# flycopter_v1.net
KiCad netlist of a schematic drawn in EAGLE
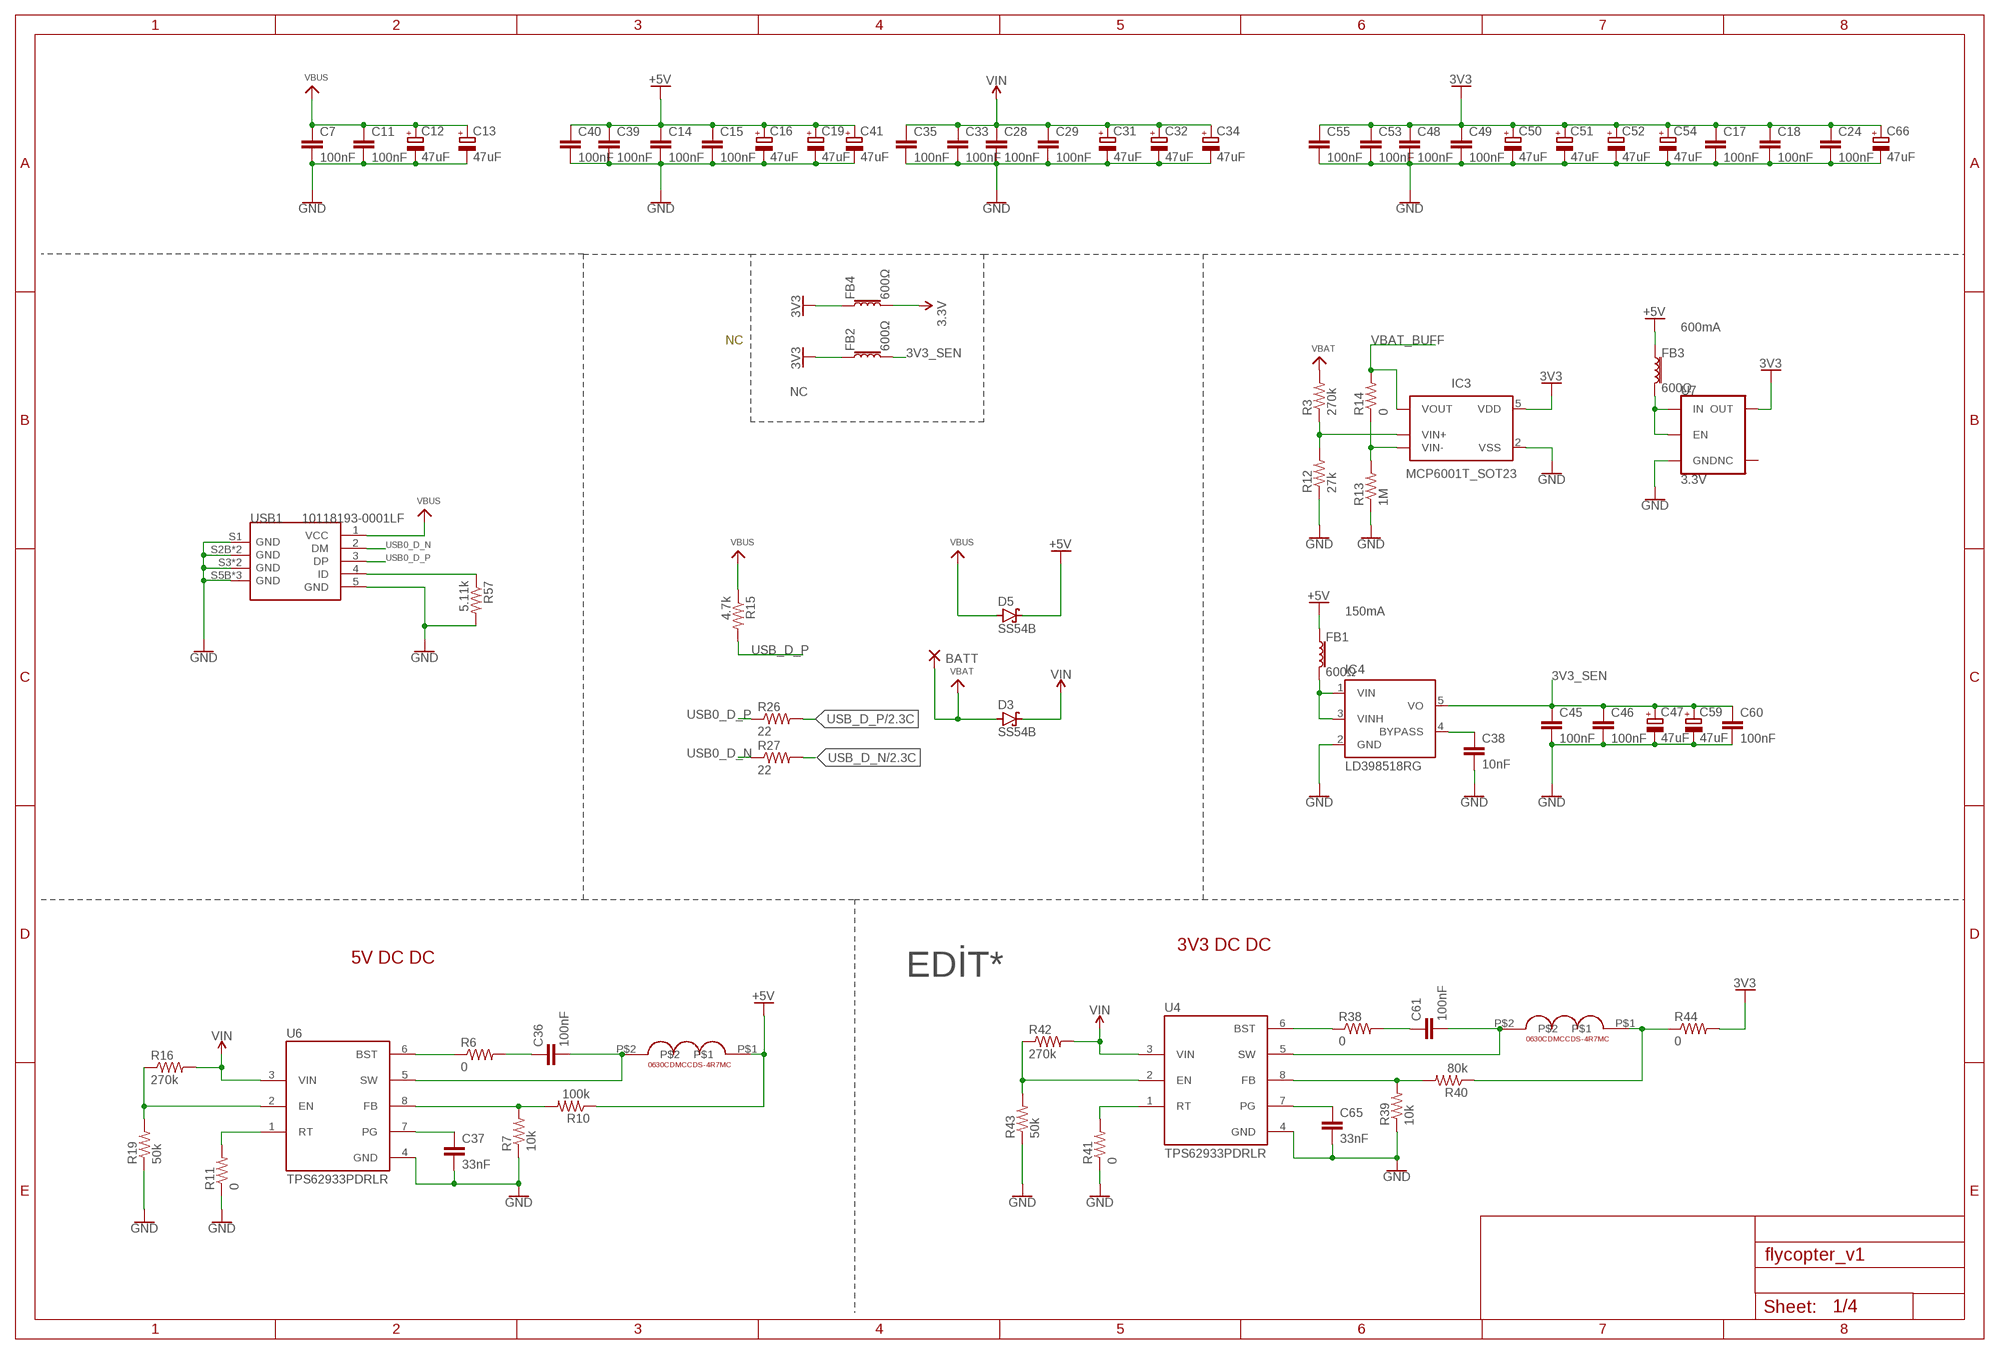
[diagram p0: schematic, sheet 1]
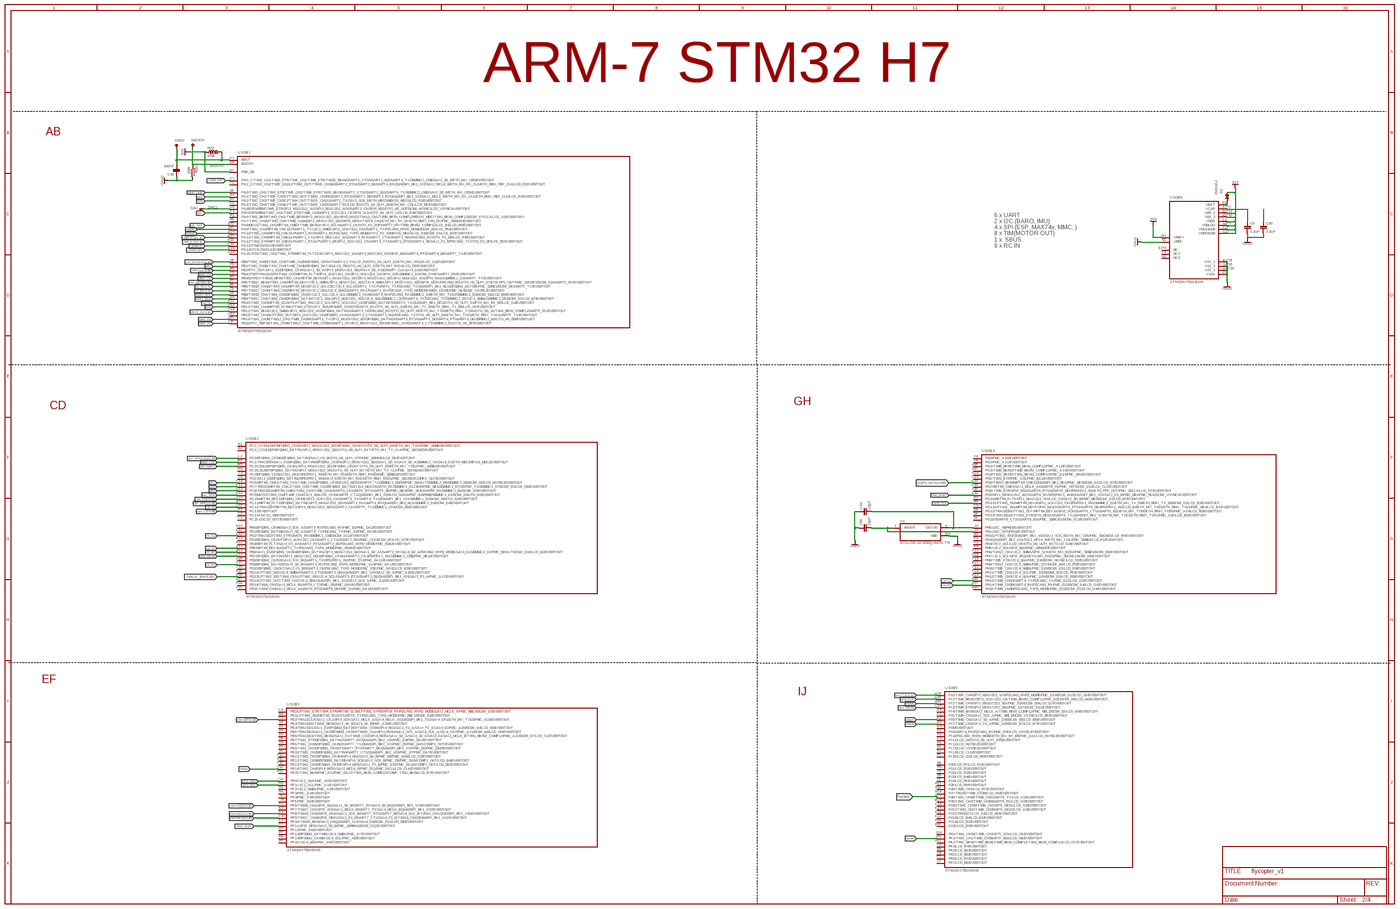
[diagram p1: schematic, sheet 2, overview]
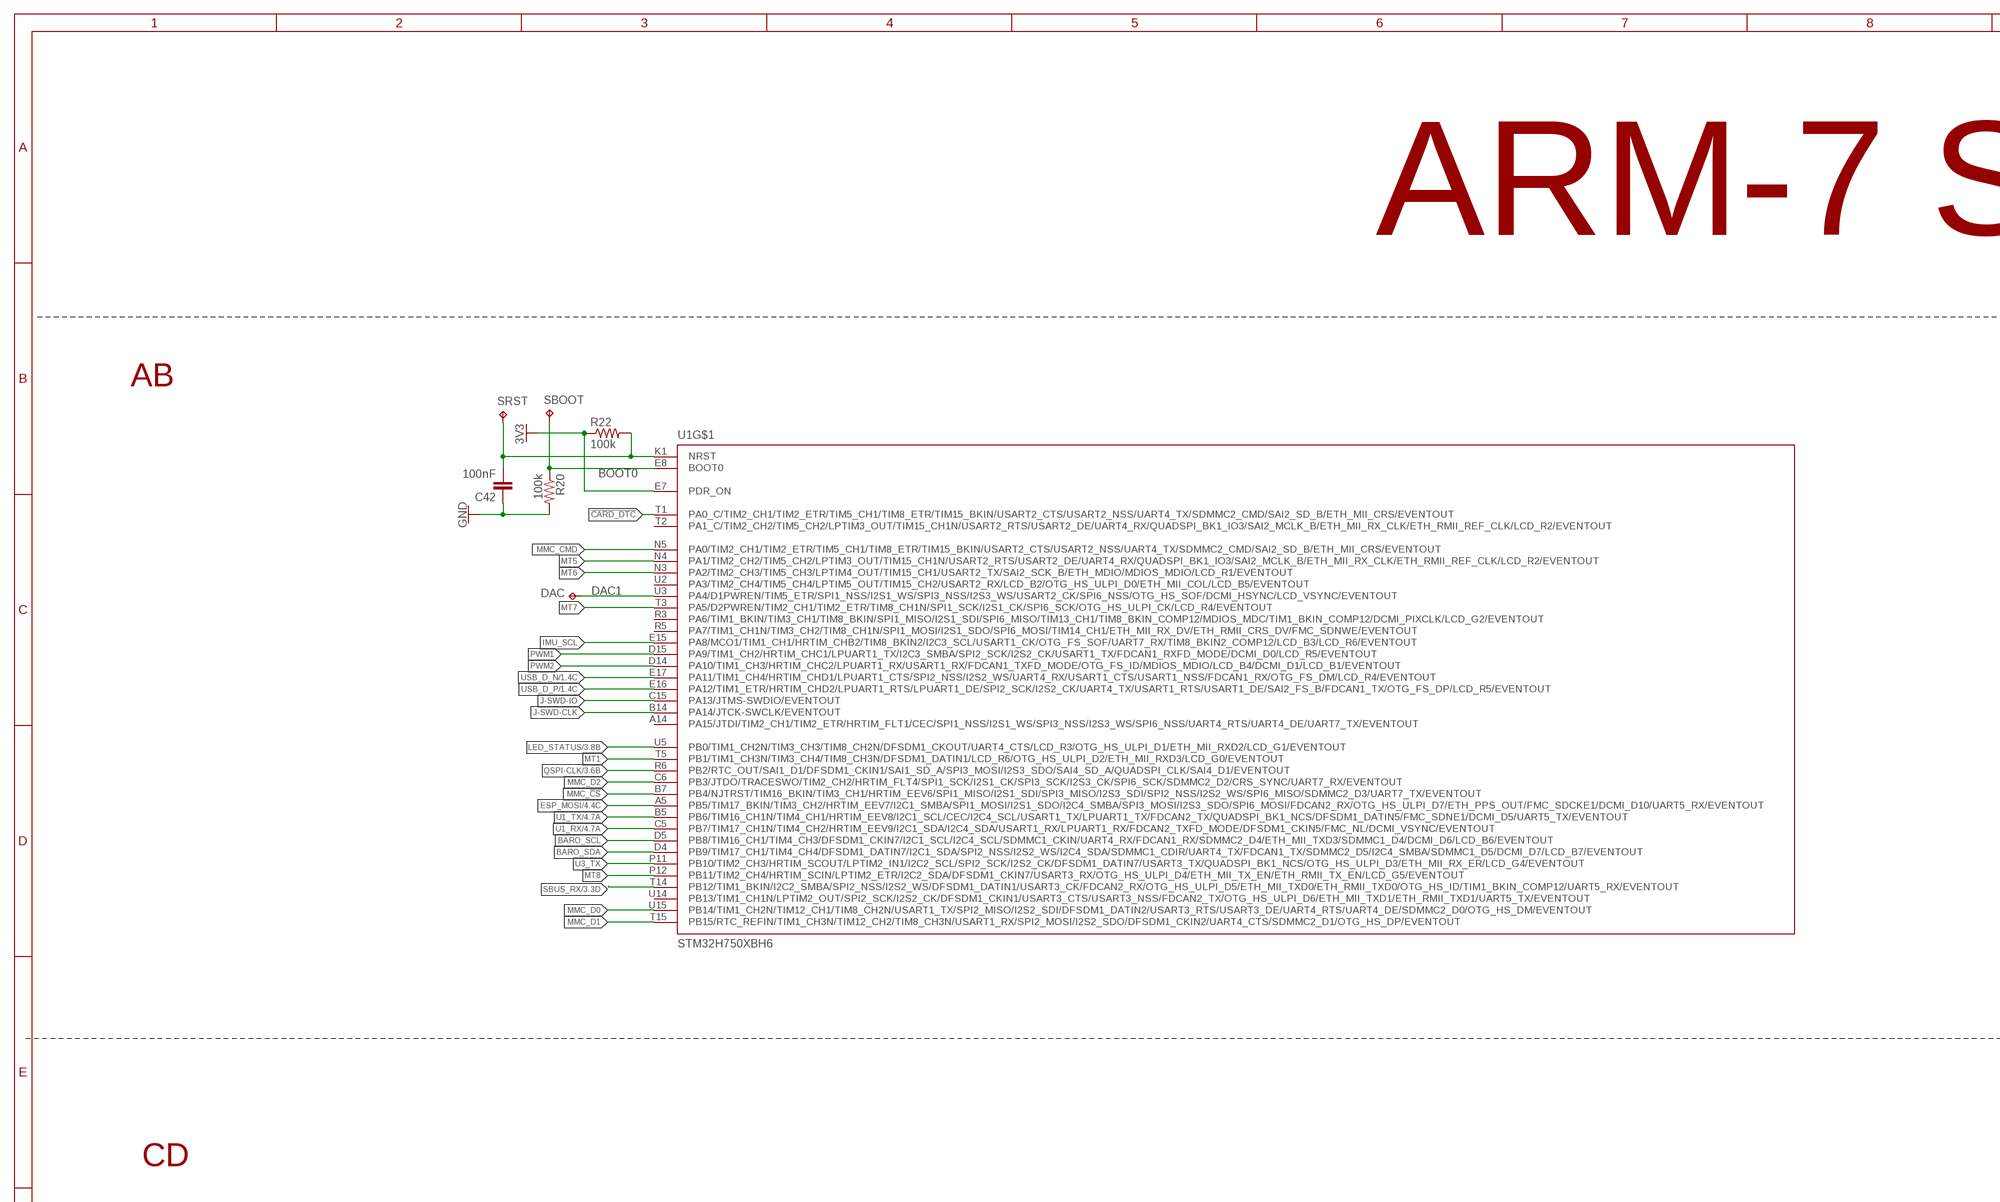
[diagram p2: schematic, sheet 2, part 1 of 4]
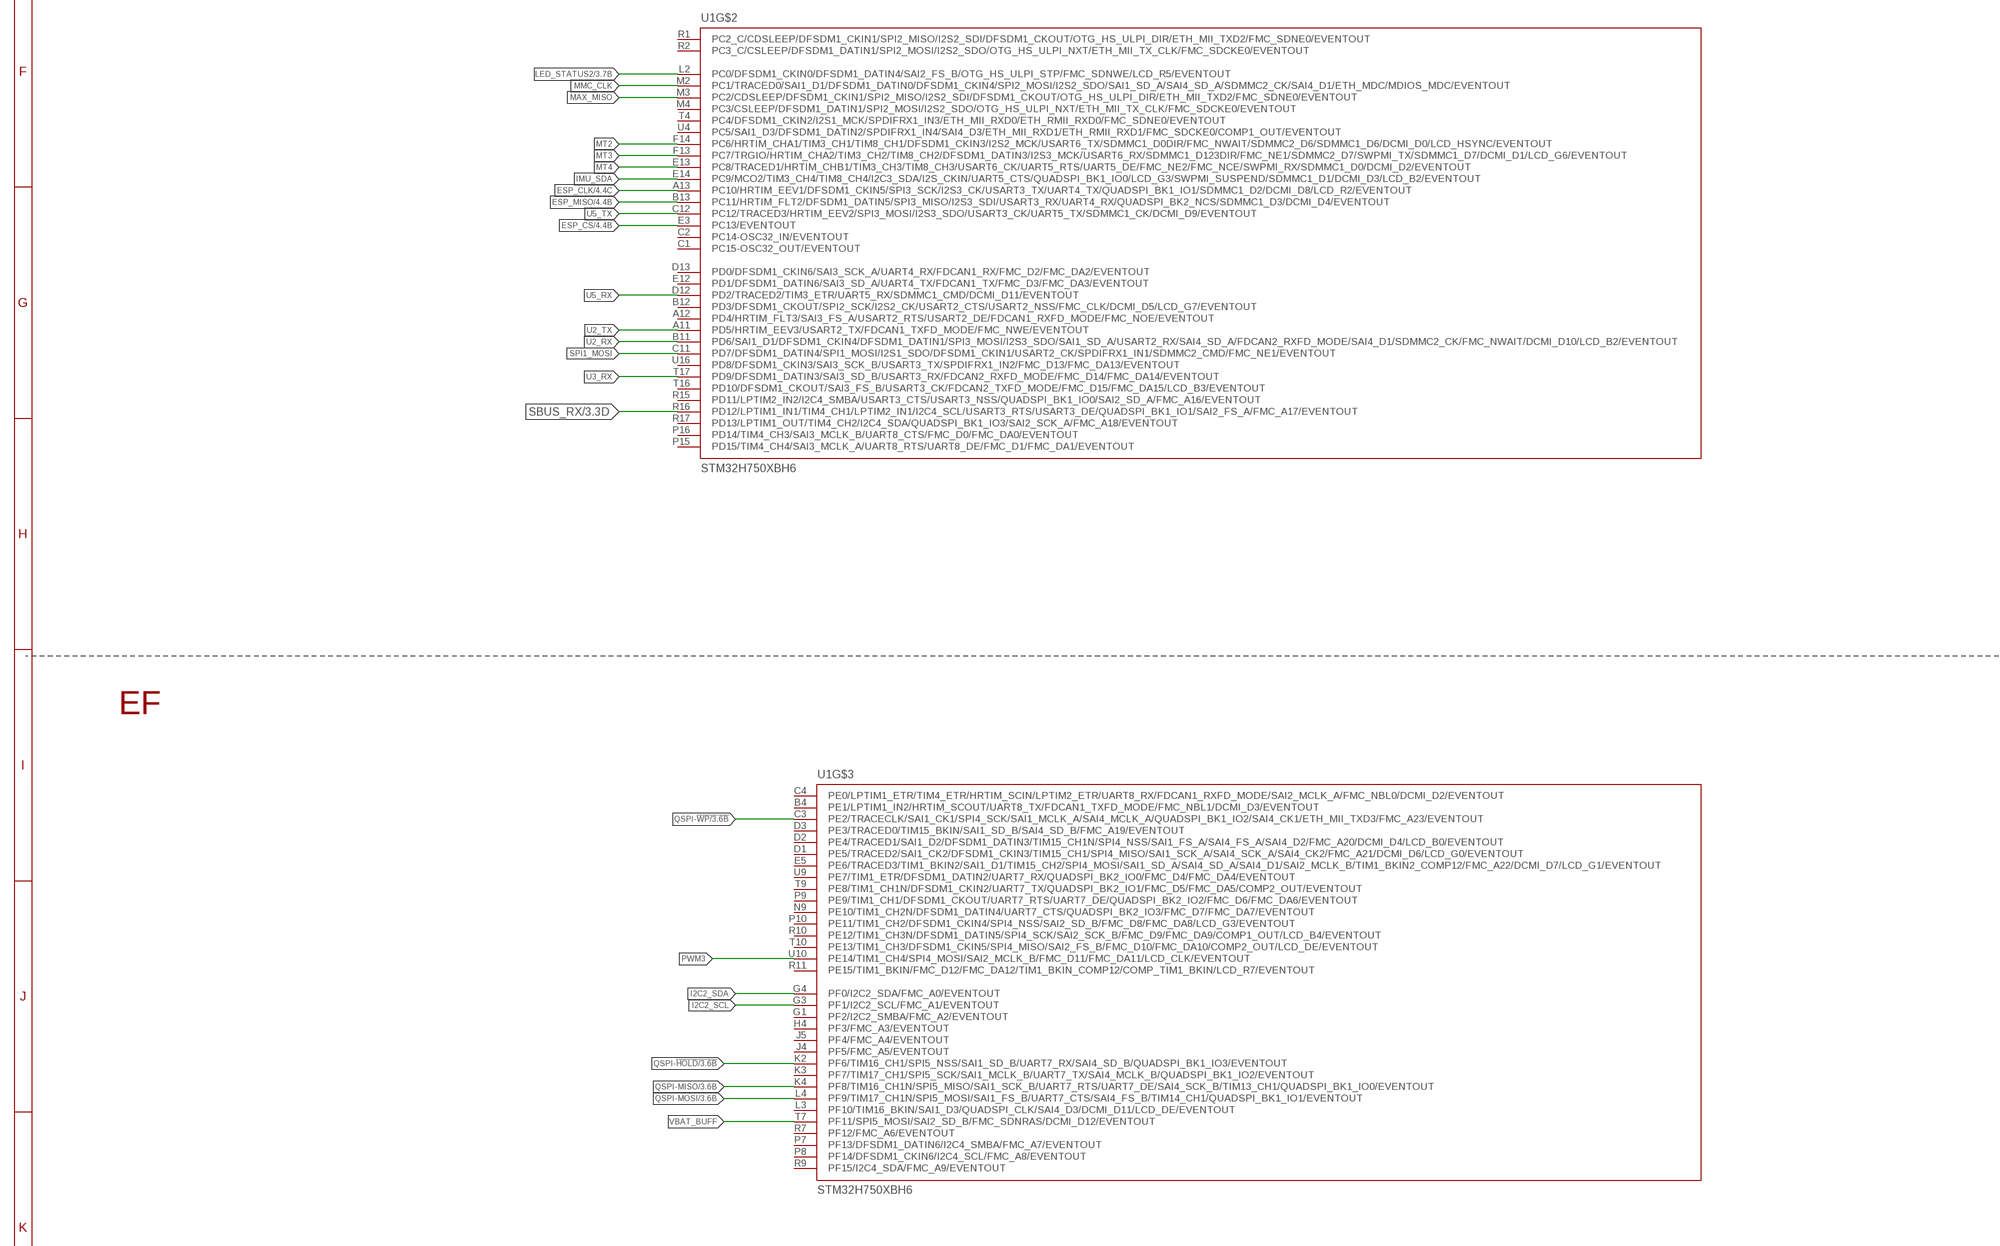
[diagram p3: schematic, sheet 2, part 2 of 4]
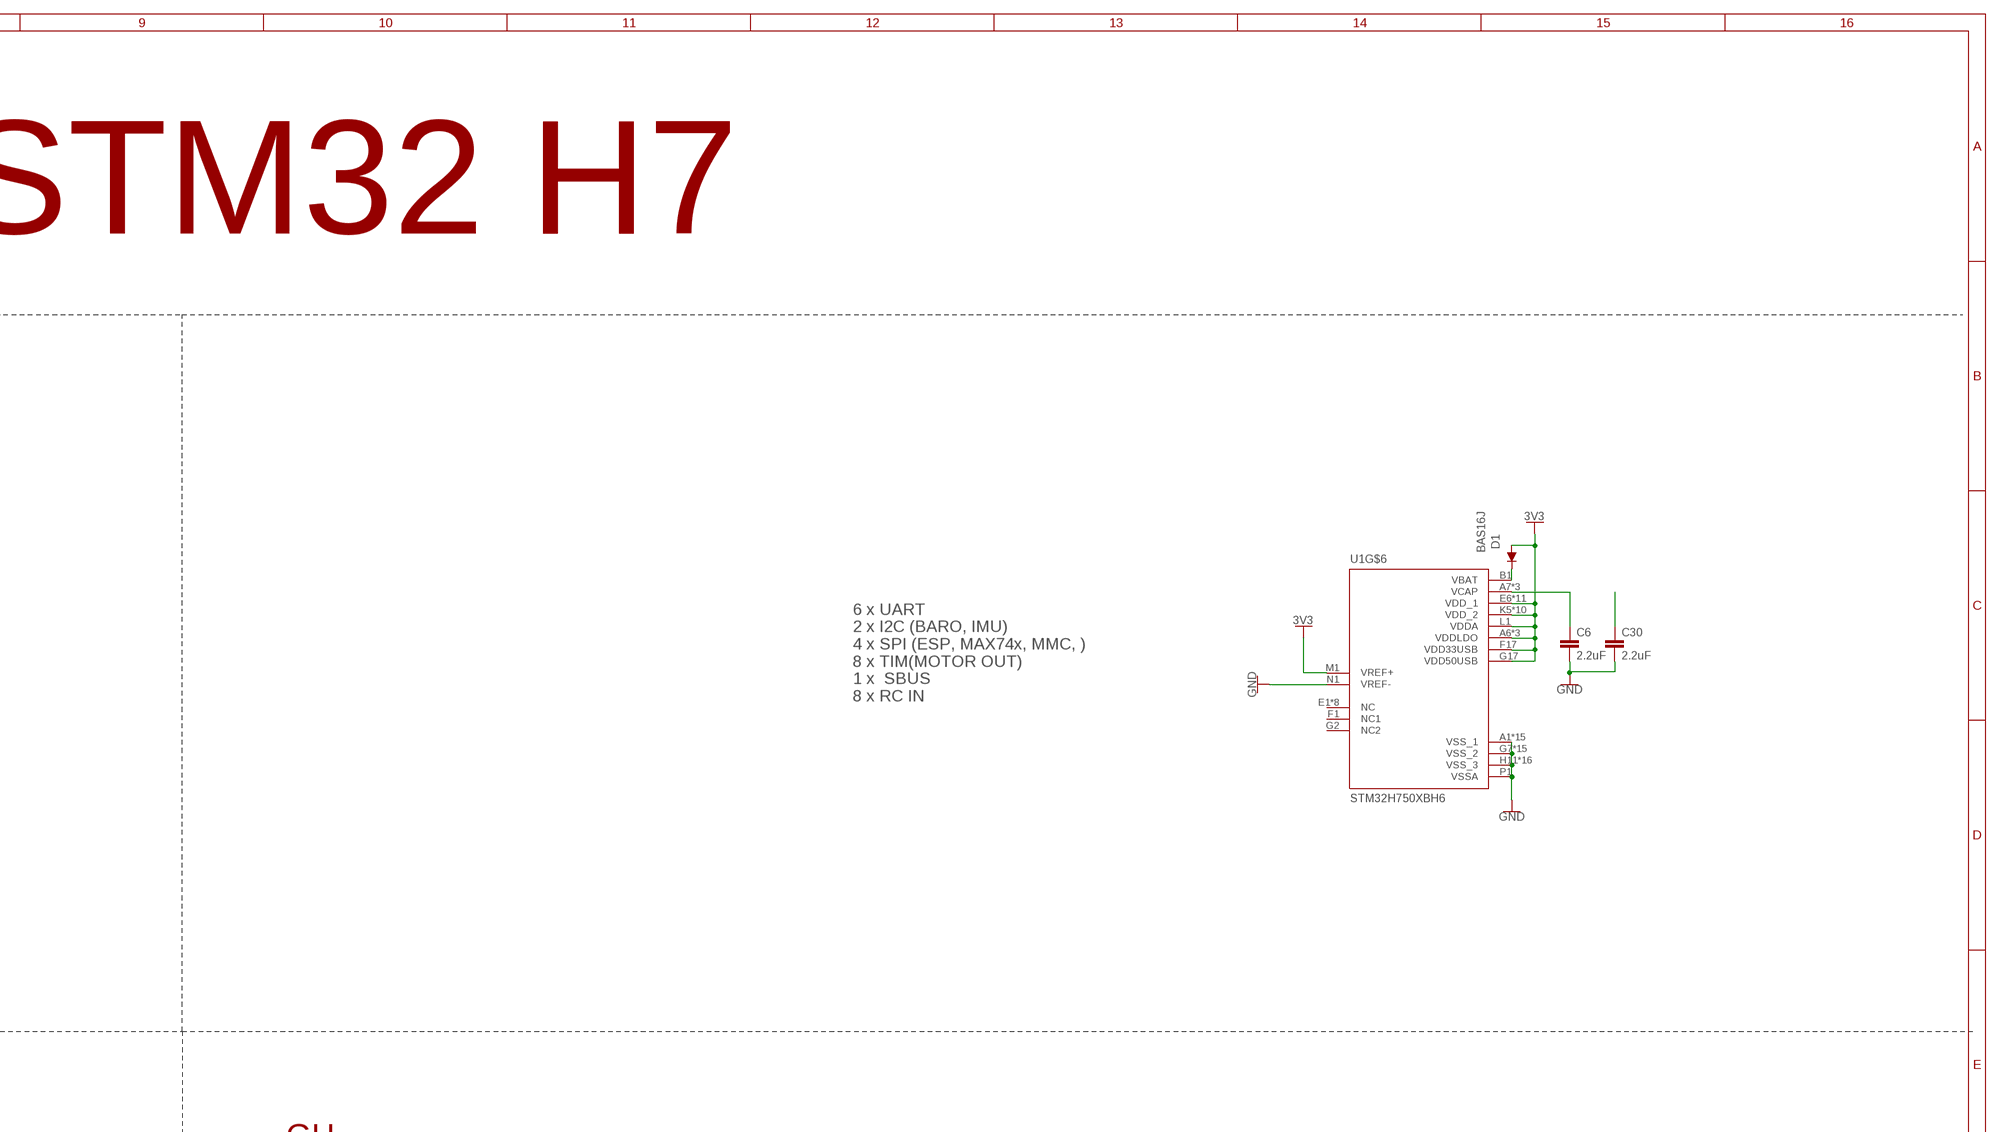
[diagram p4: schematic, sheet 2, part 3 of 4]
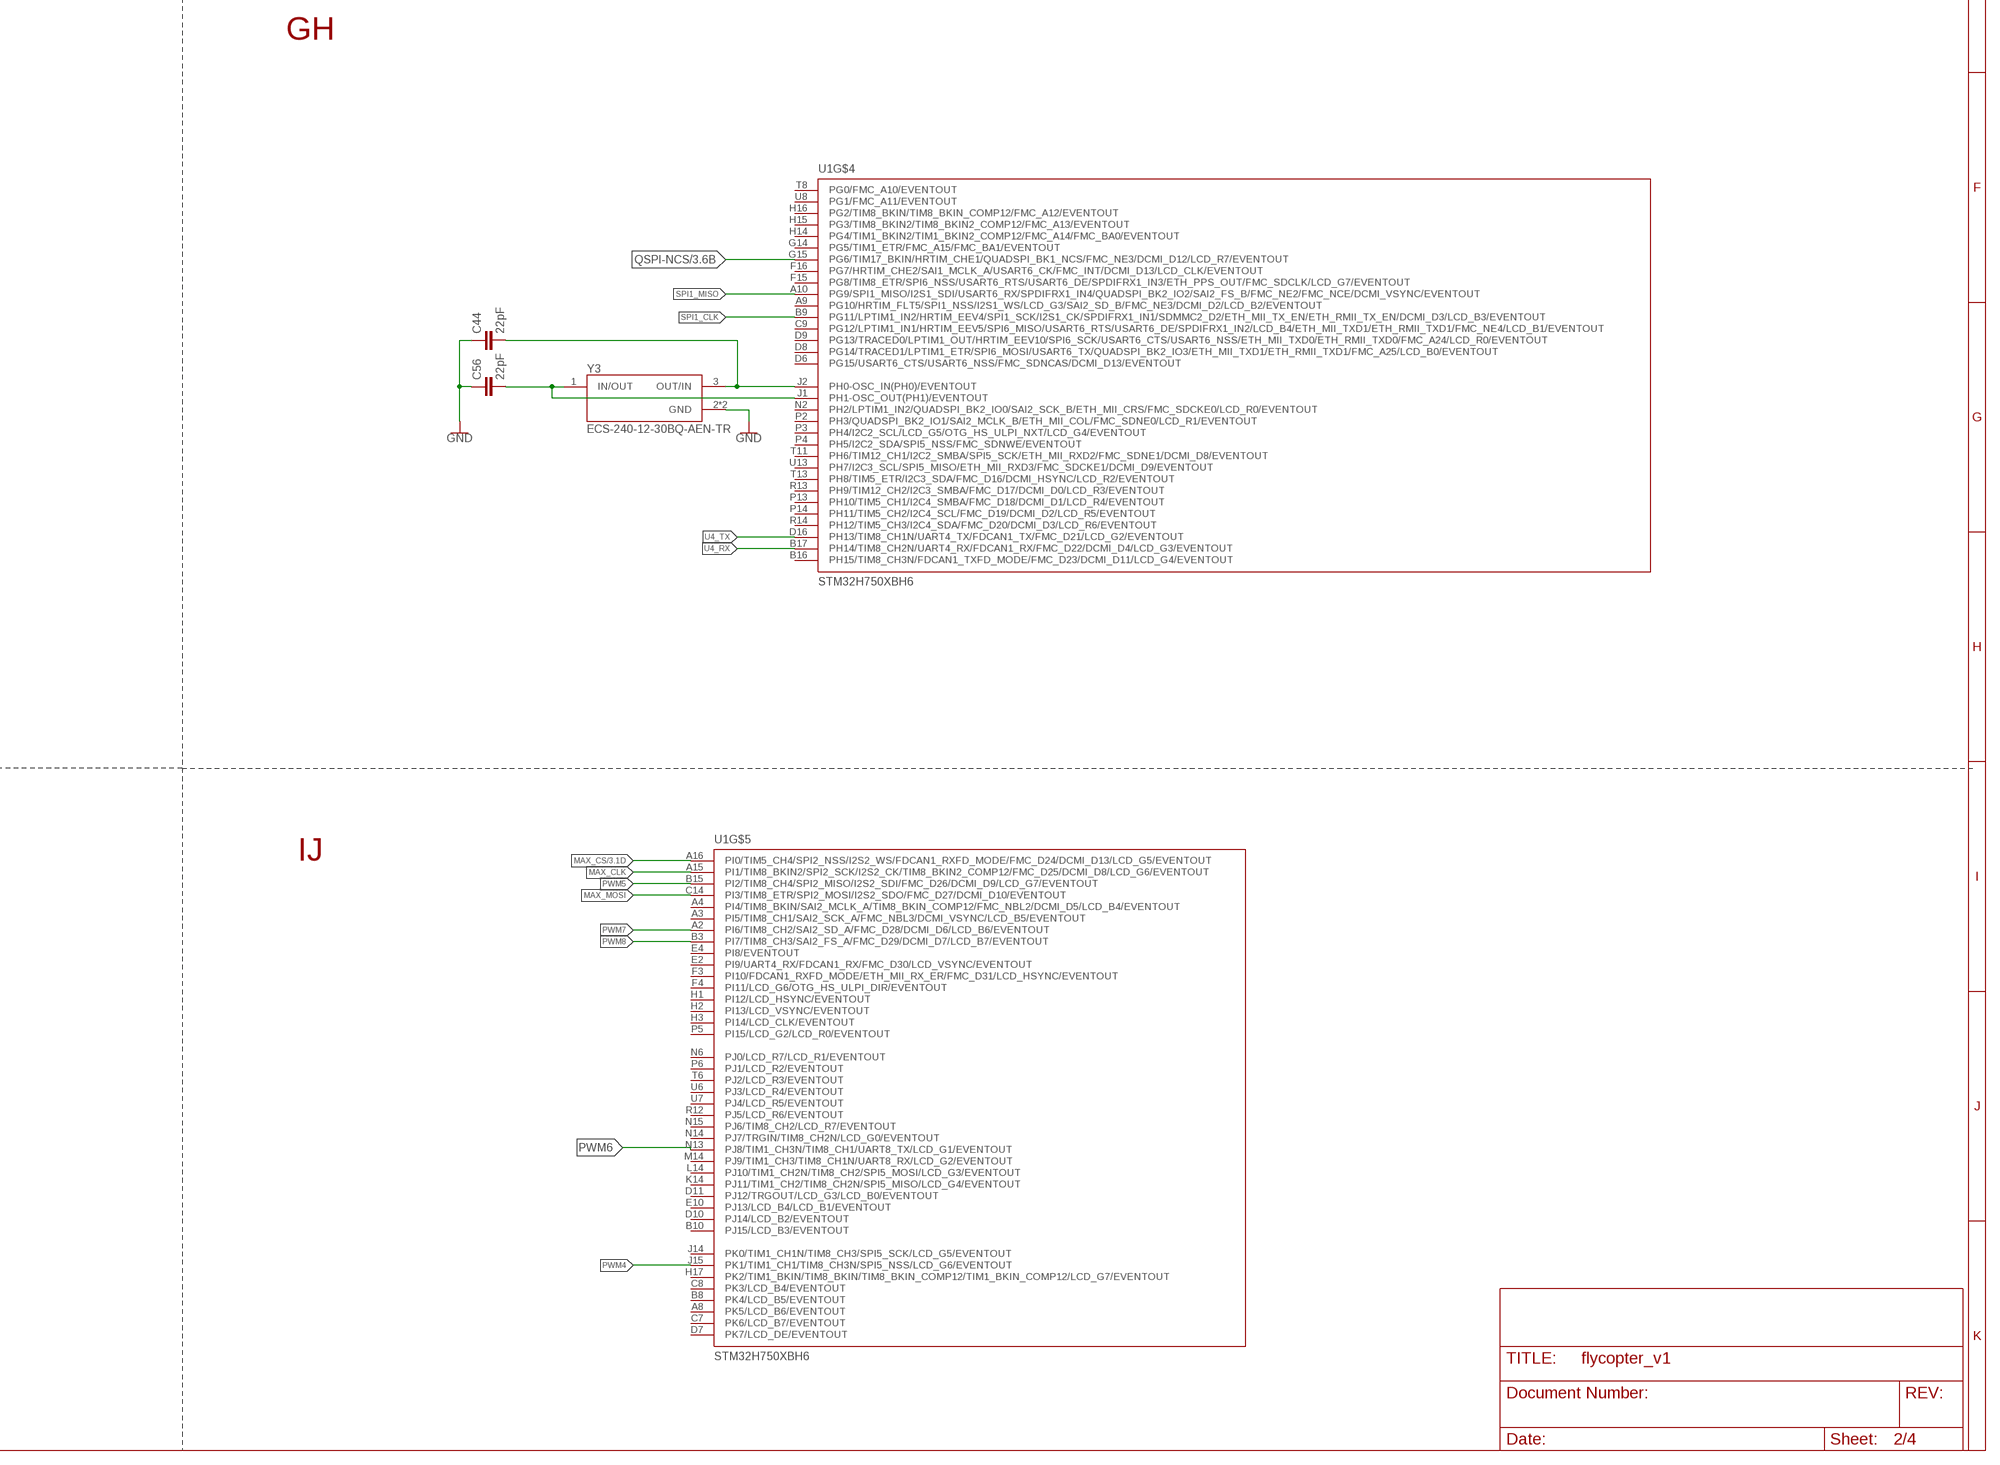
[diagram p5: schematic, sheet 2, part 4 of 4]
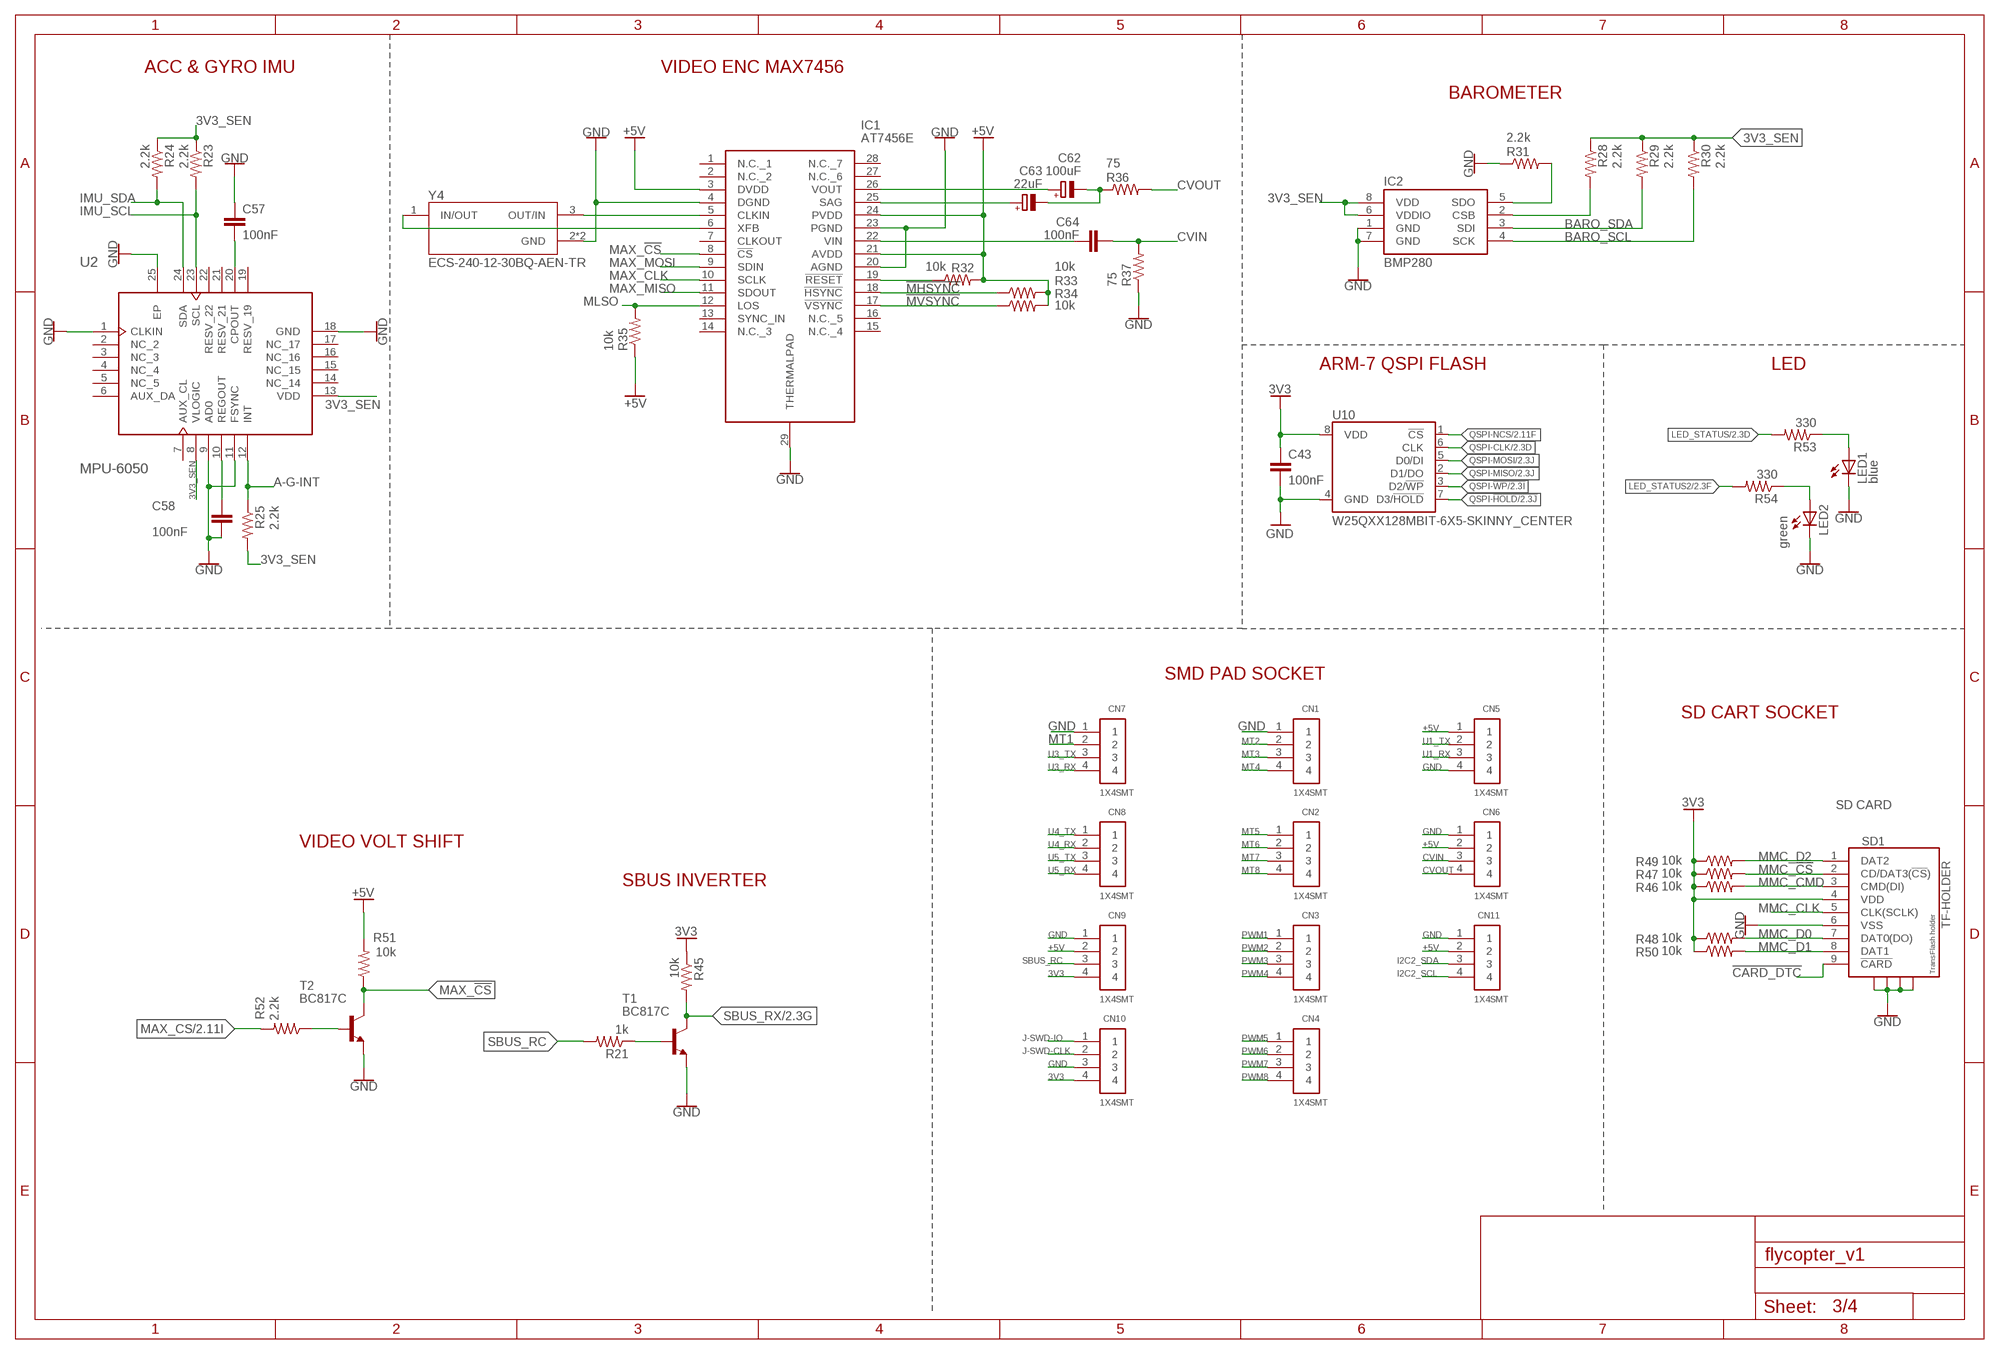
[diagram p6: schematic, sheet 3]
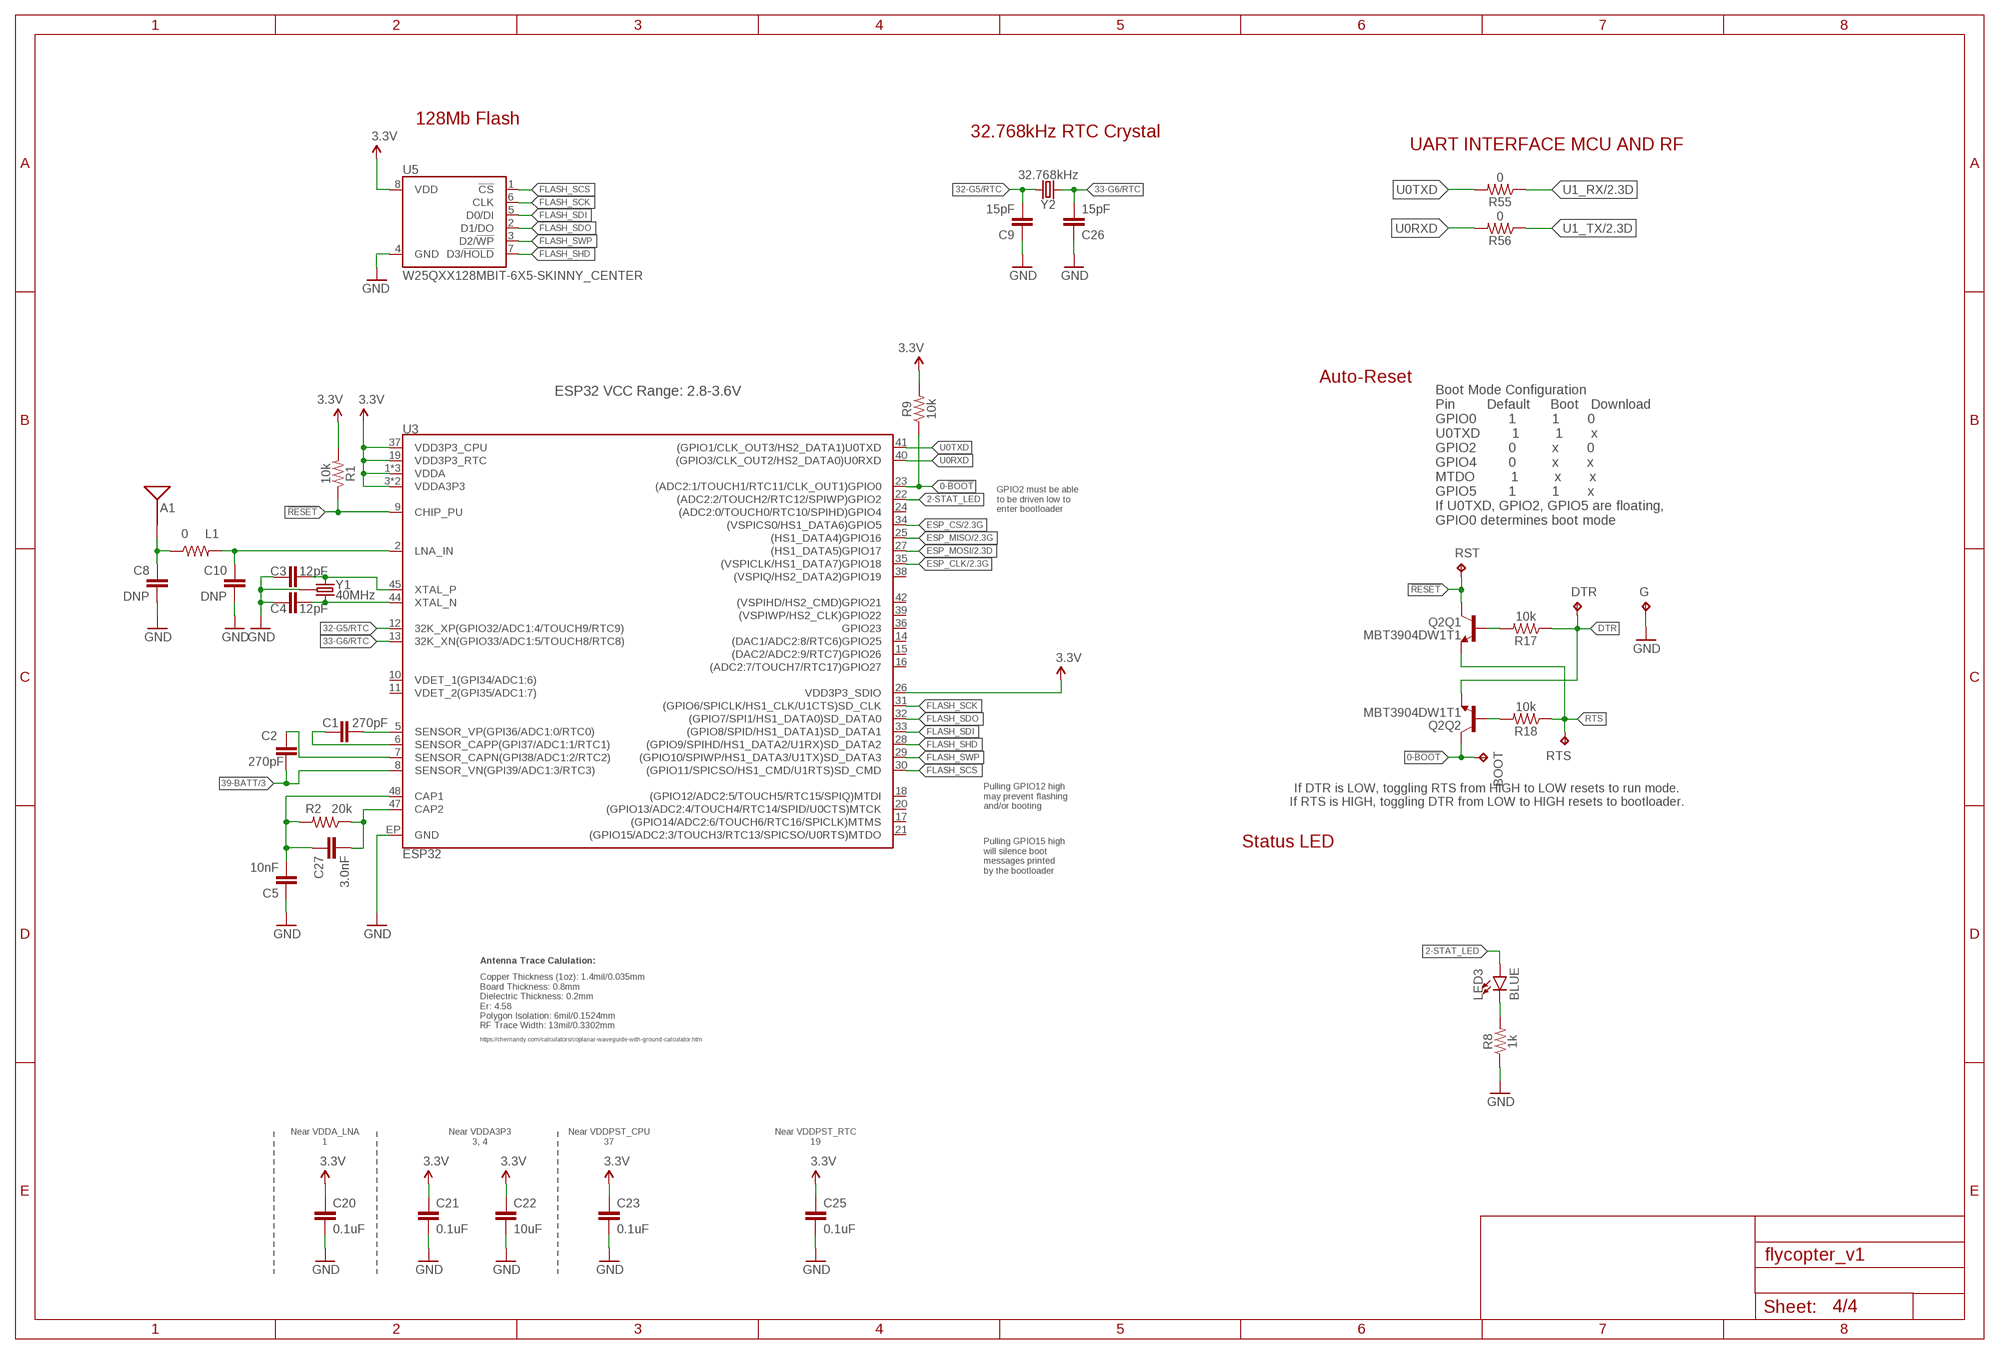
[diagram p7: schematic, sheet 4]

(export (version "E")
  (design (tool "Eeschema 10.0.6"))
  (components
    (comp (ref "C6")
      (value "2.2uF")
      (footprint "eagle-import:C0603K")
      (libsource (lib "eagle-import") (part "C-EUC0603K"))
    )
    (comp (ref "C30")
      (value "2.2uF")
      (footprint "eagle-import:C0603K")
      (libsource (lib "eagle-import") (part "C-EUC0603K"))
    )
    (comp (ref "C42")
      (value "100nF")
      (footprint "eagle-import:C0603K")
      (libsource (lib "eagle-import") (part "C-EUC0603K"))
    )
    (comp (ref "C44")
      (value "22pF")
      (footprint "eagle-import:C0402K")
      (libsource (lib "eagle-import") (part "C-EUC0402K"))
    )
    (comp (ref "C56")
      (value "22pF")
      (footprint "eagle-import:C0402K")
      (libsource (lib "eagle-import") (part "C-EUC0402K"))
    )
    (comp (ref "D1")
      (value "BAS16J")
      (footprint "eagle-import:DIODE_SOD123")
      (libsource (lib "eagle-import") (part "DIODE_DIODE-SOD123"))
    )
    (comp (ref "DAC")
      (value "TPTP06R")
      (footprint "eagle-import:TP06R")
      (libsource (lib "eagle-import") (part "TPTP06R"))
    )
    (comp (ref "R20")
      (value "100k")
      (footprint "eagle-import:R0402")
      (libsource (lib "eagle-import") (part "R-US_R0402"))
    )
    (comp (ref "R22")
      (value "100k")
      (footprint "eagle-import:R0402")
      (libsource (lib "eagle-import") (part "R-US_R0402"))
    )
    (comp (ref "SBOOT")
      (value "TPTP06R")
      (footprint "eagle-import:TP06R")
      (libsource (lib "eagle-import") (part "TPTP06R"))
    )
    (comp (ref "SRST")
      (value "TPTP06R")
      (footprint "eagle-import:TP06R")
      (libsource (lib "eagle-import") (part "TPTP06R"))
    )
    (comp (ref "U1")
      (value "STM32H750XBH6")
      (footprint "eagle-import:IC_STM32H750XBH6")
      (fields (field (name "MF") "STMicroelectronics"))
      (libsource (lib "eagle-import") (part "STM32H750XBH6"))
    )
    (comp (ref "Y3")
      (value "ECS-240-12-30BQ-AEN-TR")
      (footprint "eagle-import:XTAL_ECS-240-12-30BQ-AEN-TR")
      (fields (field (name "MF") "ECS Inc."))
      (libsource (lib "eagle-import") (part "ECS-240-12-30BQ-AEN-TR"))
    )
    (comp (ref "C43")
      (value "100nF")
      (footprint "eagle-import:C0603K")
      (libsource (lib "eagle-import") (part "C-EUC0603K"))
    )
    (comp (ref "C57")
      (value "100nF")
      (footprint "eagle-import:C0603K")
      (libsource (lib "eagle-import") (part "C-EUC0603K"))
    )
    (comp (ref "C58")
      (value "100nF")
      (footprint "eagle-import:C0603K")
      (libsource (lib "eagle-import") (part "C-EUC0603K"))
    )
    (comp (ref "C62")
      (value "100uF")
      (footprint "eagle-import:A_3216-18R")
      (libsource (lib "eagle-import") (part "CPOL-EUA/3216-18R"))
    )
    (comp (ref "C63")
      (value "22uF")
      (footprint "eagle-import:A_3216-18R")
      (libsource (lib "eagle-import") (part "CPOL-EUA/3216-18R"))
    )
    (comp (ref "C64")
      (value "100nF")
      (footprint "eagle-import:C0603K")
      (libsource (lib "eagle-import") (part "C-EUC0603K"))
    )
    (comp (ref "CN1")
      (value "1X4SMT")
      (footprint "eagle-import:1X4-SMT")
      (libsource (lib "eagle-import") (part "1X4SMT"))
    )
    (comp (ref "CN2")
      (value "1X4SMT")
      (footprint "eagle-import:1X4-SMT")
      (libsource (lib "eagle-import") (part "1X4SMT"))
    )
    (comp (ref "CN3")
      (value "1X4SMT")
      (footprint "eagle-import:1X4-SMT")
      (libsource (lib "eagle-import") (part "1X4SMT"))
    )
    (comp (ref "CN4")
      (value "1X4SMT")
      (footprint "eagle-import:1X4-SMT")
      (libsource (lib "eagle-import") (part "1X4SMT"))
    )
    (comp (ref "CN5")
      (value "1X4SMT")
      (footprint "eagle-import:1X4-SMT")
      (libsource (lib "eagle-import") (part "1X4SMT"))
    )
    (comp (ref "CN6")
      (value "1X4SMT")
      (footprint "eagle-import:1X4-SMT")
      (libsource (lib "eagle-import") (part "1X4SMT"))
    )
    (comp (ref "CN7")
      (value "1X4SMT")
      (footprint "eagle-import:1X4-SMT")
      (libsource (lib "eagle-import") (part "1X4SMT"))
    )
    (comp (ref "CN8")
      (value "1X4SMT")
      (footprint "eagle-import:1X4-SMT")
      (libsource (lib "eagle-import") (part "1X4SMT"))
    )
    (comp (ref "CN9")
      (value "1X4SMT")
      (footprint "eagle-import:1X4-SMT")
      (libsource (lib "eagle-import") (part "1X4SMT"))
    )
    (comp (ref "CN10")
      (value "1X4SMT")
      (footprint "eagle-import:1X4-SMT")
      (libsource (lib "eagle-import") (part "1X4SMT"))
    )
    (comp (ref "CN11")
      (value "1X4SMT")
      (footprint "eagle-import:1X4-SMT")
      (libsource (lib "eagle-import") (part "1X4SMT"))
    )
    (comp (ref "IC1")
      (value "AT7456E")
      (footprint "eagle-import:SOP65P640X120-29N")
      (libsource (lib "eagle-import") (part "AT7456E"))
    )
    (comp (ref "IC2")
      (value "BMP280")
      (footprint "eagle-import:BMP280")
      (libsource (lib "eagle-import") (part "BMP280"))
    )
    (comp (ref "LED1")
      (value "blue")
      (footprint "eagle-import:CHIPLED_0603")
      (libsource (lib "eagle-import") (part "LEDCHIPLED_0603"))
    )
    (comp (ref "LED2")
      (value "green")
      (footprint "eagle-import:CHIPLED_0603")
      (libsource (lib "eagle-import") (part "LEDCHIPLED_0603"))
    )
    (comp (ref "R21")
      (value "1k")
      (footprint "eagle-import:R0402")
      (libsource (lib "eagle-import") (part "R-US_R0402"))
    )
    (comp (ref "R23")
      (value "2.2k")
      (footprint "eagle-import:R0402")
      (libsource (lib "eagle-import") (part "R-US_R0402"))
    )
    (comp (ref "R24")
      (value "2.2k")
      (footprint "eagle-import:R0402")
      (libsource (lib "eagle-import") (part "R-US_R0402"))
    )
    (comp (ref "R25")
      (value "2.2k")
      (footprint "eagle-import:R0402")
      (libsource (lib "eagle-import") (part "R-US_R0402"))
    )
    (comp (ref "R28")
      (value "2.2k")
      (footprint "eagle-import:R0402")
      (libsource (lib "eagle-import") (part "R-US_R0402"))
    )
    (comp (ref "R29")
      (value "2.2k")
      (footprint "eagle-import:R0402")
      (libsource (lib "eagle-import") (part "R-US_R0402"))
    )
    (comp (ref "R30")
      (value "2.2k")
      (footprint "eagle-import:R0402")
      (libsource (lib "eagle-import") (part "R-US_R0402"))
    )
    (comp (ref "R31")
      (value "2.2k")
      (footprint "eagle-import:R0402")
      (libsource (lib "eagle-import") (part "R-US_R0402"))
    )
    (comp (ref "R32")
      (value "10k")
      (footprint "eagle-import:R0402")
      (libsource (lib "eagle-import") (part "R-US_R0402"))
    )
    (comp (ref "R33")
      (value "10k")
      (footprint "eagle-import:R0402")
      (libsource (lib "eagle-import") (part "R-US_R0402"))
    )
    (comp (ref "R34")
      (value "10k")
      (footprint "eagle-import:R0402")
      (libsource (lib "eagle-import") (part "R-US_R0402"))
    )
    (comp (ref "R35")
      (value "10k")
      (footprint "eagle-import:R0402")
      (libsource (lib "eagle-import") (part "R-US_R0402"))
    )
    (comp (ref "R36")
      (value "75")
      (footprint "eagle-import:R0402")
      (libsource (lib "eagle-import") (part "R-US_R0402"))
    )
    (comp (ref "R37")
      (value "75")
      (footprint "eagle-import:R0402")
      (libsource (lib "eagle-import") (part "R-US_R0402"))
    )
    (comp (ref "R45")
      (value "10k")
      (footprint "eagle-import:R0402")
      (libsource (lib "eagle-import") (part "R-US_R0402"))
    )
    (comp (ref "R46")
      (value "10k")
      (footprint "eagle-import:R0402")
      (libsource (lib "eagle-import") (part "R-US_R0402"))
    )
    (comp (ref "R47")
      (value "10k")
      (footprint "eagle-import:R0402")
      (libsource (lib "eagle-import") (part "R-US_R0402"))
    )
    (comp (ref "R48")
      (value "10k")
      (footprint "eagle-import:R0402")
      (libsource (lib "eagle-import") (part "R-US_R0402"))
    )
    (comp (ref "R49")
      (value "10k")
      (footprint "eagle-import:R0402")
      (libsource (lib "eagle-import") (part "R-US_R0402"))
    )
    (comp (ref "R50")
      (value "10k")
      (footprint "eagle-import:R0402")
      (libsource (lib "eagle-import") (part "R-US_R0402"))
    )
    (comp (ref "R51")
      (value "10k")
      (footprint "eagle-import:R0402")
      (libsource (lib "eagle-import") (part "R-US_R0402"))
    )
    (comp (ref "R52")
      (value "2.2k")
      (footprint "eagle-import:R0402")
      (libsource (lib "eagle-import") (part "R-US_R0402"))
    )
    (comp (ref "R53")
      (value "330")
      (footprint "eagle-import:R0402")
      (libsource (lib "eagle-import") (part "R-US_R0402"))
    )
    (comp (ref "R54")
      (value "330")
      (footprint "eagle-import:R0402")
      (libsource (lib "eagle-import") (part "R-US_R0402"))
    )
    (comp (ref "SD1")
      (value "TF-HOLDER")
      (footprint "eagle-import:TF-PULL")
      (libsource (lib "eagle-import") (part "TF-HOLDER"))
    )
    (comp (ref "T1")
      (value "BC817C")
      (footprint "eagle-import:SOT23-BEC")
      (libsource (lib "eagle-import") (part "-NPN-SOT23-BECBC817-16"))
    )
    (comp (ref "T2")
      (value "BC817C")
      (footprint "eagle-import:SOT23-BEC")
      (libsource (lib "eagle-import") (part "-NPN-SOT23-BECBC817-16"))
    )
    (comp (ref "U2")
      (value "MPU-6050")
      (footprint "eagle-import:24-VFQFN")
      (fields
        (field (name "DIGIKEY_PART_NUMBER") "1428-1007-1-ND")
        (field (name "MANUFACTURER") "TDK InvenSense")
        (field (name "CREATED_BY") "PCBLayout.com")
      )
      (libsource (lib "eagle-import") (part "MPU-6050"))
    )
    (comp (ref "U10")
      (value "W25QXX128MBIT-6X5-SKINNY_CENTER")
      (footprint "eagle-import:WSON-8-6X5-SKINNY_CENTERPAD")
      (libsource (lib "eagle-import") (part "W25QXX128MBIT-6X5-SKINNY_CENTER"))
    )
    (comp (ref "Y4")
      (value "ECS-240-12-30BQ-AEN-TR")
      (footprint "eagle-import:XTAL_ECS-240-12-30BQ-AEN-TR")
      (fields (field (name "MF") "ECS Inc."))
      (libsource (lib "eagle-import") (part "ECS-240-12-30BQ-AEN-TR"))
    )
    (comp (ref "A1")
      (value "ANTENNA2.4GHZ-8.0X1.0MM")
      (footprint "eagle-import:ANT-2.4GHZ-8.0X1.0MM")
      (libsource (lib "eagle-import") (part "ANTENNA2.4GHZ-8.0X1.0MM"))
    )
    (comp (ref "BOOT")
      (value "TPTP06R")
      (footprint "eagle-import:TP06R")
      (libsource (lib "eagle-import") (part "TPTP06R"))
    )
    (comp (ref "C1")
      (value "270pF")
      (footprint "eagle-import:0402-TIGHT")
      (libsource (lib "eagle-import") (part "270PF-0402T-50V-5%"))
    )
    (comp (ref "C2")
      (value "270pF")
      (footprint "eagle-import:0402-TIGHT")
      (libsource (lib "eagle-import") (part "270PF-0402T-50V-5%"))
    )
    (comp (ref "C3")
      (value "12pF")
      (footprint "eagle-import:0402-TIGHT")
      (libsource (lib "eagle-import") (part "12PF-0402T-50V-5%"))
    )
    (comp (ref "C4")
      (value "12pF")
      (footprint "eagle-import:0402-TIGHT")
      (libsource (lib "eagle-import") (part "12PF-0402T-50V-5%"))
    )
    (comp (ref "C5")
      (value "10nF")
      (footprint "eagle-import:0402-TIGHT")
      (libsource (lib "eagle-import") (part "10NF-0402T-25V-10%"))
    )
    (comp (ref "C8")
      (value "DNP")
      (footprint "eagle-import:0402-TIGHT")
      (libsource (lib "eagle-import") (part "CAP-0402-TIGHT"))
    )
    (comp (ref "C9")
      (value "15pF")
      (footprint "eagle-import:0402-TIGHT")
      (libsource (lib "eagle-import") (part "15PF-0402T-50V-5%"))
    )
    (comp (ref "C10")
      (value "DNP")
      (footprint "eagle-import:0402-TIGHT")
      (libsource (lib "eagle-import") (part "CAP-0402-TIGHT"))
    )
    (comp (ref "C20")
      (value "0.1uF")
      (footprint "eagle-import:0402-TIGHT")
      (libsource (lib "eagle-import") (part "0.1UF-0402T-16V-10%"))
    )
    (comp (ref "C21")
      (value "0.1uF")
      (footprint "eagle-import:0402-TIGHT")
      (libsource (lib "eagle-import") (part "0.1UF-0402T-16V-10%"))
    )
    (comp (ref "C22")
      (value "10uF")
      (footprint "eagle-import:0402-TIGHT")
      (libsource (lib "eagle-import") (part "10UF-0402T-6.3V-20%"))
    )
    (comp (ref "C23")
      (value "0.1uF")
      (footprint "eagle-import:0402-TIGHT")
      (libsource (lib "eagle-import") (part "0.1UF-0402T-16V-10%"))
    )
    (comp (ref "C25")
      (value "0.1uF")
      (footprint "eagle-import:0402-TIGHT")
      (libsource (lib "eagle-import") (part "0.1UF-0402T-16V-10%"))
    )
    (comp (ref "C26")
      (value "15pF")
      (footprint "eagle-import:0402-TIGHT")
      (libsource (lib "eagle-import") (part "15PF-0402T-50V-5%"))
    )
    (comp (ref "C27")
      (value "3.0nF")
      (footprint "eagle-import:0402-TIGHT")
      (libsource (lib "eagle-import") (part "3.0NF-0402T-50V-5%"))
    )
    (comp (ref "DTR")
      (value "TPTP06R")
      (footprint "eagle-import:TP06R")
      (libsource (lib "eagle-import") (part "TPTP06R"))
    )
    (comp (ref "G")
      (value "TPTP06R")
      (footprint "eagle-import:TP06R")
      (libsource (lib "eagle-import") (part "TPTP06R"))
    )
    (comp (ref "L1")
      (value "0")
      (footprint "eagle-import:0402-TIGHT")
      (libsource (lib "eagle-import") (part "0OHM-0402T-1/10W"))
    )
    (comp (ref "LED3")
      (value "BLUE")
      (footprint "eagle-import:LED-0603")
      (libsource (lib "eagle-import") (part "LED-BLUE0603"))
    )
    (comp (ref "Q2")
      (value "MBT3904DW1T1")
      (footprint "eagle-import:SC70-6")
      (libsource (lib "eagle-import") (part "TRANS_NPN_DUAL-MBT3904DW1T1"))
    )
    (comp (ref "R1")
      (value "10k")
      (footprint "eagle-import:0402-TIGHT")
      (libsource (lib "eagle-import") (part "10KOHM-0402T-1/16W-1%"))
    )
    (comp (ref "R2")
      (value "20k")
      (footprint "eagle-import:0402-TIGHT")
      (libsource (lib "eagle-import") (part "20KOHM-0402T-1/16W-1%"))
    )
    (comp (ref "R8")
      (value "1k")
      (footprint "eagle-import:0402-TIGHT")
      (libsource (lib "eagle-import") (part "1KOHM-0402T-1/16W-1%"))
    )
    (comp (ref "R9")
      (value "10k")
      (footprint "eagle-import:0402-TIGHT")
      (libsource (lib "eagle-import") (part "10KOHM-0402T-1/16W-1%"))
    )
    (comp (ref "R17")
      (value "10k")
      (footprint "eagle-import:0402-TIGHT")
      (libsource (lib "eagle-import") (part "10KOHM-0402T-1/16W-1%"))
    )
    (comp (ref "R18")
      (value "10k")
      (footprint "eagle-import:0402-TIGHT")
      (libsource (lib "eagle-import") (part "10KOHM-0402T-1/16W-1%"))
    )
    (comp (ref "R55")
      (value "0")
      (footprint "eagle-import:0402-TIGHT")
      (libsource (lib "eagle-import") (part "10KOHM-0402T-1/16W-1%"))
    )
    (comp (ref "R56")
      (value "0")
      (footprint "eagle-import:0402-TIGHT")
      (libsource (lib "eagle-import") (part "10KOHM-0402T-1/16W-1%"))
    )
    (comp (ref "RST")
      (value "TPTP06R")
      (footprint "eagle-import:TP06R")
      (libsource (lib "eagle-import") (part "TPTP06R"))
    )
    (comp (ref "RTS")
      (value "TPTP06R")
      (footprint "eagle-import:TP06R")
      (libsource (lib "eagle-import") (part "TPTP06R"))
    )
    (comp (ref "U3")
      (value "ESP32")
      (footprint "eagle-import:QFN48-0.4MM")
      (libsource (lib "eagle-import") (part "ESP32"))
    )
    (comp (ref "U5")
      (value "W25QXX128MBIT-6X5-SKINNY_CENTER")
      (footprint "eagle-import:WSON-8-6X5-SKINNY_CENTERPAD")
      (libsource (lib "eagle-import") (part "W25QXX128MBIT-6X5-SKINNY_CENTER"))
    )
    (comp (ref "Y1")
      (value "40MHz")
      (footprint "eagle-import:CRYSTAL-SMD-2X2.5MM")
      (libsource (lib "eagle-import") (part "CRYSTAL-40MHZ-SMD-2X2.5MM"))
    )
    (comp (ref "Y2")
      (value "32.768kHz")
      (footprint "eagle-import:CRYSTAL-SMD-3.2X1.5MM")
      (libsource (lib "eagle-import") (part "CRYSTAL-32.768KHZSMD-3.2X1.5"))
    )
    (comp (ref "BATT")
      (value "SMD5")
      (footprint "eagle-import:SMD2,54-5,08")
      (libsource (lib "eagle-import") (part "SMD5"))
    )
    (comp (ref "C7")
      (value "100nF")
      (footprint "eagle-import:C0603K")
      (libsource (lib "eagle-import") (part "C-EUC0603K"))
    )
    (comp (ref "C11")
      (value "100nF")
      (footprint "eagle-import:C0603K")
      (libsource (lib "eagle-import") (part "C-EUC0603K"))
    )
    (comp (ref "C12")
      (value "47uF")
      (footprint "eagle-import:A_3216-18R")
      (libsource (lib "eagle-import") (part "CPOL-EUA/3216-18R"))
    )
    (comp (ref "C13")
      (value "47uF")
      (footprint "eagle-import:A_3216-18R")
      (libsource (lib "eagle-import") (part "CPOL-EUA/3216-18R"))
    )
    (comp (ref "C14")
      (value "100nF")
      (footprint "eagle-import:C0603K")
      (libsource (lib "eagle-import") (part "C-EUC0603K"))
    )
    (comp (ref "C15")
      (value "100nF")
      (footprint "eagle-import:C0603K")
      (libsource (lib "eagle-import") (part "C-EUC0603K"))
    )
    (comp (ref "C16")
      (value "47uF")
      (footprint "eagle-import:A_3216-18R")
      (libsource (lib "eagle-import") (part "CPOL-EUA/3216-18R"))
    )
    (comp (ref "C17")
      (value "100nF")
      (footprint "eagle-import:C0603K")
      (libsource (lib "eagle-import") (part "C-EUC0603K"))
    )
    (comp (ref "C18")
      (value "100nF")
      (footprint "eagle-import:C0603K")
      (libsource (lib "eagle-import") (part "C-EUC0603K"))
    )
    (comp (ref "C19")
      (value "47uF")
      (footprint "eagle-import:A_3216-18R")
      (libsource (lib "eagle-import") (part "CPOL-EUA/3216-18R"))
    )
    (comp (ref "C24")
      (value "100nF")
      (footprint "eagle-import:C0603K")
      (libsource (lib "eagle-import") (part "C-EUC0603K"))
    )
    (comp (ref "C28")
      (value "100nF")
      (footprint "eagle-import:C0603K")
      (libsource (lib "eagle-import") (part "C-EUC0603K"))
    )
    (comp (ref "C29")
      (value "100nF")
      (footprint "eagle-import:C0603K")
      (libsource (lib "eagle-import") (part "C-EUC0603K"))
    )
    (comp (ref "C31")
      (value "47uF")
      (footprint "eagle-import:A_3216-18R")
      (libsource (lib "eagle-import") (part "CPOL-EUA/3216-18R"))
    )
    (comp (ref "C32")
      (value "47uF")
      (footprint "eagle-import:A_3216-18R")
      (libsource (lib "eagle-import") (part "CPOL-EUA/3216-18R"))
    )
    (comp (ref "C33")
      (value "100nF")
      (footprint "eagle-import:C0603K")
      (libsource (lib "eagle-import") (part "C-EUC0603K"))
    )
    (comp (ref "C34")
      (value "47uF")
      (footprint "eagle-import:A_3216-18R")
      (libsource (lib "eagle-import") (part "CPOL-EUA/3216-18R"))
    )
    (comp (ref "C35")
      (value "100nF")
      (footprint "eagle-import:C0603K")
      (libsource (lib "eagle-import") (part "C-EUC0603K"))
    )
    (comp (ref "C36")
      (value "100nF")
      (footprint "eagle-import:C0603K")
      (libsource (lib "eagle-import") (part "C-EUC0603K"))
    )
    (comp (ref "C37")
      (value "33nF")
      (footprint "eagle-import:C0603K")
      (libsource (lib "eagle-import") (part "C-EUC0603K"))
    )
    (comp (ref "C38")
      (value "10nF")
      (footprint "eagle-import:C0603K")
      (libsource (lib "eagle-import") (part "C-EUC0603K"))
    )
    (comp (ref "C39")
      (value "100nF")
      (footprint "eagle-import:C0603K")
      (libsource (lib "eagle-import") (part "C-EUC0603K"))
    )
    (comp (ref "C40")
      (value "100nF")
      (footprint "eagle-import:C0603K")
      (libsource (lib "eagle-import") (part "C-EUC0603K"))
    )
    (comp (ref "C41")
      (value "47uF")
      (footprint "eagle-import:A_3216-18R")
      (libsource (lib "eagle-import") (part "CPOL-EUA/3216-18R"))
    )
    (comp (ref "C45")
      (value "100nF")
      (footprint "eagle-import:C0603K")
      (libsource (lib "eagle-import") (part "C-EUC0603K"))
    )
    (comp (ref "C46")
      (value "100nF")
      (footprint "eagle-import:C0603K")
      (libsource (lib "eagle-import") (part "C-EUC0603K"))
    )
    (comp (ref "C47")
      (value "47uF")
      (footprint "eagle-import:A_3216-18R")
      (libsource (lib "eagle-import") (part "CPOL-EUA/3216-18R"))
    )
    (comp (ref "C48")
      (value "100nF")
      (footprint "eagle-import:C0603K")
      (libsource (lib "eagle-import") (part "C-EUC0603K"))
    )
    (comp (ref "C49")
      (value "100nF")
      (footprint "eagle-import:C0603K")
      (libsource (lib "eagle-import") (part "C-EUC0603K"))
    )
    (comp (ref "C50")
      (value "47uF")
      (footprint "eagle-import:A_3216-18R")
      (libsource (lib "eagle-import") (part "CPOL-EUA/3216-18R"))
    )
    (comp (ref "C51")
      (value "47uF")
      (footprint "eagle-import:A_3216-18R")
      (libsource (lib "eagle-import") (part "CPOL-EUA/3216-18R"))
    )
    (comp (ref "C52")
      (value "47uF")
      (footprint "eagle-import:A_3216-18R")
      (libsource (lib "eagle-import") (part "CPOL-EUA/3216-18R"))
    )
    (comp (ref "C53")
      (value "100nF")
      (footprint "eagle-import:C0603K")
      (libsource (lib "eagle-import") (part "C-EUC0603K"))
    )
    (comp (ref "C54")
      (value "47uF")
      (footprint "eagle-import:A_3216-18R")
      (libsource (lib "eagle-import") (part "CPOL-EUA/3216-18R"))
    )
    (comp (ref "C55")
      (value "100nF")
      (footprint "eagle-import:C0603K")
      (libsource (lib "eagle-import") (part "C-EUC0603K"))
    )
    (comp (ref "C59")
      (value "47uF")
      (footprint "eagle-import:A_3216-18R")
      (libsource (lib "eagle-import") (part "CPOL-EUA/3216-18R"))
    )
    (comp (ref "C60")
      (value "100nF")
      (footprint "eagle-import:C0603K")
      (libsource (lib "eagle-import") (part "C-EUC0603K"))
    )
    (comp (ref "C61")
      (value "100nF")
      (footprint "eagle-import:C0603K")
      (libsource (lib "eagle-import") (part "C-EUC0603K"))
    )
    (comp (ref "C65")
      (value "33nF")
      (footprint "eagle-import:C0603K")
      (libsource (lib "eagle-import") (part "C-EUC0603K"))
    )
    (comp (ref "C66")
      (value "47uF")
      (footprint "eagle-import:A_3216-18R")
      (libsource (lib "eagle-import") (part "CPOL-EUA/3216-18R"))
    )
    (comp (ref "D3")
      (value "SS54B")
      (footprint "eagle-import:SMB")
      (fields (field (name "MANUFACTURER") "JCET") (field (name "CREATED_BY") "PCBLayout.com"))
      (libsource (lib "eagle-import") (part "SS54B"))
    )
    (comp (ref "D5")
      (value "SS54B")
      (footprint "eagle-import:SMB")
      (fields (field (name "MANUFACTURER") "JCET") (field (name "CREATED_BY") "PCBLayout.com"))
      (libsource (lib "eagle-import") (part "SS54B"))
    )
    (comp (ref "FB1")
      (value "600Ω")
      (footprint "eagle-import:0805")
      (libsource (lib "eagle-import") (part "FERRITE_BEAD-0805-600Ω-100MHZ"))
    )
    (comp (ref "FB2")
      (value "600Ω")
      (footprint "eagle-import:0805")
      (libsource (lib "eagle-import") (part "FERRITE_BEAD-0805-600Ω-100MHZ"))
    )
    (comp (ref "FB3")
      (value "600Ω")
      (footprint "eagle-import:0805")
      (libsource (lib "eagle-import") (part "FERRITE_BEAD-0805-600Ω-100MHZ"))
    )
    (comp (ref "FB4")
      (value "600Ω")
      (footprint "eagle-import:0805")
      (libsource (lib "eagle-import") (part "FERRITE_BEAD-0805-600Ω-100MHZ"))
    )
    (comp (ref "IC3")
      (value "MCP6001T_SOT23")
      (footprint "eagle-import:SOT95P280X145-5N")
      (fields (field (name "MANUFACTURER") "Microchip Technology") (field (name "MPN") "Generic"))
      (libsource (lib "eagle-import") (part "MCP6001T_SOT23"))
    )
    (comp (ref "IC4")
      (value "LD398518RG")
      (footprint "eagle-import:TSOT23-5L")
      (libsource (lib "eagle-import") (part "LD3985G18R"))
    )
    (comp (ref "R3")
      (value "270k")
      (footprint "eagle-import:R0402")
      (libsource (lib "eagle-import") (part "R-US_R0402"))
    )
    (comp (ref "R6")
      (value "0")
      (footprint "eagle-import:R0402")
      (libsource (lib "eagle-import") (part "R-US_R0402"))
    )
    (comp (ref "R7")
      (value "10k")
      (footprint "eagle-import:R0402")
      (libsource (lib "eagle-import") (part "R-US_R0402"))
    )
    (comp (ref "R10")
      (value "100k")
      (footprint "eagle-import:R0402")
      (libsource (lib "eagle-import") (part "R-US_R0402"))
    )
    (comp (ref "R11")
      (value "0")
      (footprint "eagle-import:R0402")
      (libsource (lib "eagle-import") (part "R-US_R0402"))
    )
    (comp (ref "R12")
      (value "27k")
      (footprint "eagle-import:R0402")
      (libsource (lib "eagle-import") (part "R-US_R0402"))
    )
    (comp (ref "R13")
      (value "1M")
      (footprint "eagle-import:R0402")
      (libsource (lib "eagle-import") (part "R-US_R0402"))
    )
    (comp (ref "R14")
      (value "0")
      (footprint "eagle-import:R0402")
      (libsource (lib "eagle-import") (part "R-US_R0402"))
    )
    (comp (ref "R15")
      (value "4.7k")
      (footprint "eagle-import:R0402")
      (libsource (lib "eagle-import") (part "R-US_R0402"))
    )
    (comp (ref "R16")
      (value "270k")
      (footprint "eagle-import:R0402")
      (libsource (lib "eagle-import") (part "R-US_R0402"))
    )
    (comp (ref "R19")
      (value "50k")
      (footprint "eagle-import:R0402")
      (libsource (lib "eagle-import") (part "R-US_R0402"))
    )
    (comp (ref "R26")
      (value "22")
      (footprint "eagle-import:R0402")
      (libsource (lib "eagle-import") (part "R-US_R0402"))
    )
    (comp (ref "R27")
      (value "22")
      (footprint "eagle-import:R0402")
      (libsource (lib "eagle-import") (part "R-US_R0402"))
    )
    (comp (ref "R38")
      (value "0")
      (footprint "eagle-import:R0402")
      (libsource (lib "eagle-import") (part "R-US_R0402"))
    )
    (comp (ref "R39")
      (value "10k")
      (footprint "eagle-import:R0402")
      (libsource (lib "eagle-import") (part "R-US_R0402"))
    )
    (comp (ref "R40")
      (value "80k")
      (footprint "eagle-import:R0402")
      (libsource (lib "eagle-import") (part "R-US_R0402"))
    )
    (comp (ref "R41")
      (value "0")
      (footprint "eagle-import:R0402")
      (libsource (lib "eagle-import") (part "R-US_R0402"))
    )
    (comp (ref "R42")
      (value "270k")
      (footprint "eagle-import:R0402")
      (libsource (lib "eagle-import") (part "R-US_R0402"))
    )
    (comp (ref "R43")
      (value "50k")
      (footprint "eagle-import:R0402")
      (libsource (lib "eagle-import") (part "R-US_R0402"))
    )
    (comp (ref "R44")
      (value "0")
      (footprint "eagle-import:M0805")
      (libsource (lib "eagle-import") (part "R-US_M0805"))
    )
    (comp (ref "R57")
      (value "5.11k")
      (footprint "eagle-import:R0402")
      (libsource (lib "eagle-import") (part "R-US_R0402"))
    )
    (comp (ref "U$5")
      (value "6.8uH")
      (footprint "eagle-import:0630CDMCCDS-4R7MC")
      (fields (field (name "MF") "Sumida") (field (name "MP") "0630CDMCCDS-4R7MC"))
      (libsource (lib "eagle-import") (part "0630CDMCCDS-4R7MC"))
    )
    (comp (ref "U$9")
      (value "4.7uH")
      (footprint "eagle-import:0630CDMCCDS-4R7MC")
      (fields (field (name "MF") "Sumida") (field (name "MP") "0630CDMCCDS-4R7MC"))
      (libsource (lib "eagle-import") (part "0630CDMCCDS-4R7MC"))
    )
    (comp (ref "U4")
      (value "TPS62933PDRLR")
      (footprint "eagle-import:SOFL50P160X60-8N")
      (fields (field (name "MF") "Texas Instruments"))
      (libsource (lib "eagle-import") (part "TPS62933PDRLR"))
    )
    (comp (ref "U6")
      (value "TPS62933PDRLR")
      (footprint "eagle-import:SOFL50P160X60-8N")
      (fields (field (name "MF") "Texas Instruments"))
      (libsource (lib "eagle-import") (part "TPS62933PDRLR"))
    )
    (comp (ref "U7")
      (value "3.3V")
      (footprint "eagle-import:SOT23-5")
      (libsource (lib "eagle-import") (part "V_REG_AP2112K-3.3V"))
    )
    (comp (ref "USB1")
      (value "10118193-0001LF")
      (footprint "eagle-import:MICRO-USB5+6P-SMD-0.65-B")
      (libsource (lib "eagle-import") (part "MICRO-USB-SMD-B-(10118193-0001LF)"))
    )
  )
  (nets
    (net (code "1") (name "+5V") (class "Default")
      (node (ref "C14") (pin "1") (pinfunction "1_1") (pintype "passive"))
      (node (ref "C15") (pin "1") (pinfunction "1_1") (pintype "passive"))
      (node (ref "C16") (pin "+") (pinfunction "+_+") (pintype "passive"))
      (node (ref "C19") (pin "+") (pinfunction "+_+") (pintype "passive"))
      (node (ref "C39") (pin "1") (pinfunction "1_1") (pintype "passive"))
      (node (ref "C40") (pin "1") (pinfunction "1_1") (pintype "passive"))
      (node (ref "C41") (pin "+") (pinfunction "+_+") (pintype "passive"))
      (node (ref "CN11") (pin "2") (pinfunction "2_2") (pintype "bidirectional"))
      (node (ref "CN5") (pin "1") (pinfunction "1_1") (pintype "bidirectional"))
      (node (ref "CN6") (pin "2") (pinfunction "2_2") (pintype "bidirectional"))
      (node (ref "CN9") (pin "2") (pinfunction "2_2") (pintype "bidirectional"))
      (node (ref "D5") (pin "C") (pinfunction "C_C") (pintype "passive"))
      (node (ref "FB1") (pin "1") (pinfunction "1_1") (pintype "passive"))
      (node (ref "FB3") (pin "1") (pinfunction "1_1") (pintype "passive"))
      (node (ref "IC1") (pin "21") (pinfunction "AVDD_21") (pintype "bidirectional"))
      (node (ref "IC1") (pin "24") (pinfunction "PVDD_24") (pintype "bidirectional"))
      (node (ref "IC1") (pin "3") (pinfunction "DVDD_3") (pintype "bidirectional"))
      (node (ref "R10") (pin "1") (pinfunction "1_1") (pintype "passive"))
      (node (ref "R32") (pin "2") (pinfunction "2_2") (pintype "passive"))
      (node (ref "R33") (pin "2") (pinfunction "2_2") (pintype "passive"))
      (node (ref "R34") (pin "2") (pinfunction "2_2") (pintype "passive"))
      (node (ref "R35") (pin "1") (pinfunction "1_1") (pintype "passive"))
      (node (ref "R51") (pin "2") (pinfunction "2_2") (pintype "passive"))
      (node (ref "U$5") (pin "P$1") (pinfunction "P$1_P$1") (pintype "bidirectional"))
    )
    (net (code "2") (name "0-~{BOOT}") (class "Default")
      (node (ref "BOOT") (pin "TP") (pinfunction "TP_TP") (pintype "input"))
      (node (ref "Q2") (pin "6") (pinfunction "C_6") (pintype "passive"))
      (node (ref "R9") (pin "1") (pinfunction "1_1") (pintype "passive"))
      (node (ref "U3") (pin "23") (pinfunction "(ADC2:1/TOUCH1/RTC11/CLK_OUT1)GPIO0_23") (pintype "bidirectional"))
    )
    (net (code "3") (name "2-STAT_LED") (class "Default")
      (node (ref "LED3") (pin "A") (pinfunction "A_A") (pintype "passive"))
      (node (ref "U3") (pin "22") (pinfunction "(ADC2:2/TOUCH2/RTC12/SPIWP)GPIO2_22") (pintype "bidirectional"))
    )
    (net (code "4") (name "3.3V") (class "Default")
      (node (ref "C20") (pin "1") (pinfunction "1_1") (pintype "passive"))
      (node (ref "C21") (pin "1") (pinfunction "1_1") (pintype "passive"))
      (node (ref "C22") (pin "1") (pinfunction "1_1") (pintype "passive"))
      (node (ref "C23") (pin "1") (pinfunction "1_1") (pintype "passive"))
      (node (ref "C25") (pin "1") (pinfunction "1_1") (pintype "passive"))
      (node (ref "FB4") (pin "2") (pinfunction "2_2") (pintype "passive"))
      (node (ref "R1") (pin "2") (pinfunction "2_2") (pintype "passive"))
      (node (ref "R9") (pin "2") (pinfunction "2_2") (pintype "passive"))
      (node (ref "U3") (pin "1") (pinfunction "VDDA_1") (pintype "bidirectional"))
      (node (ref "U3") (pin "19") (pinfunction "VDD3P3_RTC_19") (pintype "bidirectional"))
      (node (ref "U3") (pin "26") (pinfunction "VDD3P3_SDIO_26") (pintype "bidirectional"))
      (node (ref "U3") (pin "3") (pinfunction "VDDA3P3_3") (pintype "bidirectional"))
      (node (ref "U3") (pin "37") (pinfunction "VDD3P3_CPU_37") (pintype "bidirectional"))
      (node (ref "U3") (pin "4") (pinfunction "VDDA3P3_4") (pintype "bidirectional"))
      (node (ref "U3") (pin "43") (pinfunction "VDDA_43") (pintype "bidirectional"))
      (node (ref "U3") (pin "46") (pinfunction "VDDA_46") (pintype "bidirectional"))
      (node (ref "U5") (pin "8") (pinfunction "VDD_8") (pintype "bidirectional"))
    )
    (net (code "5") (name "3V3") (class "Default")
      (node (ref "C17") (pin "1") (pinfunction "1_1") (pintype "passive"))
      (node (ref "C18") (pin "1") (pinfunction "1_1") (pintype "passive"))
      (node (ref "C24") (pin "1") (pinfunction "1_1") (pintype "passive"))
      (node (ref "C43") (pin "1") (pinfunction "1_1") (pintype "passive"))
      (node (ref "C48") (pin "1") (pinfunction "1_1") (pintype "passive"))
      (node (ref "C49") (pin "1") (pinfunction "1_1") (pintype "passive"))
      (node (ref "C50") (pin "+") (pinfunction "+_+") (pintype "passive"))
      (node (ref "C51") (pin "+") (pinfunction "+_+") (pintype "passive"))
      (node (ref "C52") (pin "+") (pinfunction "+_+") (pintype "passive"))
      (node (ref "C53") (pin "1") (pinfunction "1_1") (pintype "passive"))
      (node (ref "C54") (pin "+") (pinfunction "+_+") (pintype "passive"))
      (node (ref "C55") (pin "1") (pinfunction "1_1") (pintype "passive"))
      (node (ref "C66") (pin "+") (pinfunction "+_+") (pintype "passive"))
      (node (ref "CN10") (pin "4") (pinfunction "4_4") (pintype "bidirectional"))
      (node (ref "CN9") (pin "4") (pinfunction "4_4") (pintype "bidirectional"))
      (node (ref "D1") (pin "A") (pinfunction "A_A") (pintype "passive"))
      (node (ref "FB2") (pin "1") (pinfunction "1_1") (pintype "passive"))
      (node (ref "FB4") (pin "1") (pinfunction "1_1") (pintype "passive"))
      (node (ref "IC3") (pin "5") (pinfunction "VDD_5") (pintype "bidirectional"))
      (node (ref "R22") (pin "1") (pinfunction "1_1") (pintype "passive"))
      (node (ref "R44") (pin "2") (pinfunction "2_2") (pintype "passive"))
      (node (ref "R45") (pin "1") (pinfunction "1_1") (pintype "passive"))
      (node (ref "R46") (pin "1") (pinfunction "1_1") (pintype "passive"))
      (node (ref "R47") (pin "1") (pinfunction "1_1") (pintype "passive"))
      (node (ref "R48") (pin "1") (pinfunction "1_1") (pintype "passive"))
      (node (ref "R49") (pin "1") (pinfunction "1_1") (pintype "passive"))
      (node (ref "R50") (pin "1") (pinfunction "1_1") (pintype "passive"))
      (node (ref "SD1") (pin "4") (pinfunction "VDD_4") (pintype "power_in"))
      (node (ref "U1") (pin "A6") (pinfunction "VDDLDO_A6") (pintype "power_in"))
      (node (ref "U1") (pin "C17") (pinfunction "VDDLDO_C17") (pintype "power_in"))
      (node (ref "U1") (pin "E11") (pinfunction "VDD_1_E11") (pintype "power_in"))
      (node (ref "U1") (pin "E6") (pinfunction "VDD_1_E6") (pintype "power_in"))
      (node (ref "U1") (pin "E7") (pinfunction "PDR_ON_E7") (pintype "input"))
      (node (ref "U1") (pin "E9") (pinfunction "VDD_1_E9") (pintype "power_in"))
      (node (ref "U1") (pin "F17") (pinfunction "VDD33USB_F17") (pintype "power_in"))
      (node (ref "U1") (pin "F5") (pinfunction "VDD_1_F5") (pintype "power_in"))
      (node (ref "U1") (pin "G13") (pinfunction "VDD_1_G13") (pintype "power_in"))
      (node (ref "U1") (pin "G17") (pinfunction "VDD50USB_G17") (pintype "power_in"))
      (node (ref "U1") (pin "G5") (pinfunction "VDD_1_G5") (pintype "power_in"))
      (node (ref "U1") (pin "H13") (pinfunction "VDD_1_H13") (pintype "power_in"))
      (node (ref "U1") (pin "H5") (pinfunction "VDD_1_H5") (pintype "power_in"))
      (node (ref "U1") (pin "J13") (pinfunction "VDD_1_J13") (pintype "power_in"))
      (node (ref "U1") (pin "K13") (pinfunction "VDD_1_K13") (pintype "power_in"))
      (node (ref "U1") (pin "K5") (pinfunction "VDD_2_K5") (pintype "power_in"))
      (node (ref "U1") (pin "L1") (pinfunction "VDDA_L1") (pintype "power_in"))
      (node (ref "U1") (pin "L13") (pinfunction "VDD_1_L13") (pintype "power_in"))
      (node (ref "U1") (pin "L5") (pinfunction "VDD_2_L5") (pintype "power_in"))
      (node (ref "U1") (pin "M1") (pinfunction "VREF+_M1") (pintype "input"))
      (node (ref "U1") (pin "M13") (pinfunction "VDD_2_M13") (pintype "power_in"))
      (node (ref "U1") (pin "M5") (pinfunction "VDD_2_M5") (pintype "power_in"))
      (node (ref "U1") (pin "N10") (pinfunction "VDD_2_N10") (pintype "power_in"))
      (node (ref "U1") (pin "N11") (pinfunction "VDD_2_N11") (pintype "power_in"))
      (node (ref "U1") (pin "N12") (pinfunction "VDD_2_N12") (pintype "power_in"))
      (node (ref "U1") (pin "N7") (pinfunction "VDD_2_N7") (pintype "power_in"))
      (node (ref "U1") (pin "N8") (pinfunction "VDD_2_N8") (pintype "power_in"))
      (node (ref "U1") (pin "P17") (pinfunction "VDD_2_P17") (pintype "power_in"))
      (node (ref "U1") (pin "U12") (pinfunction "VDDLDO_U12") (pintype "power_in"))
      (node (ref "U10") (pin "8") (pinfunction "VDD_8") (pintype "bidirectional"))
      (node (ref "U7") (pin "5") (pinfunction "OUT_5") (pintype "passive"))
    )
    (net (code "6") (name "3V3_SEN") (class "Default")
      (node (ref "C45") (pin "1") (pinfunction "1_1") (pintype "passive"))
      (node (ref "C46") (pin "1") (pinfunction "1_1") (pintype "passive"))
      (node (ref "C47") (pin "+") (pinfunction "+_+") (pintype "passive"))
      (node (ref "C59") (pin "+") (pinfunction "+_+") (pintype "passive"))
      (node (ref "C60") (pin "1") (pinfunction "1_1") (pintype "passive"))
      (node (ref "FB2") (pin "2") (pinfunction "2_2") (pintype "passive"))
      (node (ref "IC2") (pin "6") (pinfunction "VDDIO_6") (pintype "input"))
      (node (ref "IC2") (pin "8") (pinfunction "VDD_8") (pintype "power_in"))
      (node (ref "IC4") (pin "5") (pinfunction "VO_5") (pintype "output"))
      (node (ref "R23") (pin "1") (pinfunction "1_1") (pintype "passive"))
      (node (ref "R24") (pin "1") (pinfunction "1_1") (pintype "passive"))
      (node (ref "R25") (pin "2") (pinfunction "2_2") (pintype "passive"))
      (node (ref "R28") (pin "1") (pinfunction "1_1") (pintype "passive"))
      (node (ref "R29") (pin "1") (pinfunction "1_1") (pintype "passive"))
      (node (ref "R30") (pin "1") (pinfunction "1_1") (pintype "passive"))
      (node (ref "U2") (pin "13") (pinfunction "VDD_13") (pintype "power_in"))
      (node (ref "U2") (pin "8") (pinfunction "VLOGIC_8") (pintype "power_in"))
    )
    (net (code "7") (name "32-G5{slash}RTC") (class "Default")
      (node (ref "C9") (pin "2") (pinfunction "2_2") (pintype "passive"))
      (node (ref "U3") (pin "12") (pinfunction "32K_XP(GPIO32/ADC1:4/TOUCH9/RTC9)_12") (pintype "bidirectional"))
      (node (ref "Y2") (pin "P$1") (pinfunction "1_P$1") (pintype "passive"))
    )
    (net (code "8") (name "33-G6{slash}RTC") (class "Default")
      (node (ref "C26") (pin "2") (pinfunction "2_2") (pintype "passive"))
      (node (ref "U3") (pin "13") (pinfunction "32K_XN(GPIO33/ADC1:5/TOUCH8/RTC8)_13") (pintype "bidirectional"))
      (node (ref "Y2") (pin "P$2") (pinfunction "2_P$2") (pintype "passive"))
    )
    (net (code "9") (name "39-BATT{slash}3") (class "Default")
      (node (ref "C2") (pin "2") (pinfunction "2_2") (pintype "passive"))
      (node (ref "U3") (pin "8") (pinfunction "SENSOR_VN(GPI39/ADC1:3/RTC3)_8") (pintype "bidirectional"))
    )
    (net (code "10") (name "A-G-INT") (class "Default")
      (node (ref "R25") (pin "1") (pinfunction "1_1") (pintype "passive"))
      (node (ref "U2") (pin "12") (pinfunction "INT_12") (pintype "output"))
    )
    (net (code "11") (name "BARO_SCL") (class "Default")
      (node (ref "IC2") (pin "4") (pinfunction "SCK_4") (pintype "input"))
      (node (ref "R30") (pin "2") (pinfunction "2_2") (pintype "passive"))
      (node (ref "U1") (pin "D5") (pinfunction "PB8/TIM16_CH1/TIM4_CH3/DFSDM1_CKIN7/I2C1_SCL/I2C4_SCL/SDMMC1_CKIN/UART4_RX/FDCAN1_RX/SDMMC2_D4/ETH_MII_TXD3/SDMMC1_D4/DCMI_D6/LCD_B6/EVENTOUT_D5") (pintype "bidirectional"))
    )
    (net (code "12") (name "BARO_SDA") (class "Default")
      (node (ref "IC2") (pin "3") (pinfunction "SDI_3") (pintype "bidirectional"))
      (node (ref "R29") (pin "2") (pinfunction "2_2") (pintype "passive"))
      (node (ref "U1") (pin "D4") (pinfunction "PB9/TIM17_CH1/TIM4_CH4/DFSDM1_DATIN7/I2C1_SDA/SPI2_NSS/I2S2_WS/I2C4_SDA/SDMMC1_CDIR/UART4_TX/FDCAN1_TX/SDMMC2_D5/I2C4_SMBA/SDMMC1_D5/DCMI_D7/LCD_B7/EVENTOUT_D4") (pintype "bidirectional"))
    )
    (net (code "13") (name "BOOT0") (class "Default")
      (node (ref "R20") (pin "1") (pinfunction "1_1") (pintype "passive"))
      (node (ref "SBOOT") (pin "TP") (pinfunction "TP_TP") (pintype "input"))
      (node (ref "U1") (pin "E8") (pinfunction "BOOT0_E8") (pintype "input"))
    )
    (net (code "14") (name "CVIN") (class "Default")
      (node (ref "C64") (pin "2") (pinfunction "2_2") (pintype "passive"))
      (node (ref "CN6") (pin "3") (pinfunction "3_3") (pintype "bidirectional"))
      (node (ref "R37") (pin "2") (pinfunction "2_2") (pintype "passive"))
    )
    (net (code "15") (name "CVOUT") (class "Default")
      (node (ref "CN6") (pin "4") (pinfunction "4_4") (pintype "bidirectional"))
      (node (ref "R36") (pin "2") (pinfunction "2_2") (pintype "passive"))
    )
    (net (code "16") (name "DAC1") (class "Default")
      (node (ref "DAC") (pin "TP") (pinfunction "TP_TP") (pintype "input"))
      (node (ref "U1") (pin "U3") (pinfunction "PA4/D1PWREN/TIM5_ETR/SPI1_NSS/I2S1_WS/SPI3_NSS/I2S3_WS/USART2_CK/SPI6_NSS/OTG_HS_SOF/DCMI_HSYNC/LCD_VSYNC/EVENTOUT_U3") (pintype "bidirectional"))
    )
    (net (code "17") (name "DTR") (class "Default")
      (node (ref "DTR") (pin "TP") (pinfunction "TP_TP") (pintype "input"))
      (node (ref "Q2") (pin "1") (pinfunction "E_1") (pintype "passive"))
      (node (ref "R17") (pin "1") (pinfunction "1_1") (pintype "passive"))
    )
    (net (code "18") (name "ESP_CLK") (class "Default")
      (node (ref "U1") (pin "A13") (pinfunction "PC10/HRTIM_EEV1/DFSDM1_CKIN5/SPI3_SCK/I2S3_CK/USART3_TX/UART4_TX/QUADSPI_BK1_IO1/SDMMC1_D2/DCMI_D8/LCD_R2/EVENTOUT_A13") (pintype "bidirectional"))
      (node (ref "U3") (pin "35") (pinfunction "(VSPICLK/HS1_DATA7)GPIO18_35") (pintype "bidirectional"))
    )
    (net (code "19") (name "ESP_CS") (class "Default")
      (node (ref "U1") (pin "E3") (pinfunction "PC13/EVENTOUT_E3") (pintype "bidirectional"))
      (node (ref "U3") (pin "34") (pinfunction "(VSPICS0/HS1_DATA6)GPIO5_34") (pintype "bidirectional"))
    )
    (net (code "20") (name "ESP_MISO") (class "Default")
      (node (ref "U1") (pin "B13") (pinfunction "PC11/HRTIM_FLT2/DFSDM1_DATIN5/SPI3_MISO/I2S3_SDI/USART3_RX/UART4_RX/QUADSPI_BK2_NCS/SDMMC1_D3/DCMI_D4/EVENTOUT_B13") (pintype "bidirectional"))
      (node (ref "U3") (pin "25") (pinfunction "(HS1_DATA4)GPIO16_25") (pintype "bidirectional"))
    )
    (net (code "21") (name "ESP_MOSI") (class "Default")
      (node (ref "U1") (pin "A5") (pinfunction "PB5/TIM17_BKIN/TIM3_CH2/HRTIM_EEV7/I2C1_SMBA/SPI1_MOSI/I2S1_SDO/I2C4_SMBA/SPI3_MOSI/I2S3_SDO/SPI6_MOSI/FDCAN2_RX/OTG_HS_ULPI_D7/ETH_PPS_OUT/FMC_SDCKE1/DCMI_D10/UART5_RX/EVENTOUT_A5") (pintype "bidirectional"))
      (node (ref "U3") (pin "27") (pinfunction "(HS1_DATA5)GPIO17_27") (pintype "bidirectional"))
    )
    (net (code "22") (name "FLASH_SCK") (class "Default")
      (node (ref "U3") (pin "31") (pinfunction "(GPIO6/SPICLK/HS1_CLK/U1CTS)SD_CLK_31") (pintype "bidirectional"))
      (node (ref "U5") (pin "6") (pinfunction "CLK_6") (pintype "bidirectional"))
    )
    (net (code "23") (name "FLASH_SCS") (class "Default")
      (node (ref "U3") (pin "30") (pinfunction "(GPIO11/SPICSO/HS1_CMD/U1RTS)SD_CMD_30") (pintype "bidirectional"))
      (node (ref "U5") (pin "1") (pinfunction "~{CS}_1") (pintype "bidirectional"))
    )
    (net (code "24") (name "FLASH_SDI") (class "Default")
      (node (ref "U3") (pin "33") (pinfunction "(GPIO8/SPID/HS1_DATA1)SD_DATA1_33") (pintype "bidirectional"))
      (node (ref "U5") (pin "5") (pinfunction "D0/DI_5") (pintype "bidirectional"))
    )
    (net (code "25") (name "FLASH_SDO") (class "Default")
      (node (ref "U3") (pin "32") (pinfunction "(GPIO7/SPI1/HS1_DATA0)SD_DATA0_32") (pintype "bidirectional"))
      (node (ref "U5") (pin "2") (pinfunction "D1/DO_2") (pintype "bidirectional"))
    )
    (net (code "26") (name "FLASH_SHD") (class "Default")
      (node (ref "U3") (pin "28") (pinfunction "(GPIO9/SPIHD/HS1_DATA2/U1RX)SD_DATA2_28") (pintype "bidirectional"))
      (node (ref "U5") (pin "7") (pinfunction "D3/~{HOLD}_7") (pintype "bidirectional"))
    )
    (net (code "27") (name "FLASH_SWP") (class "Default")
      (node (ref "U3") (pin "29") (pinfunction "(GPIO10/SPIWP/HS1_DATA3/U1TX)SD_DATA3_29") (pintype "bidirectional"))
      (node (ref "U5") (pin "3") (pinfunction "D2/~{WP}_3") (pintype "bidirectional"))
    )
    (net (code "28") (name "GND") (class "Default")
      (node (ref "C10") (pin "2") (pinfunction "2_2") (pintype "passive"))
      (node (ref "C11") (pin "2") (pinfunction "2_2") (pintype "passive"))
      (node (ref "C12") (pin "-") (pinfunction "-_-") (pintype "passive"))
      (node (ref "C13") (pin "-") (pinfunction "-_-") (pintype "passive"))
      (node (ref "C14") (pin "2") (pinfunction "2_2") (pintype "passive"))
      (node (ref "C15") (pin "2") (pinfunction "2_2") (pintype "passive"))
      (node (ref "C16") (pin "-") (pinfunction "-_-") (pintype "passive"))
      (node (ref "C17") (pin "2") (pinfunction "2_2") (pintype "passive"))
      (node (ref "C18") (pin "2") (pinfunction "2_2") (pintype "passive"))
      (node (ref "C19") (pin "-") (pinfunction "-_-") (pintype "passive"))
      (node (ref "C20") (pin "2") (pinfunction "2_2") (pintype "passive"))
      (node (ref "C21") (pin "2") (pinfunction "2_2") (pintype "passive"))
      (node (ref "C22") (pin "2") (pinfunction "2_2") (pintype "passive"))
      (node (ref "C23") (pin "2") (pinfunction "2_2") (pintype "passive"))
      (node (ref "C24") (pin "2") (pinfunction "2_2") (pintype "passive"))
      (node (ref "C25") (pin "2") (pinfunction "2_2") (pintype "passive"))
      (node (ref "C26") (pin "1") (pinfunction "1_1") (pintype "passive"))
      (node (ref "C28") (pin "2") (pinfunction "2_2") (pintype "passive"))
      (node (ref "C29") (pin "2") (pinfunction "2_2") (pintype "passive"))
      (node (ref "C3") (pin "1") (pinfunction "1_1") (pintype "passive"))
      (node (ref "C30") (pin "2") (pinfunction "2_2") (pintype "passive"))
      (node (ref "C31") (pin "-") (pinfunction "-_-") (pintype "passive"))
      (node (ref "C32") (pin "-") (pinfunction "-_-") (pintype "passive"))
      (node (ref "C33") (pin "2") (pinfunction "2_2") (pintype "passive"))
      (node (ref "C34") (pin "-") (pinfunction "-_-") (pintype "passive"))
      (node (ref "C35") (pin "2") (pinfunction "2_2") (pintype "passive"))
      (node (ref "C37") (pin "2") (pinfunction "2_2") (pintype "passive"))
      (node (ref "C38") (pin "2") (pinfunction "2_2") (pintype "passive"))
      (node (ref "C39") (pin "2") (pinfunction "2_2") (pintype "passive"))
      (node (ref "C4") (pin "1") (pinfunction "1_1") (pintype "passive"))
      (node (ref "C40") (pin "2") (pinfunction "2_2") (pintype "passive"))
      (node (ref "C41") (pin "-") (pinfunction "-_-") (pintype "passive"))
      (node (ref "C42") (pin "1") (pinfunction "1_1") (pintype "passive"))
      (node (ref "C43") (pin "2") (pinfunction "2_2") (pintype "passive"))
      (node (ref "C44") (pin "1") (pinfunction "1_1") (pintype "passive"))
      (node (ref "C45") (pin "2") (pinfunction "2_2") (pintype "passive"))
      (node (ref "C46") (pin "2") (pinfunction "2_2") (pintype "passive"))
      (node (ref "C47") (pin "-") (pinfunction "-_-") (pintype "passive"))
      (node (ref "C48") (pin "2") (pinfunction "2_2") (pintype "passive"))
      (node (ref "C49") (pin "2") (pinfunction "2_2") (pintype "passive"))
      (node (ref "C5") (pin "1") (pinfunction "1_1") (pintype "passive"))
      (node (ref "C50") (pin "-") (pinfunction "-_-") (pintype "passive"))
      (node (ref "C51") (pin "-") (pinfunction "-_-") (pintype "passive"))
      (node (ref "C52") (pin "-") (pinfunction "-_-") (pintype "passive"))
      (node (ref "C53") (pin "2") (pinfunction "2_2") (pintype "passive"))
      (node (ref "C54") (pin "-") (pinfunction "-_-") (pintype "passive"))
      (node (ref "C55") (pin "2") (pinfunction "2_2") (pintype "passive"))
      (node (ref "C56") (pin "1") (pinfunction "1_1") (pintype "passive"))
      (node (ref "C57") (pin "1") (pinfunction "1_1") (pintype "passive"))
      (node (ref "C58") (pin "2") (pinfunction "2_2") (pintype "passive"))
      (node (ref "C59") (pin "-") (pinfunction "-_-") (pintype "passive"))
      (node (ref "C6") (pin "2") (pinfunction "2_2") (pintype "passive"))
      (node (ref "C60") (pin "2") (pinfunction "2_2") (pintype "passive"))
      (node (ref "C65") (pin "2") (pinfunction "2_2") (pintype "passive"))
      (node (ref "C66") (pin "-") (pinfunction "-_-") (pintype "passive"))
      (node (ref "C7") (pin "2") (pinfunction "2_2") (pintype "passive"))
      (node (ref "C8") (pin "2") (pinfunction "2_2") (pintype "passive"))
      (node (ref "C9") (pin "1") (pinfunction "1_1") (pintype "passive"))
      (node (ref "CN1") (pin "1") (pinfunction "1_1") (pintype "bidirectional"))
      (node (ref "CN10") (pin "3") (pinfunction "3_3") (pintype "bidirectional"))
      (node (ref "CN11") (pin "1") (pinfunction "1_1") (pintype "bidirectional"))
      (node (ref "CN5") (pin "4") (pinfunction "4_4") (pintype "bidirectional"))
      (node (ref "CN6") (pin "1") (pinfunction "1_1") (pintype "bidirectional"))
      (node (ref "CN7") (pin "1") (pinfunction "1_1") (pintype "bidirectional"))
      (node (ref "CN9") (pin "1") (pinfunction "1_1") (pintype "bidirectional"))
      (node (ref "G") (pin "TP") (pinfunction "TP_TP") (pintype "input"))
      (node (ref "IC1") (pin "20") (pinfunction "AGND_20") (pintype "bidirectional"))
      (node (ref "IC1") (pin "23") (pinfunction "PGND_23") (pintype "bidirectional"))
      (node (ref "IC1") (pin "29") (pinfunction "THERMALPAD_29") (pintype "bidirectional"))
      (node (ref "IC1") (pin "4") (pinfunction "DGND_4") (pintype "bidirectional"))
      (node (ref "IC2") (pin "1") (pinfunction "GND_1") (pintype "power_in"))
      (node (ref "IC2") (pin "7") (pinfunction "GND_7") (pintype "power_in"))
      (node (ref "IC3") (pin "2") (pinfunction "VSS_2") (pintype "bidirectional"))
      (node (ref "IC4") (pin "2") (pinfunction "GND_2") (pintype "power_in"))
      (node (ref "LED1") (pin "C") (pinfunction "C_C") (pintype "passive"))
      (node (ref "LED2") (pin "C") (pinfunction "C_C") (pintype "passive"))
      (node (ref "R11") (pin "1") (pinfunction "1_1") (pintype "passive"))
      (node (ref "R12") (pin "1") (pinfunction "1_1") (pintype "passive"))
      (node (ref "R13") (pin "1") (pinfunction "1_1") (pintype "passive"))
      (node (ref "R19") (pin "1") (pinfunction "1_1") (pintype "passive"))
      (node (ref "R20") (pin "2") (pinfunction "2_2") (pintype "passive"))
      (node (ref "R31") (pin "1") (pinfunction "1_1") (pintype "passive"))
      (node (ref "R37") (pin "1") (pinfunction "1_1") (pintype "passive"))
      (node (ref "R39") (pin "1") (pinfunction "1_1") (pintype "passive"))
      (node (ref "R41") (pin "1") (pinfunction "1_1") (pintype "passive"))
      (node (ref "R43") (pin "1") (pinfunction "1_1") (pintype "passive"))
      (node (ref "R57") (pin "2") (pinfunction "2_2") (pintype "passive"))
      (node (ref "R7") (pin "1") (pinfunction "1_1") (pintype "passive"))
      (node (ref "R8") (pin "1") (pinfunction "1_1") (pintype "passive"))
      (node (ref "SD1") (pin "6") (pinfunction "VSS_6") (pintype "power_in"))
      (node (ref "SD1") (pin "S1") (pinfunction "S1_S1") (pintype "passive"))
      (node (ref "SD1") (pin "S2") (pinfunction "S2_S2") (pintype "passive"))
      (node (ref "SD1") (pin "S3") (pinfunction "S3_S3") (pintype "passive"))
      (node (ref "SD1") (pin "S4") (pinfunction "S4_S4") (pintype "passive"))
      (node (ref "T1") (pin "E") (pinfunction "E_E") (pintype "passive"))
      (node (ref "T2") (pin "E") (pinfunction "E_E") (pintype "passive"))
      (node (ref "U1") (pin "A1") (pinfunction "VSS_1_A1") (pintype "power_in"))
      (node (ref "U1") (pin "A17") (pinfunction "VSS_1_A17") (pintype "power_in"))
      (node (ref "U1") (pin "B2") (pinfunction "VSS_1_B2") (pintype "power_in"))
      (node (ref "U1") (pin "B6") (pinfunction "VSS_1_B6") (pintype "power_in"))
      (node (ref "U1") (pin "C10") (pinfunction "VSS_1_C10") (pintype "power_in"))
      (node (ref "U1") (pin "C13") (pinfunction "VSS_1_C13") (pintype "power_in"))
      (node (ref "U1") (pin "C16") (pinfunction "VSS_1_C16") (pintype "power_in"))
      (node (ref "U1") (pin "F2") (pinfunction "VSS_1_F2") (pintype "power_in"))
      (node (ref "U1") (pin "G10") (pinfunction "VSS_2_G10") (pintype "power_in"))
      (node (ref "U1") (pin "G11") (pinfunction "VSS_2_G11") (pintype "power_in"))
      (node (ref "U1") (pin "G16") (pinfunction "VSS_2_G16") (pintype "power_in"))
      (node (ref "U1") (pin "G7") (pinfunction "VSS_2_G7") (pintype "power_in"))
      (node (ref "U1") (pin "G8") (pinfunction "VSS_2_G8") (pintype "power_in"))
      (node (ref "U1") (pin "G9") (pinfunction "VSS_2_G9") (pintype "power_in"))
      (node (ref "U1") (pin "H10") (pinfunction "VSS_2_H10") (pintype "power_in"))
      (node (ref "U1") (pin "H11") (pinfunction "VSS_3_H11") (pintype "power_in"))
      (node (ref "U1") (pin "H7") (pinfunction "VSS_2_H7") (pintype "power_in"))
      (node (ref "U1") (pin "H8") (pinfunction "VSS_2_H8") (pintype "power_in"))
      (node (ref "U1") (pin "H9") (pinfunction "VSS_2_H9") (pintype "power_in"))
      (node (ref "U1") (pin "J10") (pinfunction "VSS_3_J10") (pintype "power_in"))
      (node (ref "U1") (pin "J11") (pinfunction "VSS_3_J11") (pintype "power_in"))
      (node (ref "U1") (pin "J16") (pinfunction "VSS_1_J16") (pintype "power_in"))
      (node (ref "U1") (pin "J17") (pinfunction "VSS_1_J17") (pintype "power_in"))
      (node (ref "U1") (pin "J3") (pinfunction "VSS_1_J3") (pintype "power_in"))
      (node (ref "U1") (pin "J7") (pinfunction "VSS_3_J7") (pintype "power_in"))
      (node (ref "U1") (pin "J8") (pinfunction "VSS_3_J8") (pintype "power_in"))
      (node (ref "U1") (pin "J9") (pinfunction "VSS_3_J9") (pintype "power_in"))
      (node (ref "U1") (pin "K10") (pinfunction "VSS_3_K10") (pintype "power_in"))
      (node (ref "U1") (pin "K11") (pinfunction "VSS_3_K11") (pintype "power_in"))
      (node (ref "U1") (pin "K15") (pinfunction "VSS_2_K15") (pintype "power_in"))
      (node (ref "U1") (pin "K7") (pinfunction "VSS_3_K7") (pintype "power_in"))
      (node (ref "U1") (pin "K8") (pinfunction "VSS_3_K8") (pintype "power_in"))
      (node (ref "U1") (pin "K9") (pinfunction "VSS_3_K9") (pintype "power_in"))
      (node (ref "U1") (pin "L10") (pinfunction "VSS_3_L10") (pintype "power_in"))
      (node (ref "U1") (pin "L11") (pinfunction "VSS_3_L11") (pintype "power_in"))
      (node (ref "U1") (pin "L15") (pinfunction "VSS_2_L15") (pintype "power_in"))
      (node (ref "U1") (pin "L7") (pinfunction "VSS_3_L7") (pintype "power_in"))
      (node (ref "U1") (pin "L8") (pinfunction "VSS_3_L8") (pintype "power_in"))
      (node (ref "U1") (pin "L9") (pinfunction "VSS_3_L9") (pintype "power_in"))
      (node (ref "U1") (pin "M15") (pinfunction "VSS_2_M15") (pintype "power_in"))
      (node (ref "U1") (pin "N1") (pinfunction "VREF-_N1") (pintype "input"))
      (node (ref "U1") (pin "N16") (pinfunction "VSS_1_N16") (pintype "power_in"))
      (node (ref "U1") (pin "P1") (pinfunction "VSSA_P1") (pintype "power_in"))
      (node (ref "U1") (pin "R4") (pinfunction "VSS_1_R4") (pintype "power_in"))
      (node (ref "U1") (pin "R8") (pinfunction "VSS_2_R8") (pintype "power_in"))
      (node (ref "U1") (pin "T12") (pinfunction "VSS_1_T12") (pintype "power_in"))
      (node (ref "U1") (pin "U1") (pinfunction "VSS_2_U1") (pintype "power_in"))
      (node (ref "U1") (pin "U17") (pinfunction "VSS_1_U17") (pintype "power_in"))
      (node (ref "U10") (pin "4") (pinfunction "GND_4") (pintype "bidirectional"))
      (node (ref "U2") (pin "1") (pinfunction "CLKIN_1") (pintype "input"))
      (node (ref "U2") (pin "11") (pinfunction "FSYNC_11") (pintype "input"))
      (node (ref "U2") (pin "18") (pinfunction "GND_18") (pintype "power_in"))
      (node (ref "U2") (pin "25") (pinfunction "EP_25") (pintype "power_in"))
      (node (ref "U2") (pin "9") (pinfunction "AD0_9") (pintype "bidirectional"))
      (node (ref "U3") (pin "EP") (pinfunction "GND_EP") (pintype "bidirectional"))
      (node (ref "U4") (pin "4") (pinfunction "GND_4") (pintype "power_in"))
      (node (ref "U5") (pin "4") (pinfunction "GND_4") (pintype "bidirectional"))
      (node (ref "U6") (pin "4") (pinfunction "GND_4") (pintype "power_in"))
      (node (ref "U7") (pin "2") (pinfunction "GND_2") (pintype "input"))
      (node (ref "USB1") (pin "5") (pinfunction "GND_5") (pintype "bidirectional"))
      (node (ref "USB1") (pin "S1") (pinfunction "GND_S1") (pintype "bidirectional"))
      (node (ref "USB1") (pin "S2B") (pinfunction "GND_S2B") (pintype "bidirectional"))
      (node (ref "USB1") (pin "S2T") (pinfunction "GND_S2T") (pintype "bidirectional"))
      (node (ref "USB1") (pin "S3") (pinfunction "GND_S3") (pintype "bidirectional"))
      (node (ref "USB1") (pin "S4") (pinfunction "GND_S4") (pintype "bidirectional"))
      (node (ref "USB1") (pin "S5B") (pinfunction "GND_S5B") (pintype "bidirectional"))
      (node (ref "USB1") (pin "S5T") (pinfunction "GND_S5T") (pintype "bidirectional"))
      (node (ref "USB1") (pin "S6") (pinfunction "GND_S6") (pintype "bidirectional"))
      (node (ref "Y1") (pin "P2") (pinfunction "GND_P2") (pintype "power_in"))
      (node (ref "Y1") (pin "P4") (pinfunction "GND_P4") (pintype "power_in"))
      (node (ref "Y3") (pin "2") (pinfunction "GND_2") (pintype "power_in"))
      (node (ref "Y3") (pin "4") (pinfunction "GND_4") (pintype "power_in"))
      (node (ref "Y4") (pin "2") (pinfunction "GND_2") (pintype "power_in"))
      (node (ref "Y4") (pin "4") (pinfunction "GND_4") (pintype "power_in"))
    )
    (net (code "29") (name "I2C2_SCL") (class "Default")
      (node (ref "CN11") (pin "4") (pinfunction "4_4") (pintype "bidirectional"))
      (node (ref "U1") (pin "G3") (pinfunction "PF1/I2C2_SCL/FMC_A1/EVENTOUT_G3") (pintype "bidirectional"))
    )
    (net (code "30") (name "I2C2_SDA") (class "Default")
      (node (ref "CN11") (pin "3") (pinfunction "3_3") (pintype "bidirectional"))
      (node (ref "U1") (pin "G4") (pinfunction "PF0/I2C2_SDA/FMC_A0/EVENTOUT_G4") (pintype "bidirectional"))
    )
    (net (code "31") (name "IMU_SCL") (class "Default")
      (node (ref "R23") (pin "2") (pinfunction "2_2") (pintype "passive"))
      (node (ref "U1") (pin "E15") (pinfunction "PA8/MCO1/TIM1_CH1/HRTIM_CHB2/TIM8_BKIN2/I2C3_SCL/USART1_CK/OTG_FS_SOF/UART7_RX/TIM8_BKIN2_COMP12/LCD_B3/LCD_R6/EVENTOUT_E15") (pintype "bidirectional"))
      (node (ref "U2") (pin "23") (pinfunction "SCL_23") (pintype "bidirectional"))
    )
    (net (code "32") (name "IMU_SDA") (class "Default")
      (node (ref "R24") (pin "2") (pinfunction "2_2") (pintype "passive"))
      (node (ref "U1") (pin "E14") (pinfunction "PC9/MCO2/TIM3_CH4/TIM8_CH4/I2C3_SDA/I2S_CKIN/UART5_CTS/QUADSPI_BK1_IO0/LCD_G3/SWPMI_SUSPEND/SDMMC1_D1/DCMI_D3/LCD_B2/EVENTOUT_E14") (pintype "bidirectional"))
      (node (ref "U2") (pin "24") (pinfunction "SDA_24") (pintype "bidirectional"))
    )
    (net (code "33") (name "J-SWD-CLK") (class "Default")
      (node (ref "CN10") (pin "2") (pinfunction "2_2") (pintype "bidirectional"))
      (node (ref "U1") (pin "B14") (pinfunction "PA14/JTCK-SWCLK/EVENTOUT_B14") (pintype "bidirectional"))
    )
    (net (code "34") (name "J-SWD-IO") (class "Default")
      (node (ref "CN10") (pin "1") (pinfunction "1_1") (pintype "bidirectional"))
      (node (ref "U1") (pin "C15") (pinfunction "PA13/JTMS-SWDIO/EVENTOUT_C15") (pintype "bidirectional"))
    )
    (net (code "35") (name "LED_STATUS") (class "Default")
      (node (ref "R53") (pin "2") (pinfunction "2_2") (pintype "passive"))
      (node (ref "U1") (pin "U5") (pinfunction "PB0/TIM1_CH2N/TIM3_CH3/TIM8_CH2N/DFSDM1_CKOUT/UART4_CTS/LCD_R3/OTG_HS_ULPI_D1/ETH_MII_RXD2/LCD_G1/EVENTOUT_U5") (pintype "bidirectional"))
    )
    (net (code "36") (name "LED_STATUS2") (class "Default")
      (node (ref "R54") (pin "2") (pinfunction "2_2") (pintype "passive"))
      (node (ref "U1") (pin "L2") (pinfunction "PC0/DFSDM1_CKIN0/DFSDM1_DATIN4/SAI2_FS_B/OTG_HS_ULPI_STP/FMC_SDNWE/LCD_R5/EVENTOUT_L2") (pintype "bidirectional"))
    )
    (net (code "37") (name "MAX_CLK") (class "Default")
      (node (ref "IC1") (pin "10") (pinfunction "SCLK_10") (pintype "bidirectional"))
      (node (ref "U1") (pin "A15") (pinfunction "PI1/TIM8_BKIN2/SPI2_SCK/I2S2_CK/TIM8_BKIN2_COMP12/FMC_D25/DCMI_D8/LCD_G6/EVENTOUT_A15") (pintype "bidirectional"))
    )
    (net (code "38") (name "MAX_CS") (class "Default")
      (node (ref "R52") (pin "2") (pinfunction "2_2") (pintype "passive"))
      (node (ref "U1") (pin "A16") (pinfunction "PI0/TIM5_CH4/SPI2_NSS/I2S2_WS/FDCAN1_RXFD_MODE/FMC_D24/DCMI_D13/LCD_G5/EVENTOUT_A16") (pintype "bidirectional"))
    )
    (net (code "39") (name "MAX_MISO") (class "Default")
      (node (ref "IC1") (pin "11") (pinfunction "SDOUT_11") (pintype "bidirectional"))
      (node (ref "U1") (pin "M3") (pinfunction "PC2/CDSLEEP/DFSDM1_CKIN1/SPI2_MISO/I2S2_SDI/DFSDM1_CKOUT/OTG_HS_ULPI_DIR/ETH_MII_TXD2/FMC_SDNE0/EVENTOUT_M3") (pintype "bidirectional"))
    )
    (net (code "40") (name "MAX_MOSI") (class "Default")
      (node (ref "IC1") (pin "9") (pinfunction "SDIN_9") (pintype "bidirectional"))
      (node (ref "U1") (pin "C14") (pinfunction "PI3/TIM8_ETR/SPI2_MOSI/I2S2_SDO/FMC_D27/DCMI_D10/EVENTOUT_C14") (pintype "bidirectional"))
    )
    (net (code "41") (name "MAX_~{CS}") (class "Default")
      (node (ref "IC1") (pin "8") (pinfunction "~{CS}_8") (pintype "bidirectional"))
      (node (ref "R51") (pin "1") (pinfunction "1_1") (pintype "passive"))
      (node (ref "T2") (pin "C") (pinfunction "C_C") (pintype "passive"))
    )
    (net (code "42") (name "MLSO") (class "Default")
      (node (ref "IC1") (pin "12") (pinfunction "LOS_12") (pintype "bidirectional"))
      (node (ref "R35") (pin "2") (pinfunction "2_2") (pintype "passive"))
    )
    (net (code "43") (name "MMC_CLK") (class "Default")
      (node (ref "SD1") (pin "5") (pinfunction "CLK(SCLK)_5") (pintype "input"))
      (node (ref "U1") (pin "M2") (pinfunction "PC1/TRACED0/SAI1_D1/DFSDM1_DATIN0/DFSDM1_CKIN4/SPI2_MOSI/I2S2_SDO/SAI1_SD_A/SAI4_SD_A/SDMMC2_CK/SAI4_D1/ETH_MDC/MDIOS_MDC/EVENTOUT_M2") (pintype "bidirectional"))
    )
    (net (code "44") (name "MMC_CMD") (class "Default")
      (node (ref "R46") (pin "2") (pinfunction "2_2") (pintype "passive"))
      (node (ref "SD1") (pin "3") (pinfunction "CMD(DI)_3") (pintype "bidirectional"))
      (node (ref "U1") (pin "N5") (pinfunction "PA0/TIM2_CH1/TIM2_ETR/TIM5_CH1/TIM8_ETR/TIM15_BKIN/USART2_CTS/USART2_NSS/UART4_TX/SDMMC2_CMD/SAI2_SD_B/ETH_MII_CRS/EVENTOUT_N5") (pintype "bidirectional"))
    )
    (net (code "45") (name "MMC_D0") (class "Default")
      (node (ref "R48") (pin "2") (pinfunction "2_2") (pintype "passive"))
      (node (ref "SD1") (pin "7") (pinfunction "DAT0(DO)_7") (pintype "bidirectional"))
      (node (ref "U1") (pin "U15") (pinfunction "PB14/TIM1_CH2N/TIM12_CH1/TIM8_CH2N/USART1_TX/SPI2_MISO/I2S2_SDI/DFSDM1_DATIN2/USART3_RTS/USART3_DE/UART4_RTS/UART4_DE/SDMMC2_D0/OTG_HS_DM/EVENTOUT_U15") (pintype "bidirectional"))
    )
    (net (code "46") (name "MMC_D1") (class "Default")
      (node (ref "R50") (pin "2") (pinfunction "2_2") (pintype "passive"))
      (node (ref "SD1") (pin "8") (pinfunction "DAT1_8") (pintype "bidirectional"))
      (node (ref "U1") (pin "T15") (pinfunction "PB15/RTC_REFIN/TIM1_CH3N/TIM12_CH2/TIM8_CH3N/USART1_RX/SPI2_MOSI/I2S2_SDO/DFSDM1_CKIN2/UART4_CTS/SDMMC2_D1/OTG_HS_DP/EVENTOUT_T15") (pintype "bidirectional"))
    )
    (net (code "47") (name "MMC_D2") (class "Default")
      (node (ref "R49") (pin "2") (pinfunction "2_2") (pintype "passive"))
      (node (ref "SD1") (pin "1") (pinfunction "DAT2_1") (pintype "bidirectional"))
      (node (ref "U1") (pin "C6") (pinfunction "PB3/JTDO/TRACESWO/TIM2_CH2/HRTIM_FLT4/SPI1_SCK/I2S1_CK/SPI3_SCK/I2S3_CK/SPI6_SCK/SDMMC2_D2/CRS_SYNC/UART7_RX/EVENTOUT_C6") (pintype "bidirectional"))
    )
    (net (code "48") (name "MMC_~{CS}") (class "Default")
      (node (ref "R47") (pin "2") (pinfunction "2_2") (pintype "passive"))
      (node (ref "SD1") (pin "2") (pinfunction "CD/DAT3(~{CS})_2") (pintype "bidirectional"))
      (node (ref "U1") (pin "B7") (pinfunction "PB4/NJTRST/TIM16_BKIN/TIM3_CH1/HRTIM_EEV6/SPI1_MISO/I2S1_SDI/SPI3_MISO/I2S3_SDI/SPI2_NSS/I2S2_WS/SPI6_MISO/SDMMC2_D3/UART7_TX/EVENTOUT_B7") (pintype "bidirectional"))
    )
    (net (code "49") (name "MT1") (class "Default")
      (node (ref "CN7") (pin "2") (pinfunction "2_2") (pintype "bidirectional"))
      (node (ref "U1") (pin "T5") (pinfunction "PB1/TIM1_CH3N/TIM3_CH4/TIM8_CH3N/DFSDM1_DATIN1/LCD_R6/OTG_HS_ULPI_D2/ETH_MII_RXD3/LCD_G0/EVENTOUT_T5") (pintype "bidirectional"))
    )
    (net (code "50") (name "MT2") (class "Default")
      (node (ref "CN1") (pin "2") (pinfunction "2_2") (pintype "bidirectional"))
      (node (ref "U1") (pin "F14") (pinfunction "PC6/HRTIM_CHA1/TIM3_CH1/TIM8_CH1/DFSDM1_CKIN3/I2S2_MCK/USART6_TX/SDMMC1_D0DIR/FMC_NWAIT/SDMMC2_D6/SDMMC1_D6/DCMI_D0/LCD_HSYNC/EVENTOUT_F14") (pintype "bidirectional"))
    )
    (net (code "51") (name "MT3") (class "Default")
      (node (ref "CN1") (pin "3") (pinfunction "3_3") (pintype "bidirectional"))
      (node (ref "U1") (pin "F13") (pinfunction "PC7/TRGIO/HRTIM_CHA2/TIM3_CH2/TIM8_CH2/DFSDM1_DATIN3/I2S3_MCK/USART6_RX/SDMMC1_D123DIR/FMC_NE1/SDMMC2_D7/SWPMI_TX/SDMMC1_D7/DCMI_D1/LCD_G6/EVENTOUT_F13") (pintype "bidirectional"))
    )
    (net (code "52") (name "MT4") (class "Default")
      (node (ref "CN1") (pin "4") (pinfunction "4_4") (pintype "bidirectional"))
      (node (ref "U1") (pin "E13") (pinfunction "PC8/TRACED1/HRTIM_CHB1/TIM3_CH3/TIM8_CH3/USART6_CK/UART5_RTS/UART5_DE/FMC_NE2/FMC_NCE/SWPMI_RX/SDMMC1_D0/DCMI_D2/EVENTOUT_E13") (pintype "bidirectional"))
    )
    (net (code "53") (name "MT5") (class "Default")
      (node (ref "CN2") (pin "1") (pinfunction "1_1") (pintype "bidirectional"))
      (node (ref "U1") (pin "N4") (pinfunction "PA1/TIM2_CH2/TIM5_CH2/LPTIM3_OUT/TIM15_CH1N/USART2_RTS/USART2_DE/UART4_RX/QUADSPI_BK1_IO3/SAI2_MCLK_B/ETH_MII_RX_CLK/ETH_RMII_REF_CLK/LCD_R2/EVENTOUT_N4") (pintype "bidirectional"))
    )
    (net (code "54") (name "MT6") (class "Default")
      (node (ref "CN2") (pin "2") (pinfunction "2_2") (pintype "bidirectional"))
      (node (ref "U1") (pin "N3") (pinfunction "PA2/TIM2_CH3/TIM5_CH3/LPTIM4_OUT/TIM15_CH1/USART2_TX/SAI2_SCK_B/ETH_MDIO/MDIOS_MDIO/LCD_R1/EVENTOUT_N3") (pintype "bidirectional"))
    )
    (net (code "55") (name "MT7") (class "Default")
      (node (ref "CN2") (pin "3") (pinfunction "3_3") (pintype "bidirectional"))
      (node (ref "U1") (pin "T3") (pinfunction "PA5/D2PWREN/TIM2_CH1/TIM2_ETR/TIM8_CH1N/SPI1_SCK/I2S1_CK/SPI6_SCK/OTG_HS_ULPI_CK/LCD_R4/EVENTOUT_T3") (pintype "bidirectional"))
    )
    (net (code "56") (name "MT8") (class "Default")
      (node (ref "CN2") (pin "4") (pinfunction "4_4") (pintype "bidirectional"))
      (node (ref "U1") (pin "P12") (pinfunction "PB11/TIM2_CH4/HRTIM_SCIN/LPTIM2_ETR/I2C2_SDA/DFSDM1_CKIN7/USART3_RX/OTG_HS_ULPI_D4/ETH_MII_TX_EN/ETH_RMII_TX_EN/LCD_G5/EVENTOUT_P12") (pintype "bidirectional"))
    )
    (net (code "57") (name "Net-(A1-SIGNAL)") (class "Default")
      (node (ref "A1") (pin "FEED") (pinfunction "SIGNAL_FEED") (pintype "bidirectional"))
      (node (ref "C8") (pin "1") (pinfunction "1_1") (pintype "passive"))
      (node (ref "L1") (pin "1") (pinfunction "1_1") (pintype "passive"))
    )
    (net (code "58") (name "Net-(C6-Pad1)") (class "Default")
      (node (ref "C6") (pin "1") (pinfunction "1_1") (pintype "passive"))
      (node (ref "U1") (pin "A7") (pinfunction "VCAP_A7") (pintype "power_in"))
      (node (ref "U1") (pin "D17") (pinfunction "VCAP_D17") (pintype "power_in"))
      (node (ref "U1") (pin "U11") (pinfunction "VCAP_U11") (pintype "power_in"))
    )
    (net (code "59") (name "Net-(C36-Pad1)") (class "Default")
      (node (ref "C36") (pin "1") (pinfunction "1_1") (pintype "passive"))
      (node (ref "R6") (pin "2") (pinfunction "2_2") (pintype "passive"))
    )
    (net (code "60") (name "Net-(C61-Pad1)") (class "Default")
      (node (ref "C61") (pin "1") (pinfunction "1_1") (pintype "passive"))
      (node (ref "R38") (pin "2") (pinfunction "2_2") (pintype "passive"))
    )
    (net (code "61") (name "Net-(C62-Pad-)") (class "Default")
      (node (ref "C62") (pin "-") (pinfunction "-_-") (pintype "passive"))
      (node (ref "C63") (pin "-") (pinfunction "-_-") (pintype "passive"))
      (node (ref "R36") (pin "1") (pinfunction "1_1") (pintype "passive"))
    )
    (net (code "62") (name "Net-(IC1-CLKIN)") (class "Default")
      (node (ref "IC1") (pin "5") (pinfunction "CLKIN_5") (pintype "bidirectional"))
      (node (ref "Y4") (pin "3") (pinfunction "OUT/IN_3") (pintype "bidirectional"))
    )
    (net (code "63") (name "Net-(IC1-SAG)") (class "Default")
      (node (ref "C63") (pin "+") (pinfunction "+_+") (pintype "passive"))
      (node (ref "IC1") (pin "25") (pinfunction "SAG_25") (pintype "bidirectional"))
    )
    (net (code "64") (name "Net-(IC1-VIN)") (class "Default")
      (node (ref "C64") (pin "1") (pinfunction "1_1") (pintype "passive"))
      (node (ref "IC1") (pin "22") (pinfunction "VIN_22") (pintype "bidirectional"))
    )
    (net (code "65") (name "Net-(IC1-VOUT)") (class "Default")
      (node (ref "C62") (pin "+") (pinfunction "+_+") (pintype "passive"))
      (node (ref "IC1") (pin "26") (pinfunction "VOUT_26") (pintype "bidirectional"))
    )
    (net (code "66") (name "Net-(IC1-XFB)") (class "Default")
      (node (ref "IC1") (pin "6") (pinfunction "XFB_6") (pintype "bidirectional"))
      (node (ref "Y4") (pin "1") (pinfunction "IN/OUT_1") (pintype "bidirectional"))
    )
    (net (code "67") (name "Net-(IC1-~{RESET})") (class "Default")
      (node (ref "IC1") (pin "19") (pinfunction "~{RESET}_19") (pintype "bidirectional"))
      (node (ref "R32") (pin "1") (pinfunction "1_1") (pintype "passive"))
    )
    (net (code "68") (name "Net-(IC2-CSB)") (class "Default")
      (node (ref "IC2") (pin "2") (pinfunction "CSB_2") (pintype "input"))
      (node (ref "R28") (pin "2") (pinfunction "2_2") (pintype "passive"))
    )
    (net (code "69") (name "Net-(IC2-SDO)") (class "Default")
      (node (ref "IC2") (pin "5") (pinfunction "SDO_5") (pintype "bidirectional"))
      (node (ref "R31") (pin "2") (pinfunction "2_2") (pintype "passive"))
    )
    (net (code "70") (name "Net-(IC3-VIN+)") (class "Default")
      (node (ref "IC3") (pin "3") (pinfunction "VIN+_3") (pintype "input"))
      (node (ref "R12") (pin "2") (pinfunction "2_2") (pintype "passive"))
      (node (ref "R3") (pin "1") (pinfunction "1_1") (pintype "passive"))
    )
    (net (code "71") (name "Net-(IC3-VIN-)") (class "Default")
      (node (ref "IC3") (pin "4") (pinfunction "VIN-_4") (pintype "input"))
      (node (ref "R13") (pin "2") (pinfunction "2_2") (pintype "passive"))
      (node (ref "R14") (pin "1") (pinfunction "1_1") (pintype "passive"))
    )
    (net (code "72") (name "Net-(IC4-BYPASS)") (class "Default")
      (node (ref "C38") (pin "1") (pinfunction "1_1") (pintype "passive"))
      (node (ref "IC4") (pin "4") (pinfunction "BYPASS_4") (pintype "passive"))
    )
    (net (code "73") (name "Net-(IC4-VIN)") (class "Default")
      (node (ref "FB1") (pin "2") (pinfunction "2_2") (pintype "passive"))
      (node (ref "IC4") (pin "1") (pinfunction "VIN_1") (pintype "input"))
      (node (ref "IC4") (pin "3") (pinfunction "VINH_3") (pintype "input"))
    )
    (net (code "74") (name "Net-(LED1-PadA)") (class "Default")
      (node (ref "LED1") (pin "A") (pinfunction "A_A") (pintype "passive"))
      (node (ref "R53") (pin "1") (pinfunction "1_1") (pintype "passive"))
    )
    (net (code "75") (name "Net-(LED2-PadA)") (class "Default")
      (node (ref "LED2") (pin "A") (pinfunction "A_A") (pintype "passive"))
      (node (ref "R54") (pin "1") (pinfunction "1_1") (pintype "passive"))
    )
    (net (code "76") (name "Net-(LED3-PadC)") (class "Default")
      (node (ref "LED3") (pin "C") (pinfunction "C_C") (pintype "passive"))
      (node (ref "R8") (pin "2") (pinfunction "2_2") (pintype "passive"))
    )
    (net (code "77") (name "Net-(Q2A-B)") (class "Default")
      (node (ref "Q2") (pin "5") (pinfunction "B_5") (pintype "passive"))
      (node (ref "R17") (pin "2") (pinfunction "2_2") (pintype "passive"))
    )
    (net (code "78") (name "Net-(Q2B-B)") (class "Default")
      (node (ref "Q2") (pin "2") (pinfunction "B_2") (pintype "passive"))
      (node (ref "R18") (pin "2") (pinfunction "2_2") (pintype "passive"))
    )
    (net (code "79") (name "Net-(R21-Pad1)") (class "Default")
      (node (ref "R21") (pin "1") (pinfunction "1_1") (pintype "passive"))
      (node (ref "T1") (pin "B") (pinfunction "B_B") (pintype "passive"))
    )
    (net (code "80") (name "Net-(R40-Pad1)") (class "Default")
      (node (ref "R40") (pin "1") (pinfunction "1_1") (pintype "passive"))
      (node (ref "R44") (pin "1") (pinfunction "1_1") (pintype "passive"))
      (node (ref "U$9") (pin "P$1") (pinfunction "P$1_P$1") (pintype "bidirectional"))
    )
    (net (code "81") (name "Net-(R52-Pad1)") (class "Default")
      (node (ref "R52") (pin "1") (pinfunction "1_1") (pintype "passive"))
      (node (ref "T2") (pin "B") (pinfunction "B_B") (pintype "passive"))
    )
    (net (code "82") (name "Net-(U1A-NRST)") (class "Default")
      (node (ref "C42") (pin "2") (pinfunction "2_2") (pintype "passive"))
      (node (ref "R22") (pin "2") (pinfunction "2_2") (pintype "passive"))
      (node (ref "SRST") (pin "TP") (pinfunction "TP_TP") (pintype "input"))
      (node (ref "U1") (pin "K1") (pinfunction "NRST_K1") (pintype "bidirectional"))
    )
    (net (code "83") (name "Net-(U1D-PH0-OSC_IN(PH0){slash}EVENTOUT)") (class "Default")
      (node (ref "C44") (pin "2") (pinfunction "2_2") (pintype "passive"))
      (node (ref "U1") (pin "J2") (pinfunction "PH0-OSC_IN(PH0)/EVENTOUT_J2") (pintype "bidirectional"))
      (node (ref "Y3") (pin "3") (pinfunction "OUT/IN_3") (pintype "bidirectional"))
    )
    (net (code "84") (name "Net-(U1D-PH1-OSC_OUT(PH1){slash}EVENTOUT)") (class "Default")
      (node (ref "C56") (pin "2") (pinfunction "2_2") (pintype "passive"))
      (node (ref "U1") (pin "J1") (pinfunction "PH1-OSC_OUT(PH1)/EVENTOUT_J1") (pintype "bidirectional"))
      (node (ref "Y3") (pin "1") (pinfunction "IN/OUT_1") (pintype "bidirectional"))
    )
    (net (code "85") (name "Net-(U1F-VBAT)") (class "Default")
      (node (ref "D1") (pin "C") (pinfunction "C_C") (pintype "passive"))
      (node (ref "U1") (pin "B1") (pinfunction "VBAT_B1") (pintype "power_in"))
    )
    (net (code "86") (name "Net-(U2-CPOUT)") (class "Default")
      (node (ref "C57") (pin "2") (pinfunction "2_2") (pintype "passive"))
      (node (ref "U2") (pin "20") (pinfunction "CPOUT_20") (pintype "output"))
    )
    (net (code "87") (name "Net-(U2-REGOUT)") (class "Default")
      (node (ref "C58") (pin "1") (pinfunction "1_1") (pintype "passive"))
      (node (ref "U2") (pin "10") (pinfunction "REGOUT_10") (pintype "passive"))
    )
    (net (code "88") (name "Net-(U3-CAP1)") (class "Default")
      (node (ref "C27") (pin "1") (pinfunction "1_1") (pintype "passive"))
      (node (ref "C5") (pin "2") (pinfunction "2_2") (pintype "passive"))
      (node (ref "R2") (pin "2") (pinfunction "2_2") (pintype "passive"))
      (node (ref "U3") (pin "48") (pinfunction "CAP1_48") (pintype "bidirectional"))
    )
    (net (code "89") (name "Net-(U3-CAP2)") (class "Default")
      (node (ref "C27") (pin "2") (pinfunction "2_2") (pintype "passive"))
      (node (ref "R2") (pin "1") (pinfunction "1_1") (pintype "passive"))
      (node (ref "U3") (pin "47") (pinfunction "CAP2_47") (pintype "bidirectional"))
    )
    (net (code "90") (name "Net-(U3-LNA_IN)") (class "Default")
      (node (ref "C10") (pin "1") (pinfunction "1_1") (pintype "passive"))
      (node (ref "L1") (pin "2") (pinfunction "2_2") (pintype "passive"))
      (node (ref "U3") (pin "2") (pinfunction "LNA_IN_2") (pintype "bidirectional"))
    )
    (net (code "91") (name "Net-(U3-SENSOR_CAPN(GPI38{slash}ADC1:2{slash}RTC2))") (class "Default")
      (node (ref "C2") (pin "1") (pinfunction "1_1") (pintype "passive"))
      (node (ref "U3") (pin "7") (pinfunction "SENSOR_CAPN(GPI38/ADC1:2/RTC2)_7") (pintype "bidirectional"))
    )
    (net (code "92") (name "Net-(U3-SENSOR_CAPP(GPI37{slash}ADC1:1{slash}RTC1))") (class "Default")
      (node (ref "C1") (pin "1") (pinfunction "1_1") (pintype "passive"))
      (node (ref "U3") (pin "6") (pinfunction "SENSOR_CAPP(GPI37/ADC1:1/RTC1)_6") (pintype "bidirectional"))
    )
    (net (code "93") (name "Net-(U3-SENSOR_VP(GPI36{slash}ADC1:0{slash}RTC0))") (class "Default")
      (node (ref "C1") (pin "2") (pinfunction "2_2") (pintype "passive"))
      (node (ref "U3") (pin "5") (pinfunction "SENSOR_VP(GPI36/ADC1:0/RTC0)_5") (pintype "bidirectional"))
    )
    (net (code "94") (name "Net-(U3-XTAL_N)") (class "Default")
      (node (ref "C4") (pin "2") (pinfunction "2_2") (pintype "passive"))
      (node (ref "U3") (pin "44") (pinfunction "XTAL_N_44") (pintype "bidirectional"))
      (node (ref "Y1") (pin "P3") (pinfunction "2_P3") (pintype "passive"))
    )
    (net (code "95") (name "Net-(U3-XTAL_P)") (class "Default")
      (node (ref "C3") (pin "2") (pinfunction "2_2") (pintype "passive"))
      (node (ref "U3") (pin "45") (pinfunction "XTAL_P_45") (pintype "bidirectional"))
      (node (ref "Y1") (pin "P1") (pinfunction "1_P1") (pintype "passive"))
    )
    (net (code "96") (name "Net-(U4-BST)") (class "Default")
      (node (ref "R38") (pin "1") (pinfunction "1_1") (pintype "passive"))
      (node (ref "U4") (pin "6") (pinfunction "BST_6") (pintype "power_in"))
    )
    (net (code "97") (name "Net-(U4-EN)") (class "Default")
      (node (ref "R42") (pin "1") (pinfunction "1_1") (pintype "passive"))
      (node (ref "R43") (pin "2") (pinfunction "2_2") (pintype "passive"))
      (node (ref "U4") (pin "2") (pinfunction "EN_2") (pintype "input"))
    )
    (net (code "98") (name "Net-(U4-FB)") (class "Default")
      (node (ref "R39") (pin "2") (pinfunction "2_2") (pintype "passive"))
      (node (ref "R40") (pin "2") (pinfunction "2_2") (pintype "passive"))
      (node (ref "U4") (pin "8") (pinfunction "FB_8") (pintype "input"))
    )
    (net (code "99") (name "Net-(U4-PG)") (class "Default")
      (node (ref "C65") (pin "1") (pinfunction "1_1") (pintype "passive"))
      (node (ref "U4") (pin "7") (pinfunction "PG_7") (pintype "output"))
    )
    (net (code "100") (name "Net-(U4-RT)") (class "Default")
      (node (ref "R41") (pin "2") (pinfunction "2_2") (pintype "passive"))
      (node (ref "U4") (pin "1") (pinfunction "RT_1") (pintype "input"))
    )
    (net (code "101") (name "Net-(U4-SW)") (class "Default")
      (node (ref "C61") (pin "2") (pinfunction "2_2") (pintype "passive"))
      (node (ref "U$9") (pin "P$2") (pinfunction "P$2_P$2") (pintype "bidirectional"))
      (node (ref "U4") (pin "5") (pinfunction "SW_5") (pintype "output"))
    )
    (net (code "102") (name "Net-(U6-BST)") (class "Default")
      (node (ref "R6") (pin "1") (pinfunction "1_1") (pintype "passive"))
      (node (ref "U6") (pin "6") (pinfunction "BST_6") (pintype "power_in"))
    )
    (net (code "103") (name "Net-(U6-EN)") (class "Default")
      (node (ref "R16") (pin "1") (pinfunction "1_1") (pintype "passive"))
      (node (ref "R19") (pin "2") (pinfunction "2_2") (pintype "passive"))
      (node (ref "U6") (pin "2") (pinfunction "EN_2") (pintype "input"))
    )
    (net (code "104") (name "Net-(U6-FB)") (class "Default")
      (node (ref "R10") (pin "2") (pinfunction "2_2") (pintype "passive"))
      (node (ref "R7") (pin "2") (pinfunction "2_2") (pintype "passive"))
      (node (ref "U6") (pin "8") (pinfunction "FB_8") (pintype "input"))
    )
    (net (code "105") (name "Net-(U6-PG)") (class "Default")
      (node (ref "C37") (pin "1") (pinfunction "1_1") (pintype "passive"))
      (node (ref "U6") (pin "7") (pinfunction "PG_7") (pintype "output"))
    )
    (net (code "106") (name "Net-(U6-RT)") (class "Default")
      (node (ref "R11") (pin "2") (pinfunction "2_2") (pintype "passive"))
      (node (ref "U6") (pin "1") (pinfunction "RT_1") (pintype "input"))
    )
    (net (code "107") (name "Net-(U6-SW)") (class "Default")
      (node (ref "C36") (pin "2") (pinfunction "2_2") (pintype "passive"))
      (node (ref "U$5") (pin "P$2") (pinfunction "P$2_P$2") (pintype "bidirectional"))
      (node (ref "U6") (pin "5") (pinfunction "SW_5") (pintype "output"))
    )
    (net (code "108") (name "Net-(U7-EN)") (class "Default")
      (node (ref "FB3") (pin "2") (pinfunction "2_2") (pintype "passive"))
      (node (ref "U7") (pin "1") (pinfunction "IN_1") (pintype "input"))
      (node (ref "U7") (pin "3") (pinfunction "EN_3") (pintype "input"))
    )
    (net (code "109") (name "Net-(USB1-ID)") (class "Default")
      (node (ref "R57") (pin "1") (pinfunction "1_1") (pintype "passive"))
      (node (ref "USB1") (pin "4") (pinfunction "ID_4") (pintype "bidirectional"))
    )
    (net (code "110") (name "PWM1") (class "Default")
      (node (ref "CN3") (pin "1") (pinfunction "1_1") (pintype "bidirectional"))
      (node (ref "U1") (pin "D15") (pinfunction "PA9/TIM1_CH2/HRTIM_CHC1/LPUART1_TX/I2C3_SMBA/SPI2_SCK/I2S2_CK/USART1_TX/FDCAN1_RXFD_MODE/DCMI_D0/LCD_R5/EVENTOUT_D15") (pintype "bidirectional"))
    )
    (net (code "111") (name "PWM2") (class "Default")
      (node (ref "CN3") (pin "2") (pinfunction "2_2") (pintype "bidirectional"))
      (node (ref "U1") (pin "D14") (pinfunction "PA10/TIM1_CH3/HRTIM_CHC2/LPUART1_RX/USART1_RX/FDCAN1_TXFD_MODE/OTG_FS_ID/MDIOS_MDIO/LCD_B4/DCMI_D1/LCD_B1/EVENTOUT_D14") (pintype "bidirectional"))
    )
    (net (code "112") (name "PWM3") (class "Default")
      (node (ref "CN3") (pin "3") (pinfunction "3_3") (pintype "bidirectional"))
      (node (ref "U1") (pin "U10") (pinfunction "PE14/TIM1_CH4/SPI4_MOSI/SAI2_MCLK_B/FMC_D11/FMC_DA11/LCD_CLK/EVENTOUT_U10") (pintype "bidirectional"))
    )
    (net (code "113") (name "PWM4") (class "Default")
      (node (ref "CN3") (pin "4") (pinfunction "4_4") (pintype "bidirectional"))
      (node (ref "U1") (pin "J15") (pinfunction "PK1/TIM1_CH1/TIM8_CH3N/SPI5_NSS/LCD_G6/EVENTOUT_J15") (pintype "bidirectional"))
    )
    (net (code "114") (name "PWM5") (class "Default")
      (node (ref "CN4") (pin "1") (pinfunction "1_1") (pintype "bidirectional"))
      (node (ref "U1") (pin "B15") (pinfunction "PI2/TIM8_CH4/SPI2_MISO/I2S2_SDI/FMC_D26/DCMI_D9/LCD_G7/EVENTOUT_B15") (pintype "bidirectional"))
    )
    (net (code "115") (name "PWM6") (class "Default")
      (node (ref "CN4") (pin "2") (pinfunction "2_2") (pintype "bidirectional"))
      (node (ref "U1") (pin "N13") (pinfunction "PJ8/TIM1_CH3N/TIM8_CH1/UART8_TX/LCD_G1/EVENTOUT_N13") (pintype "bidirectional"))
    )
    (net (code "116") (name "PWM7") (class "Default")
      (node (ref "CN4") (pin "3") (pinfunction "3_3") (pintype "bidirectional"))
      (node (ref "U1") (pin "A2") (pinfunction "PI6/TIM8_CH2/SAI2_SD_A/FMC_D28/DCMI_D6/LCD_B6/EVENTOUT_A2") (pintype "bidirectional"))
    )
    (net (code "117") (name "PWM8") (class "Default")
      (node (ref "CN4") (pin "4") (pinfunction "4_4") (pintype "bidirectional"))
      (node (ref "U1") (pin "B3") (pinfunction "PI7/TIM8_CH3/SAI2_FS_A/FMC_D29/DCMI_D7/LCD_B7/EVENTOUT_B3") (pintype "bidirectional"))
    )
    (net (code "118") (name "QSPI-CLK") (class "Default")
      (node (ref "U1") (pin "R6") (pinfunction "PB2/RTC_OUT/SAI1_D1/DFSDM1_CKIN1/SAI1_SD_A/SPI3_MOSI/I2S3_SDO/SAI4_SD_A/QUADSPI_CLK/SAI4_D1/EVENTOUT_R6") (pintype "bidirectional"))
      (node (ref "U10") (pin "6") (pinfunction "CLK_6") (pintype "bidirectional"))
    )
    (net (code "119") (name "QSPI-MISO") (class "Default")
      (node (ref "U1") (pin "K4") (pinfunction "PF8/TIM16_CH1N/SPI5_MISO/SAI1_SCK_B/UART7_RTS/UART7_DE/SAI4_SCK_B/TIM13_CH1/QUADSPI_BK1_IO0/EVENTOUT_K4") (pintype "bidirectional"))
      (node (ref "U10") (pin "2") (pinfunction "D1/DO_2") (pintype "bidirectional"))
    )
    (net (code "120") (name "QSPI-MOSI") (class "Default")
      (node (ref "U1") (pin "L4") (pinfunction "PF9/TIM17_CH1N/SPI5_MOSI/SAI1_FS_B/UART7_CTS/SAI4_FS_B/TIM14_CH1/QUADSPI_BK1_IO1/EVENTOUT_L4") (pintype "bidirectional"))
      (node (ref "U10") (pin "5") (pinfunction "D0/DI_5") (pintype "bidirectional"))
    )
    (net (code "121") (name "QSPI-NCS") (class "Default")
      (node (ref "U1") (pin "G15") (pinfunction "PG6/TIM17_BKIN/HRTIM_CHE1/QUADSPI_BK1_NCS/FMC_NE3/DCMI_D12/LCD_R7/EVENTOUT_G15") (pintype "bidirectional"))
      (node (ref "U10") (pin "1") (pinfunction "~{CS}_1") (pintype "bidirectional"))
    )
    (net (code "122") (name "QSPI-~{HOLD}") (class "Default")
      (node (ref "U1") (pin "K2") (pinfunction "PF6/TIM16_CH1/SPI5_NSS/SAI1_SD_B/UART7_RX/SAI4_SD_B/QUADSPI_BK1_IO3/EVENTOUT_K2") (pintype "bidirectional"))
      (node (ref "U10") (pin "7") (pinfunction "D3/~{HOLD}_7") (pintype "bidirectional"))
    )
    (net (code "123") (name "QSPI-~{WP}") (class "Default")
      (node (ref "U1") (pin "C3") (pinfunction "PE2/TRACECLK/SAI1_CK1/SPI4_SCK/SAI1_MCLK_A/SAI4_MCLK_A/QUADSPI_BK1_IO2/SAI4_CK1/ETH_MII_TXD3/FMC_A23/EVENTOUT_C3") (pintype "bidirectional"))
      (node (ref "U10") (pin "3") (pinfunction "D2/~{WP}_3") (pintype "bidirectional"))
    )
    (net (code "124") (name "RTS") (class "Default")
      (node (ref "Q2") (pin "4") (pinfunction "E_4") (pintype "passive"))
      (node (ref "R18") (pin "1") (pinfunction "1_1") (pintype "passive"))
      (node (ref "RTS") (pin "TP") (pinfunction "TP_TP") (pintype "input"))
    )
    (net (code "125") (name "SBUS_RC") (class "Default")
      (node (ref "CN9") (pin "3") (pinfunction "3_3") (pintype "bidirectional"))
      (node (ref "R21") (pin "2") (pinfunction "2_2") (pintype "passive"))
    )
    (net (code "126") (name "SBUS_RX") (class "Default")
      (node (ref "R45") (pin "2") (pinfunction "2_2") (pintype "passive"))
      (node (ref "T1") (pin "C") (pinfunction "C_C") (pintype "passive"))
      (node (ref "U1") (pin "R16") (pinfunction "PD12/LPTIM1_IN1/TIM4_CH1/LPTIM2_IN1/I2C4_SCL/USART3_RTS/USART3_DE/QUADSPI_BK1_IO1/SAI2_FS_A/FMC_A17/EVENTOUT_R16") (pintype "bidirectional"))
      (node (ref "U1") (pin "T14") (pinfunction "PB12/TIM1_BKIN/I2C2_SMBA/SPI2_NSS/I2S2_WS/DFSDM1_DATIN1/USART3_CK/FDCAN2_RX/OTG_HS_ULPI_D5/ETH_MII_TXD0/ETH_RMII_TXD0/OTG_HS_ID/TIM1_BKIN_COMP12/UART5_RX/EVENTOUT_T14") (pintype "bidirectional"))
    )
    (net (code "127") (name "SPI1_CLK") (class "Default")
      (node (ref "U1") (pin "B9") (pinfunction "PG11/LPTIM1_IN2/HRTIM_EEV4/SPI1_SCK/I2S1_CK/SPDIFRX1_IN1/SDMMC2_D2/ETH_MII_TX_EN/ETH_RMII_TX_EN/DCMI_D3/LCD_B3/EVENTOUT_B9") (pintype "bidirectional"))
    )
    (net (code "128") (name "SPI1_MISO") (class "Default")
      (node (ref "U1") (pin "A10") (pinfunction "PG9/SPI1_MISO/I2S1_SDI/USART6_RX/SPDIFRX1_IN4/QUADSPI_BK2_IO2/SAI2_FS_B/FMC_NE2/FMC_NCE/DCMI_VSYNC/EVENTOUT_A10") (pintype "bidirectional"))
    )
    (net (code "129") (name "SPI1_MOSI") (class "Default")
      (node (ref "U1") (pin "C11") (pinfunction "PD7/DFSDM1_DATIN4/SPI1_MOSI/I2S1_SDO/DFSDM1_CKIN1/USART2_CK/SPDIFRX1_IN1/SDMMC2_CMD/FMC_NE1/EVENTOUT_C11") (pintype "bidirectional"))
    )
    (net (code "130") (name "U0RXD") (class "Default")
      (node (ref "R56") (pin "2") (pinfunction "2_2") (pintype "passive"))
      (node (ref "U3") (pin "40") (pinfunction "(GPIO3/CLK_OUT2/HS2_DATA0)U0RXD_40") (pintype "bidirectional"))
    )
    (net (code "131") (name "U0TXD") (class "Default")
      (node (ref "R55") (pin "2") (pinfunction "2_2") (pintype "passive"))
      (node (ref "U3") (pin "41") (pinfunction "(GPIO1/CLK_OUT3/HS2_DATA1)U0TXD_41") (pintype "bidirectional"))
    )
    (net (code "132") (name "U1_RX") (class "Default")
      (node (ref "CN5") (pin "3") (pinfunction "3_3") (pintype "bidirectional"))
      (node (ref "R55") (pin "1") (pinfunction "1_1") (pintype "passive"))
      (node (ref "U1") (pin "C5") (pinfunction "PB7/TIM17_CH1N/TIM4_CH2/HRTIM_EEV9/I2C1_SDA/I2C4_SDA/USART1_RX/LPUART1_RX/FDCAN2_TXFD_MODE/DFSDM1_CKIN5/FMC_NL/DCMI_VSYNC/EVENTOUT_C5") (pintype "bidirectional"))
    )
    (net (code "133") (name "U1_TX") (class "Default")
      (node (ref "CN5") (pin "2") (pinfunction "2_2") (pintype "bidirectional"))
      (node (ref "R56") (pin "1") (pinfunction "1_1") (pintype "passive"))
      (node (ref "U1") (pin "B5") (pinfunction "PB6/TIM16_CH1N/TIM4_CH1/HRTIM_EEV8/I2C1_SCL/CEC/I2C4_SCL/USART1_TX/LPUART1_TX/FDCAN2_TX/QUADSPI_BK1_NCS/DFSDM1_DATIN5/FMC_SDNE1/DCMI_D5/UART5_TX/EVENTOUT_B5") (pintype "bidirectional"))
    )
    (net (code "134") (name "U2_RX") (class "Default")
      (node (ref "U1") (pin "B11") (pinfunction "PD6/SAI1_D1/DFSDM1_CKIN4/DFSDM1_DATIN1/SPI3_MOSI/I2S3_SDO/SAI1_SD_A/USART2_RX/SAI4_SD_A/FDCAN2_RXFD_MODE/SAI4_D1/SDMMC2_CK/FMC_NWAIT/DCMI_D10/LCD_B2/EVENTOUT_B11") (pintype "bidirectional"))
    )
    (net (code "135") (name "U2_TX") (class "Default")
      (node (ref "U1") (pin "A11") (pinfunction "PD5/HRTIM_EEV3/USART2_TX/FDCAN1_TXFD_MODE/FMC_NWE/EVENTOUT_A11") (pintype "bidirectional"))
    )
    (net (code "136") (name "U3_RX") (class "Default")
      (node (ref "CN7") (pin "4") (pinfunction "4_4") (pintype "bidirectional"))
      (node (ref "U1") (pin "T17") (pinfunction "PD9/DFSDM1_DATIN3/SAI3_SD_B/USART3_RX/FDCAN2_RXFD_MODE/FMC_D14/FMC_DA14/EVENTOUT_T17") (pintype "bidirectional"))
    )
    (net (code "137") (name "U3_TX") (class "Default")
      (node (ref "CN7") (pin "3") (pinfunction "3_3") (pintype "bidirectional"))
      (node (ref "U1") (pin "P11") (pinfunction "PB10/TIM2_CH3/HRTIM_SCOUT/LPTIM2_IN1/I2C2_SCL/SPI2_SCK/I2S2_CK/DFSDM1_DATIN7/USART3_TX/QUADSPI_BK1_NCS/OTG_HS_ULPI_D3/ETH_MII_RX_ER/LCD_G4/EVENTOUT_P11") (pintype "bidirectional"))
    )
    (net (code "138") (name "U4_RX") (class "Default")
      (node (ref "CN8") (pin "2") (pinfunction "2_2") (pintype "bidirectional"))
      (node (ref "U1") (pin "B17") (pinfunction "PH14/TIM8_CH2N/UART4_RX/FDCAN1_RX/FMC_D22/DCMI_D4/LCD_G3/EVENTOUT_B17") (pintype "bidirectional"))
    )
    (net (code "139") (name "U4_TX") (class "Default")
      (node (ref "CN8") (pin "1") (pinfunction "1_1") (pintype "bidirectional"))
      (node (ref "U1") (pin "D16") (pinfunction "PH13/TIM8_CH1N/UART4_TX/FDCAN1_TX/FMC_D21/LCD_G2/EVENTOUT_D16") (pintype "bidirectional"))
    )
    (net (code "140") (name "U5_RX") (class "Default")
      (node (ref "CN8") (pin "4") (pinfunction "4_4") (pintype "bidirectional"))
      (node (ref "U1") (pin "D12") (pinfunction "PD2/TRACED2/TIM3_ETR/UART5_RX/SDMMC1_CMD/DCMI_D11/EVENTOUT_D12") (pintype "bidirectional"))
    )
    (net (code "141") (name "U5_TX") (class "Default")
      (node (ref "CN8") (pin "3") (pinfunction "3_3") (pintype "bidirectional"))
      (node (ref "U1") (pin "C12") (pinfunction "PC12/TRACED3/HRTIM_EEV2/SPI3_MOSI/I2S3_SDO/USART3_CK/UART5_TX/SDMMC1_CK/DCMI_D9/EVENTOUT_C12") (pintype "bidirectional"))
    )
    (net (code "142") (name "USB0_D_N") (class "Default")
      (node (ref "R27") (pin "1") (pinfunction "1_1") (pintype "passive"))
      (node (ref "USB1") (pin "2") (pinfunction "DM_2") (pintype "bidirectional"))
    )
    (net (code "143") (name "USB0_D_P") (class "Default")
      (node (ref "R26") (pin "1") (pinfunction "1_1") (pintype "passive"))
      (node (ref "USB1") (pin "3") (pinfunction "DP_3") (pintype "bidirectional"))
    )
    (net (code "144") (name "USB_D_N") (class "Default")
      (node (ref "R27") (pin "2") (pinfunction "2_2") (pintype "passive"))
      (node (ref "U1") (pin "E17") (pinfunction "PA11/TIM1_CH4/HRTIM_CHD1/LPUART1_CTS/SPI2_NSS/I2S2_WS/UART4_RX/USART1_CTS/USART1_NSS/FDCAN1_RX/OTG_FS_DM/LCD_R4/EVENTOUT_E17") (pintype "bidirectional"))
    )
    (net (code "145") (name "USB_D_P") (class "Default")
      (node (ref "R15") (pin "2") (pinfunction "2_2") (pintype "passive"))
      (node (ref "R26") (pin "2") (pinfunction "2_2") (pintype "passive"))
      (node (ref "U1") (pin "E16") (pinfunction "PA12/TIM1_ETR/HRTIM_CHD2/LPUART1_RTS/LPUART1_DE/SPI2_SCK/I2S2_CK/UART4_TX/USART1_RTS/USART1_DE/SAI2_FS_B/FDCAN1_TX/OTG_FS_DP/LCD_R5/EVENTOUT_E16") (pintype "bidirectional"))
    )
    (net (code "146") (name "VBAT") (class "Default")
      (node (ref "BATT") (pin "1") (pinfunction "P_1") (pintype "passive"))
      (node (ref "D3") (pin "A") (pinfunction "A_A") (pintype "passive"))
      (node (ref "R3") (pin "2") (pinfunction "2_2") (pintype "passive"))
    )
    (net (code "147") (name "VBAT_BUFF") (class "Default")
      (node (ref "IC3") (pin "1") (pinfunction "VOUT_1") (pintype "output"))
      (node (ref "R14") (pin "2") (pinfunction "2_2") (pintype "passive"))
      (node (ref "U1") (pin "T7") (pinfunction "PF11/SPI5_MOSI/SAI2_SD_B/FMC_SDNRAS/DCMI_D12/EVENTOUT_T7") (pintype "bidirectional"))
    )
    (net (code "148") (name "VBUS") (class "Default")
      (node (ref "C11") (pin "1") (pinfunction "1_1") (pintype "passive"))
      (node (ref "C12") (pin "+") (pinfunction "+_+") (pintype "passive"))
      (node (ref "C13") (pin "+") (pinfunction "+_+") (pintype "passive"))
      (node (ref "C7") (pin "1") (pinfunction "1_1") (pintype "passive"))
      (node (ref "D5") (pin "A") (pinfunction "A_A") (pintype "passive"))
      (node (ref "R15") (pin "1") (pinfunction "1_1") (pintype "passive"))
      (node (ref "USB1") (pin "1") (pinfunction "VCC_1") (pintype "bidirectional"))
    )
    (net (code "149") (name "VIN") (class "Default")
      (node (ref "C28") (pin "1") (pinfunction "1_1") (pintype "passive"))
      (node (ref "C29") (pin "1") (pinfunction "1_1") (pintype "passive"))
      (node (ref "C31") (pin "+") (pinfunction "+_+") (pintype "passive"))
      (node (ref "C32") (pin "+") (pinfunction "+_+") (pintype "passive"))
      (node (ref "C33") (pin "1") (pinfunction "1_1") (pintype "passive"))
      (node (ref "C34") (pin "+") (pinfunction "+_+") (pintype "passive"))
      (node (ref "C35") (pin "1") (pinfunction "1_1") (pintype "passive"))
      (node (ref "D3") (pin "C") (pinfunction "C_C") (pintype "passive"))
      (node (ref "R16") (pin "2") (pinfunction "2_2") (pintype "passive"))
      (node (ref "R42") (pin "2") (pinfunction "2_2") (pintype "passive"))
      (node (ref "U4") (pin "3") (pinfunction "VIN_3") (pintype "input"))
      (node (ref "U6") (pin "3") (pinfunction "VIN_3") (pintype "input"))
    )
    (net (code "150") (name "unconnected-(C30-Pad1)") (class "Default")
      (node (ref "C30") (pin "1") (pinfunction "1_1") (pintype "passive"))
    )
    (net (code "151") (name "unconnected-(IC1-CLKOUT-Pad7)") (class "Default")
      (node (ref "IC1") (pin "7") (pinfunction "CLKOUT_7") (pintype "bidirectional"))
    )
    (net (code "152") (name "unconnected-(IC1-N.C._1-Pad1)") (class "Default")
      (node (ref "IC1") (pin "1") (pinfunction "N.C._1_1") (pintype "bidirectional"))
    )
    (net (code "153") (name "unconnected-(IC1-N.C._2-Pad2)") (class "Default")
      (node (ref "IC1") (pin "2") (pinfunction "N.C._2_2") (pintype "bidirectional"))
    )
    (net (code "154") (name "unconnected-(IC1-N.C._3-Pad14)") (class "Default")
      (node (ref "IC1") (pin "14") (pinfunction "N.C._3_14") (pintype "bidirectional"))
    )
    (net (code "155") (name "unconnected-(IC1-N.C._4-Pad15)") (class "Default")
      (node (ref "IC1") (pin "15") (pinfunction "N.C._4_15") (pintype "bidirectional"))
    )
    (net (code "156") (name "unconnected-(IC1-N.C._5-Pad16)") (class "Default")
      (node (ref "IC1") (pin "16") (pinfunction "N.C._5_16") (pintype "bidirectional"))
    )
    (net (code "157") (name "unconnected-(IC1-N.C._6-Pad27)") (class "Default")
      (node (ref "IC1") (pin "27") (pinfunction "N.C._6_27") (pintype "bidirectional"))
    )
    (net (code "158") (name "unconnected-(IC1-N.C._7-Pad28)") (class "Default")
      (node (ref "IC1") (pin "28") (pinfunction "N.C._7_28") (pintype "bidirectional"))
    )
    (net (code "159") (name "unconnected-(IC1-SYNC_IN-Pad13)") (class "Default")
      (node (ref "IC1") (pin "13") (pinfunction "SYNC_IN_13") (pintype "bidirectional"))
    )
    (net (code "160") (name "unconnected-(U1A-PA1_C{slash}TIM2_CH2{slash}TIM5_CH2{slash}LPTIM3_OUT{slash}TIM15_CH1N{slash}USART2_RTS{slash}USART2_DE{slash}UART4_RX{slash}QUADSPI_BK1_IO3{slash}SAI2_MCLK_B{slash}ETH_MII_RX_CLK{slash}ETH_RMII_REF_CLK{slash}LCD_R2{slash}EVENTOUT-PadT2)") (class "Default")
      (node (ref "U1") (pin "T2") (pinfunction "PA1_C/TIM2_CH2/TIM5_CH2/LPTIM3_OUT/TIM15_CH1N/USART2_RTS/USART2_DE/UART4_RX/QUADSPI_BK1_IO3/SAI2_MCLK_B/ETH_MII_RX_CLK/ETH_RMII_REF_CLK/LCD_R2/EVENTOUT_T2") (pintype "bidirectional"))
    )
    (net (code "161") (name "unconnected-(U1A-PA3{slash}TIM2_CH4{slash}TIM5_CH4{slash}LPTIM5_OUT{slash}TIM15_CH2{slash}USART2_RX{slash}LCD_B2{slash}OTG_HS_ULPI_D0{slash}ETH_MII_COL{slash}LCD_B5{slash}EVENTOUT-PadU2)") (class "Default")
      (node (ref "U1") (pin "U2") (pinfunction "PA3/TIM2_CH4/TIM5_CH4/LPTIM5_OUT/TIM15_CH2/USART2_RX/LCD_B2/OTG_HS_ULPI_D0/ETH_MII_COL/LCD_B5/EVENTOUT_U2") (pintype "bidirectional"))
    )
    (net (code "162") (name "unconnected-(U1A-PA6{slash}TIM1_BKIN{slash}TIM3_CH1{slash}TIM8_BKIN{slash}SPI1_MISO{slash}I2S1_SDI{slash}SPI6_MISO{slash}TIM13_CH1{slash}TIM8_BKIN_COMP12{slash}MDIOS_MDC{slash}TIM1_BKIN_COMP12{slash}DCMI_PIXCLK{slash}LCD_G2{slash}EVENTOUT-PadR3)") (class "Default")
      (node (ref "U1") (pin "R3") (pinfunction "PA6/TIM1_BKIN/TIM3_CH1/TIM8_BKIN/SPI1_MISO/I2S1_SDI/SPI6_MISO/TIM13_CH1/TIM8_BKIN_COMP12/MDIOS_MDC/TIM1_BKIN_COMP12/DCMI_PIXCLK/LCD_G2/EVENTOUT_R3") (pintype "bidirectional"))
    )
    (net (code "163") (name "unconnected-(U1A-PA7{slash}TIM1_CH1N{slash}TIM3_CH2{slash}TIM8_CH1N{slash}SPI1_MOSI{slash}I2S1_SDO{slash}SPI6_MOSI{slash}TIM14_CH1{slash}ETH_MII_RX_DV{slash}ETH_RMII_CRS_DV{slash}FMC_SDNWE{slash}EVENTOUT-PadR5)") (class "Default")
      (node (ref "U1") (pin "R5") (pinfunction "PA7/TIM1_CH1N/TIM3_CH2/TIM8_CH1N/SPI1_MOSI/I2S1_SDO/SPI6_MOSI/TIM14_CH1/ETH_MII_RX_DV/ETH_RMII_CRS_DV/FMC_SDNWE/EVENTOUT_R5") (pintype "bidirectional"))
    )
    (net (code "164") (name "unconnected-(U1A-PA15{slash}JTDI{slash}TIM2_CH1{slash}TIM2_ETR{slash}HRTIM_FLT1{slash}CEC{slash}SPI1_NSS{slash}I2S1_WS{slash}SPI3_NSS{slash}I2S3_WS{slash}SPI6_NSS{slash}UART4_RTS{slash}UART4_DE{slash}UART7_TX{slash}EVENTOUT-PadA14)") (class "Default")
      (node (ref "U1") (pin "A14") (pinfunction "PA15/JTDI/TIM2_CH1/TIM2_ETR/HRTIM_FLT1/CEC/SPI1_NSS/I2S1_WS/SPI3_NSS/I2S3_WS/SPI6_NSS/UART4_RTS/UART4_DE/UART7_TX/EVENTOUT_A14") (pintype "bidirectional"))
    )
    (net (code "165") (name "unconnected-(U1A-PB13{slash}TIM1_CH1N{slash}LPTIM2_OUT{slash}SPI2_SCK{slash}I2S2_CK{slash}DFSDM1_CKIN1{slash}USART3_CTS{slash}USART3_NSS{slash}FDCAN2_TX{slash}OTG_HS_ULPI_D6{slash}ETH_MII_TXD1{slash}ETH_RMII_TXD1{slash}UART5_TX{slash}EVENTOUT-PadU14)") (class "Default")
      (node (ref "U1") (pin "U14") (pinfunction "PB13/TIM1_CH1N/LPTIM2_OUT/SPI2_SCK/I2S2_CK/DFSDM1_CKIN1/USART3_CTS/USART3_NSS/FDCAN2_TX/OTG_HS_ULPI_D6/ETH_MII_TXD1/ETH_RMII_TXD1/UART5_TX/EVENTOUT_U14") (pintype "bidirectional"))
    )
    (net (code "166") (name "unconnected-(U1B-PC2_C{slash}CDSLEEP{slash}DFSDM1_CKIN1{slash}SPI2_MISO{slash}I2S2_SDI{slash}DFSDM1_CKOUT{slash}OTG_HS_ULPI_DIR{slash}ETH_MII_TXD2{slash}FMC_SDNE0{slash}EVENTOUT-PadR1)") (class "Default")
      (node (ref "U1") (pin "R1") (pinfunction "PC2_C/CDSLEEP/DFSDM1_CKIN1/SPI2_MISO/I2S2_SDI/DFSDM1_CKOUT/OTG_HS_ULPI_DIR/ETH_MII_TXD2/FMC_SDNE0/EVENTOUT_R1") (pintype "bidirectional"))
    )
    (net (code "167") (name "unconnected-(U1B-PC3_C{slash}CSLEEP{slash}DFSDM1_DATIN1{slash}SPI2_MOSI{slash}I2S2_SDO{slash}OTG_HS_ULPI_NXT{slash}ETH_MII_TX_CLK{slash}FMC_SDCKE0{slash}EVENTOUT-PadR2)") (class "Default")
      (node (ref "U1") (pin "R2") (pinfunction "PC3_C/CSLEEP/DFSDM1_DATIN1/SPI2_MOSI/I2S2_SDO/OTG_HS_ULPI_NXT/ETH_MII_TX_CLK/FMC_SDCKE0/EVENTOUT_R2") (pintype "bidirectional"))
    )
    (net (code "168") (name "unconnected-(U1B-PC3{slash}CSLEEP{slash}DFSDM1_DATIN1{slash}SPI2_MOSI{slash}I2S2_SDO{slash}OTG_HS_ULPI_NXT{slash}ETH_MII_TX_CLK{slash}FMC_SDCKE0{slash}EVENTOUT-PadM4)") (class "Default")
      (node (ref "U1") (pin "M4") (pinfunction "PC3/CSLEEP/DFSDM1_DATIN1/SPI2_MOSI/I2S2_SDO/OTG_HS_ULPI_NXT/ETH_MII_TX_CLK/FMC_SDCKE0/EVENTOUT_M4") (pintype "bidirectional"))
    )
    (net (code "169") (name "unconnected-(U1B-PC4{slash}DFSDM1_CKIN2{slash}I2S1_MCK{slash}SPDIFRX1_IN3{slash}ETH_MII_RXD0{slash}ETH_RMII_RXD0{slash}FMC_SDNE0{slash}EVENTOUT-PadT4)") (class "Default")
      (node (ref "U1") (pin "T4") (pinfunction "PC4/DFSDM1_CKIN2/I2S1_MCK/SPDIFRX1_IN3/ETH_MII_RXD0/ETH_RMII_RXD0/FMC_SDNE0/EVENTOUT_T4") (pintype "bidirectional"))
    )
    (net (code "170") (name "unconnected-(U1B-PC5{slash}SAI1_D3{slash}DFSDM1_DATIN2{slash}SPDIFRX1_IN4{slash}SAI4_D3{slash}ETH_MII_RXD1{slash}ETH_RMII_RXD1{slash}FMC_SDCKE0{slash}COMP1_OUT{slash}EVENTOUT-PadU4)") (class "Default")
      (node (ref "U1") (pin "U4") (pinfunction "PC5/SAI1_D3/DFSDM1_DATIN2/SPDIFRX1_IN4/SAI4_D3/ETH_MII_RXD1/ETH_RMII_RXD1/FMC_SDCKE0/COMP1_OUT/EVENTOUT_U4") (pintype "bidirectional"))
    )
    (net (code "171") (name "unconnected-(U1B-PC14-OSC32_IN{slash}EVENTOUT-PadC2)") (class "Default")
      (node (ref "U1") (pin "C2") (pinfunction "PC14-OSC32_IN/EVENTOUT_C2") (pintype "bidirectional"))
    )
    (net (code "172") (name "unconnected-(U1B-PC15-OSC32_OUT{slash}EVENTOUT-PadC1)") (class "Default")
      (node (ref "U1") (pin "C1") (pinfunction "PC15-OSC32_OUT/EVENTOUT_C1") (pintype "bidirectional"))
    )
    (net (code "173") (name "unconnected-(U1B-PD0{slash}DFSDM1_CKIN6{slash}SAI3_SCK_A{slash}UART4_RX{slash}FDCAN1_RX{slash}FMC_D2{slash}FMC_DA2{slash}EVENTOUT-PadD13)") (class "Default")
      (node (ref "U1") (pin "D13") (pinfunction "PD0/DFSDM1_CKIN6/SAI3_SCK_A/UART4_RX/FDCAN1_RX/FMC_D2/FMC_DA2/EVENTOUT_D13") (pintype "bidirectional"))
    )
    (net (code "174") (name "unconnected-(U1B-PD1{slash}DFSDM1_DATIN6{slash}SAI3_SD_A{slash}UART4_TX{slash}FDCAN1_TX{slash}FMC_D3{slash}FMC_DA3{slash}EVENTOUT-PadE12)") (class "Default")
      (node (ref "U1") (pin "E12") (pinfunction "PD1/DFSDM1_DATIN6/SAI3_SD_A/UART4_TX/FDCAN1_TX/FMC_D3/FMC_DA3/EVENTOUT_E12") (pintype "bidirectional"))
    )
    (net (code "175") (name "unconnected-(U1B-PD3{slash}DFSDM1_CKOUT{slash}SPI2_SCK{slash}I2S2_CK{slash}USART2_CTS{slash}USART2_NSS{slash}FMC_CLK{slash}DCMI_D5{slash}LCD_G7{slash}EVENTOUT-PadB12)") (class "Default")
      (node (ref "U1") (pin "B12") (pinfunction "PD3/DFSDM1_CKOUT/SPI2_SCK/I2S2_CK/USART2_CTS/USART2_NSS/FMC_CLK/DCMI_D5/LCD_G7/EVENTOUT_B12") (pintype "bidirectional"))
    )
    (net (code "176") (name "unconnected-(U1B-PD4{slash}HRTIM_FLT3{slash}SAI3_FS_A{slash}USART2_RTS{slash}USART2_DE{slash}FDCAN1_RXFD_MODE{slash}FMC_NOE{slash}EVENTOUT-PadA12)") (class "Default")
      (node (ref "U1") (pin "A12") (pinfunction "PD4/HRTIM_FLT3/SAI3_FS_A/USART2_RTS/USART2_DE/FDCAN1_RXFD_MODE/FMC_NOE/EVENTOUT_A12") (pintype "bidirectional"))
    )
    (net (code "177") (name "unconnected-(U1B-PD8{slash}DFSDM1_CKIN3{slash}SAI3_SCK_B{slash}USART3_TX{slash}SPDIFRX1_IN2{slash}FMC_D13{slash}FMC_DA13{slash}EVENTOUT-PadU16)") (class "Default")
      (node (ref "U1") (pin "U16") (pinfunction "PD8/DFSDM1_CKIN3/SAI3_SCK_B/USART3_TX/SPDIFRX1_IN2/FMC_D13/FMC_DA13/EVENTOUT_U16") (pintype "bidirectional"))
    )
    (net (code "178") (name "unconnected-(U1B-PD10{slash}DFSDM1_CKOUT{slash}SAI3_FS_B{slash}USART3_CK{slash}FDCAN2_TXFD_MODE{slash}FMC_D15{slash}FMC_DA15{slash}LCD_B3{slash}EVENTOUT-PadT16)") (class "Default")
      (node (ref "U1") (pin "T16") (pinfunction "PD10/DFSDM1_CKOUT/SAI3_FS_B/USART3_CK/FDCAN2_TXFD_MODE/FMC_D15/FMC_DA15/LCD_B3/EVENTOUT_T16") (pintype "bidirectional"))
    )
    (net (code "179") (name "unconnected-(U1B-PD11{slash}LPTIM2_IN2{slash}I2C4_SMBA{slash}USART3_CTS{slash}USART3_NSS{slash}QUADSPI_BK1_IO0{slash}SAI2_SD_A{slash}FMC_A16{slash}EVENTOUT-PadR15)") (class "Default")
      (node (ref "U1") (pin "R15") (pinfunction "PD11/LPTIM2_IN2/I2C4_SMBA/USART3_CTS/USART3_NSS/QUADSPI_BK1_IO0/SAI2_SD_A/FMC_A16/EVENTOUT_R15") (pintype "bidirectional"))
    )
    (net (code "180") (name "unconnected-(U1B-PD13{slash}LPTIM1_OUT{slash}TIM4_CH2{slash}I2C4_SDA{slash}QUADSPI_BK1_IO3{slash}SAI2_SCK_A{slash}FMC_A18{slash}EVENTOUT-PadR17)") (class "Default")
      (node (ref "U1") (pin "R17") (pinfunction "PD13/LPTIM1_OUT/TIM4_CH2/I2C4_SDA/QUADSPI_BK1_IO3/SAI2_SCK_A/FMC_A18/EVENTOUT_R17") (pintype "bidirectional"))
    )
    (net (code "181") (name "unconnected-(U1B-PD14{slash}TIM4_CH3{slash}SAI3_MCLK_B{slash}UART8_CTS{slash}FMC_D0{slash}FMC_DA0{slash}EVENTOUT-PadP16)") (class "Default")
      (node (ref "U1") (pin "P16") (pinfunction "PD14/TIM4_CH3/SAI3_MCLK_B/UART8_CTS/FMC_D0/FMC_DA0/EVENTOUT_P16") (pintype "bidirectional"))
    )
    (net (code "182") (name "unconnected-(U1B-PD15{slash}TIM4_CH4{slash}SAI3_MCLK_A{slash}UART8_RTS{slash}UART8_DE{slash}FMC_D1{slash}FMC_DA1{slash}EVENTOUT-PadP15)") (class "Default")
      (node (ref "U1") (pin "P15") (pinfunction "PD15/TIM4_CH4/SAI3_MCLK_A/UART8_RTS/UART8_DE/FMC_D1/FMC_DA1/EVENTOUT_P15") (pintype "bidirectional"))
    )
    (net (code "183") (name "unconnected-(U1C-PE0{slash}LPTIM1_ETR{slash}TIM4_ETR{slash}HRTIM_SCIN{slash}LPTIM2_ETR{slash}UART8_RX{slash}FDCAN1_RXFD_MODE{slash}SAI2_MCLK_A{slash}FMC_NBL0{slash}DCMI_D2{slash}EVENTOUT-PadC4)") (class "Default")
      (node (ref "U1") (pin "C4") (pinfunction "PE0/LPTIM1_ETR/TIM4_ETR/HRTIM_SCIN/LPTIM2_ETR/UART8_RX/FDCAN1_RXFD_MODE/SAI2_MCLK_A/FMC_NBL0/DCMI_D2/EVENTOUT_C4") (pintype "bidirectional"))
    )
    (net (code "184") (name "unconnected-(U1C-PE1{slash}LPTIM1_IN2{slash}HRTIM_SCOUT{slash}UART8_TX{slash}FDCAN1_TXFD_MODE{slash}FMC_NBL1{slash}DCMI_D3{slash}EVENTOUT-PadB4)") (class "Default")
      (node (ref "U1") (pin "B4") (pinfunction "PE1/LPTIM1_IN2/HRTIM_SCOUT/UART8_TX/FDCAN1_TXFD_MODE/FMC_NBL1/DCMI_D3/EVENTOUT_B4") (pintype "bidirectional"))
    )
    (net (code "185") (name "unconnected-(U1C-PE3{slash}TRACED0{slash}TIM15_BKIN{slash}SAI1_SD_B{slash}SAI4_SD_B{slash}FMC_A19{slash}EVENTOUT-PadD3)") (class "Default")
      (node (ref "U1") (pin "D3") (pinfunction "PE3/TRACED0/TIM15_BKIN/SAI1_SD_B/SAI4_SD_B/FMC_A19/EVENTOUT_D3") (pintype "bidirectional"))
    )
    (net (code "186") (name "unconnected-(U1C-PE4{slash}TRACED1{slash}SAI1_D2{slash}DFSDM1_DATIN3{slash}TIM15_CH1N{slash}SPI4_NSS{slash}SAI1_FS_A{slash}SAI4_FS_A{slash}SAI4_D2{slash}FMC_A20{slash}DCMI_D4{slash}LCD_B0{slash}EVENTOUT-PadD2)") (class "Default")
      (node (ref "U1") (pin "D2") (pinfunction "PE4/TRACED1/SAI1_D2/DFSDM1_DATIN3/TIM15_CH1N/SPI4_NSS/SAI1_FS_A/SAI4_FS_A/SAI4_D2/FMC_A20/DCMI_D4/LCD_B0/EVENTOUT_D2") (pintype "bidirectional"))
    )
    (net (code "187") (name "unconnected-(U1C-PE5{slash}TRACED2{slash}SAI1_CK2{slash}DFSDM1_CKIN3{slash}TIM15_CH1{slash}SPI4_MISO{slash}SAI1_SCK_A{slash}SAI4_SCK_A{slash}SAI4_CK2{slash}FMC_A21{slash}DCMI_D6{slash}LCD_G0{slash}EVENTOUT-PadD1)") (class "Default")
      (node (ref "U1") (pin "D1") (pinfunction "PE5/TRACED2/SAI1_CK2/DFSDM1_CKIN3/TIM15_CH1/SPI4_MISO/SAI1_SCK_A/SAI4_SCK_A/SAI4_CK2/FMC_A21/DCMI_D6/LCD_G0/EVENTOUT_D1") (pintype "bidirectional"))
    )
    (net (code "188") (name "unconnected-(U1C-PE6{slash}TRACED3{slash}TIM1_BKIN2{slash}SAI1_D1{slash}TIM15_CH2{slash}SPI4_MOSI{slash}SAI1_SD_A{slash}SAI4_SD_A{slash}SAI4_D1{slash}SAI2_MCLK_B{slash}TIM1_BKIN2_COMP12{slash}FMC_A22{slash}DCMI_D7{slash}LCD_G1{slash}EVENTOUT-PadE5)") (class "Default")
      (node (ref "U1") (pin "E5") (pinfunction "PE6/TRACED3/TIM1_BKIN2/SAI1_D1/TIM15_CH2/SPI4_MOSI/SAI1_SD_A/SAI4_SD_A/SAI4_D1/SAI2_MCLK_B/TIM1_BKIN2_COMP12/FMC_A22/DCMI_D7/LCD_G1/EVENTOUT_E5") (pintype "bidirectional"))
    )
    (net (code "189") (name "unconnected-(U1C-PE7{slash}TIM1_ETR{slash}DFSDM1_DATIN2{slash}UART7_RX{slash}QUADSPI_BK2_IO0{slash}FMC_D4{slash}FMC_DA4{slash}EVENTOUT-PadU9)") (class "Default")
      (node (ref "U1") (pin "U9") (pinfunction "PE7/TIM1_ETR/DFSDM1_DATIN2/UART7_RX/QUADSPI_BK2_IO0/FMC_D4/FMC_DA4/EVENTOUT_U9") (pintype "bidirectional"))
    )
    (net (code "190") (name "unconnected-(U1C-PE8{slash}TIM1_CH1N{slash}DFSDM1_CKIN2{slash}UART7_TX{slash}QUADSPI_BK2_IO1{slash}FMC_D5{slash}FMC_DA5{slash}COMP2_OUT{slash}EVENTOUT-PadT9)") (class "Default")
      (node (ref "U1") (pin "T9") (pinfunction "PE8/TIM1_CH1N/DFSDM1_CKIN2/UART7_TX/QUADSPI_BK2_IO1/FMC_D5/FMC_DA5/COMP2_OUT/EVENTOUT_T9") (pintype "bidirectional"))
    )
    (net (code "191") (name "unconnected-(U1C-PE9{slash}TIM1_CH1{slash}DFSDM1_CKOUT{slash}UART7_RTS{slash}UART7_DE{slash}QUADSPI_BK2_IO2{slash}FMC_D6{slash}FMC_DA6{slash}EVENTOUT-PadP9)") (class "Default")
      (node (ref "U1") (pin "P9") (pinfunction "PE9/TIM1_CH1/DFSDM1_CKOUT/UART7_RTS/UART7_DE/QUADSPI_BK2_IO2/FMC_D6/FMC_DA6/EVENTOUT_P9") (pintype "bidirectional"))
    )
    (net (code "192") (name "unconnected-(U1C-PE10{slash}TIM1_CH2N{slash}DFSDM1_DATIN4{slash}UART7_CTS{slash}QUADSPI_BK2_IO3{slash}FMC_D7{slash}FMC_DA7{slash}EVENTOUT-PadN9)") (class "Default")
      (node (ref "U1") (pin "N9") (pinfunction "PE10/TIM1_CH2N/DFSDM1_DATIN4/UART7_CTS/QUADSPI_BK2_IO3/FMC_D7/FMC_DA7/EVENTOUT_N9") (pintype "bidirectional"))
    )
    (net (code "193") (name "unconnected-(U1C-PE11{slash}TIM1_CH2{slash}DFSDM1_CKIN4{slash}SPI4_NSS{slash}SAI2_SD_B{slash}FMC_D8{slash}FMC_DA8{slash}LCD_G3{slash}EVENTOUT-PadP10)") (class "Default")
      (node (ref "U1") (pin "P10") (pinfunction "PE11/TIM1_CH2/DFSDM1_CKIN4/SPI4_NSS/SAI2_SD_B/FMC_D8/FMC_DA8/LCD_G3/EVENTOUT_P10") (pintype "bidirectional"))
    )
    (net (code "194") (name "unconnected-(U1C-PE12{slash}TIM1_CH3N{slash}DFSDM1_DATIN5{slash}SPI4_SCK{slash}SAI2_SCK_B{slash}FMC_D9{slash}FMC_DA9{slash}COMP1_OUT{slash}LCD_B4{slash}EVENTOUT-PadR10)") (class "Default")
      (node (ref "U1") (pin "R10") (pinfunction "PE12/TIM1_CH3N/DFSDM1_DATIN5/SPI4_SCK/SAI2_SCK_B/FMC_D9/FMC_DA9/COMP1_OUT/LCD_B4/EVENTOUT_R10") (pintype "bidirectional"))
    )
    (net (code "195") (name "unconnected-(U1C-PE13{slash}TIM1_CH3{slash}DFSDM1_CKIN5{slash}SPI4_MISO{slash}SAI2_FS_B{slash}FMC_D10{slash}FMC_DA10{slash}COMP2_OUT{slash}LCD_DE{slash}EVENTOUT-PadT10)") (class "Default")
      (node (ref "U1") (pin "T10") (pinfunction "PE13/TIM1_CH3/DFSDM1_CKIN5/SPI4_MISO/SAI2_FS_B/FMC_D10/FMC_DA10/COMP2_OUT/LCD_DE/EVENTOUT_T10") (pintype "bidirectional"))
    )
    (net (code "196") (name "unconnected-(U1C-PE15{slash}TIM1_BKIN{slash}FMC_D12{slash}FMC_DA12{slash}TIM1_BKIN_COMP12{slash}COMP_TIM1_BKIN{slash}LCD_R7{slash}EVENTOUT-PadR11)") (class "Default")
      (node (ref "U1") (pin "R11") (pinfunction "PE15/TIM1_BKIN/FMC_D12/FMC_DA12/TIM1_BKIN_COMP12/COMP_TIM1_BKIN/LCD_R7/EVENTOUT_R11") (pintype "bidirectional"))
    )
    (net (code "197") (name "unconnected-(U1C-PF2{slash}I2C2_SMBA{slash}FMC_A2{slash}EVENTOUT-PadG1)") (class "Default")
      (node (ref "U1") (pin "G1") (pinfunction "PF2/I2C2_SMBA/FMC_A2/EVENTOUT_G1") (pintype "bidirectional"))
    )
    (net (code "198") (name "unconnected-(U1C-PF3{slash}FMC_A3{slash}EVENTOUT-PadH4)") (class "Default")
      (node (ref "U1") (pin "H4") (pinfunction "PF3/FMC_A3/EVENTOUT_H4") (pintype "bidirectional"))
    )
    (net (code "199") (name "unconnected-(U1C-PF4{slash}FMC_A4{slash}EVENTOUT-PadJ5)") (class "Default")
      (node (ref "U1") (pin "J5") (pinfunction "PF4/FMC_A4/EVENTOUT_J5") (pintype "bidirectional"))
    )
    (net (code "200") (name "unconnected-(U1C-PF5{slash}FMC_A5{slash}EVENTOUT-PadJ4)") (class "Default")
      (node (ref "U1") (pin "J4") (pinfunction "PF5/FMC_A5/EVENTOUT_J4") (pintype "bidirectional"))
    )
    (net (code "201") (name "unconnected-(U1C-PF7{slash}TIM17_CH1{slash}SPI5_SCK{slash}SAI1_MCLK_B{slash}UART7_TX{slash}SAI4_MCLK_B{slash}QUADSPI_BK1_IO2{slash}EVENTOUT-PadK3)") (class "Default")
      (node (ref "U1") (pin "K3") (pinfunction "PF7/TIM17_CH1/SPI5_SCK/SAI1_MCLK_B/UART7_TX/SAI4_MCLK_B/QUADSPI_BK1_IO2/EVENTOUT_K3") (pintype "bidirectional"))
    )
    (net (code "202") (name "unconnected-(U1C-PF10{slash}TIM16_BKIN{slash}SAI1_D3{slash}QUADSPI_CLK{slash}SAI4_D3{slash}DCMI_D11{slash}LCD_DE{slash}EVENTOUT-PadL3)") (class "Default")
      (node (ref "U1") (pin "L3") (pinfunction "PF10/TIM16_BKIN/SAI1_D3/QUADSPI_CLK/SAI4_D3/DCMI_D11/LCD_DE/EVENTOUT_L3") (pintype "bidirectional"))
    )
    (net (code "203") (name "unconnected-(U1C-PF12{slash}FMC_A6{slash}EVENTOUT-PadR7)") (class "Default")
      (node (ref "U1") (pin "R7") (pinfunction "PF12/FMC_A6/EVENTOUT_R7") (pintype "bidirectional"))
    )
    (net (code "204") (name "unconnected-(U1C-PF13{slash}DFSDM1_DATIN6{slash}I2C4_SMBA{slash}FMC_A7{slash}EVENTOUT-PadP7)") (class "Default")
      (node (ref "U1") (pin "P7") (pinfunction "PF13/DFSDM1_DATIN6/I2C4_SMBA/FMC_A7/EVENTOUT_P7") (pintype "bidirectional"))
    )
    (net (code "205") (name "unconnected-(U1C-PF14{slash}DFSDM1_CKIN6{slash}I2C4_SCL{slash}FMC_A8{slash}EVENTOUT-PadP8)") (class "Default")
      (node (ref "U1") (pin "P8") (pinfunction "PF14/DFSDM1_CKIN6/I2C4_SCL/FMC_A8/EVENTOUT_P8") (pintype "bidirectional"))
    )
    (net (code "206") (name "unconnected-(U1C-PF15{slash}I2C4_SDA{slash}FMC_A9{slash}EVENTOUT-PadR9)") (class "Default")
      (node (ref "U1") (pin "R9") (pinfunction "PF15/I2C4_SDA/FMC_A9/EVENTOUT_R9") (pintype "bidirectional"))
    )
    (net (code "207") (name "unconnected-(U1D-PG0{slash}FMC_A10{slash}EVENTOUT-PadT8)") (class "Default")
      (node (ref "U1") (pin "T8") (pinfunction "PG0/FMC_A10/EVENTOUT_T8") (pintype "bidirectional"))
    )
    (net (code "208") (name "unconnected-(U1D-PG1{slash}FMC_A11{slash}EVENTOUT-PadU8)") (class "Default")
      (node (ref "U1") (pin "U8") (pinfunction "PG1/FMC_A11/EVENTOUT_U8") (pintype "bidirectional"))
    )
    (net (code "209") (name "unconnected-(U1D-PG2{slash}TIM8_BKIN{slash}TIM8_BKIN_COMP12{slash}FMC_A12{slash}EVENTOUT-PadH16)") (class "Default")
      (node (ref "U1") (pin "H16") (pinfunction "PG2/TIM8_BKIN/TIM8_BKIN_COMP12/FMC_A12/EVENTOUT_H16") (pintype "bidirectional"))
    )
    (net (code "210") (name "unconnected-(U1D-PG3{slash}TIM8_BKIN2{slash}TIM8_BKIN2_COMP12{slash}FMC_A13{slash}EVENTOUT-PadH15)") (class "Default")
      (node (ref "U1") (pin "H15") (pinfunction "PG3/TIM8_BKIN2/TIM8_BKIN2_COMP12/FMC_A13/EVENTOUT_H15") (pintype "bidirectional"))
    )
    (net (code "211") (name "unconnected-(U1D-PG4{slash}TIM1_BKIN2{slash}TIM1_BKIN2_COMP12{slash}FMC_A14{slash}FMC_BA0{slash}EVENTOUT-PadH14)") (class "Default")
      (node (ref "U1") (pin "H14") (pinfunction "PG4/TIM1_BKIN2/TIM1_BKIN2_COMP12/FMC_A14/FMC_BA0/EVENTOUT_H14") (pintype "bidirectional"))
    )
    (net (code "212") (name "unconnected-(U1D-PG5{slash}TIM1_ETR{slash}FMC_A15{slash}FMC_BA1{slash}EVENTOUT-PadG14)") (class "Default")
      (node (ref "U1") (pin "G14") (pinfunction "PG5/TIM1_ETR/FMC_A15/FMC_BA1/EVENTOUT_G14") (pintype "bidirectional"))
    )
    (net (code "213") (name "unconnected-(U1D-PG7{slash}HRTIM_CHE2{slash}SAI1_MCLK_A{slash}USART6_CK{slash}FMC_INT{slash}DCMI_D13{slash}LCD_CLK{slash}EVENTOUT-PadF16)") (class "Default")
      (node (ref "U1") (pin "F16") (pinfunction "PG7/HRTIM_CHE2/SAI1_MCLK_A/USART6_CK/FMC_INT/DCMI_D13/LCD_CLK/EVENTOUT_F16") (pintype "bidirectional"))
    )
    (net (code "214") (name "unconnected-(U1D-PG8{slash}TIM8_ETR{slash}SPI6_NSS{slash}USART6_RTS{slash}USART6_DE{slash}SPDIFRX1_IN3{slash}ETH_PPS_OUT{slash}FMC_SDCLK{slash}LCD_G7{slash}EVENTOUT-PadF15)") (class "Default")
      (node (ref "U1") (pin "F15") (pinfunction "PG8/TIM8_ETR/SPI6_NSS/USART6_RTS/USART6_DE/SPDIFRX1_IN3/ETH_PPS_OUT/FMC_SDCLK/LCD_G7/EVENTOUT_F15") (pintype "bidirectional"))
    )
    (net (code "215") (name "unconnected-(U1D-PG10{slash}HRTIM_FLT5{slash}SPI1_NSS{slash}I2S1_WS{slash}LCD_G3{slash}SAI2_SD_B{slash}FMC_NE3{slash}DCMI_D2{slash}LCD_B2{slash}EVENTOUT-PadA9)") (class "Default")
      (node (ref "U1") (pin "A9") (pinfunction "PG10/HRTIM_FLT5/SPI1_NSS/I2S1_WS/LCD_G3/SAI2_SD_B/FMC_NE3/DCMI_D2/LCD_B2/EVENTOUT_A9") (pintype "bidirectional"))
    )
    (net (code "216") (name "unconnected-(U1D-PG12{slash}LPTIM1_IN1{slash}HRTIM_EEV5{slash}SPI6_MISO{slash}USART6_RTS{slash}USART6_DE{slash}SPDIFRX1_IN2{slash}LCD_B4{slash}ETH_MII_TXD1{slash}ETH_RMII_TXD1{slash}FMC_NE4{slash}LCD_B1{slash}EVENTOUT-PadC9)") (class "Default")
      (node (ref "U1") (pin "C9") (pinfunction "PG12/LPTIM1_IN1/HRTIM_EEV5/SPI6_MISO/USART6_RTS/USART6_DE/SPDIFRX1_IN2/LCD_B4/ETH_MII_TXD1/ETH_RMII_TXD1/FMC_NE4/LCD_B1/EVENTOUT_C9") (pintype "bidirectional"))
    )
    (net (code "217") (name "unconnected-(U1D-PG13{slash}TRACED0{slash}LPTIM1_OUT{slash}HRTIM_EEV10{slash}SPI6_SCK{slash}USART6_CTS{slash}USART6_NSS{slash}ETH_MII_TXD0{slash}ETH_RMII_TXD0{slash}FMC_A24{slash}LCD_R0{slash}EVENTOUT-PadD9)") (class "Default")
      (node (ref "U1") (pin "D9") (pinfunction "PG13/TRACED0/LPTIM1_OUT/HRTIM_EEV10/SPI6_SCK/USART6_CTS/USART6_NSS/ETH_MII_TXD0/ETH_RMII_TXD0/FMC_A24/LCD_R0/EVENTOUT_D9") (pintype "bidirectional"))
    )
    (net (code "218") (name "unconnected-(U1D-PG14{slash}TRACED1{slash}LPTIM1_ETR{slash}SPI6_MOSI{slash}USART6_TX{slash}QUADSPI_BK2_IO3{slash}ETH_MII_TXD1{slash}ETH_RMII_TXD1{slash}FMC_A25{slash}LCD_B0{slash}EVENTOUT-PadD8)") (class "Default")
      (node (ref "U1") (pin "D8") (pinfunction "PG14/TRACED1/LPTIM1_ETR/SPI6_MOSI/USART6_TX/QUADSPI_BK2_IO3/ETH_MII_TXD1/ETH_RMII_TXD1/FMC_A25/LCD_B0/EVENTOUT_D8") (pintype "bidirectional"))
    )
    (net (code "219") (name "unconnected-(U1D-PG15{slash}USART6_CTS{slash}USART6_NSS{slash}FMC_SDNCAS{slash}DCMI_D13{slash}EVENTOUT-PadD6)") (class "Default")
      (node (ref "U1") (pin "D6") (pinfunction "PG15/USART6_CTS/USART6_NSS/FMC_SDNCAS/DCMI_D13/EVENTOUT_D6") (pintype "bidirectional"))
    )
    (net (code "220") (name "unconnected-(U1D-PH2{slash}LPTIM1_IN2{slash}QUADSPI_BK2_IO0{slash}SAI2_SCK_B{slash}ETH_MII_CRS{slash}FMC_SDCKE0{slash}LCD_R0{slash}EVENTOUT-PadN2)") (class "Default")
      (node (ref "U1") (pin "N2") (pinfunction "PH2/LPTIM1_IN2/QUADSPI_BK2_IO0/SAI2_SCK_B/ETH_MII_CRS/FMC_SDCKE0/LCD_R0/EVENTOUT_N2") (pintype "bidirectional"))
    )
    (net (code "221") (name "unconnected-(U1D-PH3{slash}QUADSPI_BK2_IO1{slash}SAI2_MCLK_B{slash}ETH_MII_COL{slash}FMC_SDNE0{slash}LCD_R1{slash}EVENTOUT-PadP2)") (class "Default")
      (node (ref "U1") (pin "P2") (pinfunction "PH3/QUADSPI_BK2_IO1/SAI2_MCLK_B/ETH_MII_COL/FMC_SDNE0/LCD_R1/EVENTOUT_P2") (pintype "bidirectional"))
    )
    (net (code "222") (name "unconnected-(U1D-PH4{slash}I2C2_SCL{slash}LCD_G5{slash}OTG_HS_ULPI_NXT{slash}LCD_G4{slash}EVENTOUT-PadP3)") (class "Default")
      (node (ref "U1") (pin "P3") (pinfunction "PH4/I2C2_SCL/LCD_G5/OTG_HS_ULPI_NXT/LCD_G4/EVENTOUT_P3") (pintype "bidirectional"))
    )
    (net (code "223") (name "unconnected-(U1D-PH5{slash}I2C2_SDA{slash}SPI5_NSS{slash}FMC_SDNWE{slash}EVENTOUT-PadP4)") (class "Default")
      (node (ref "U1") (pin "P4") (pinfunction "PH5/I2C2_SDA/SPI5_NSS/FMC_SDNWE/EVENTOUT_P4") (pintype "bidirectional"))
    )
    (net (code "224") (name "unconnected-(U1D-PH6{slash}TIM12_CH1{slash}I2C2_SMBA{slash}SPI5_SCK{slash}ETH_MII_RXD2{slash}FMC_SDNE1{slash}DCMI_D8{slash}EVENTOUT-PadT11)") (class "Default")
      (node (ref "U1") (pin "T11") (pinfunction "PH6/TIM12_CH1/I2C2_SMBA/SPI5_SCK/ETH_MII_RXD2/FMC_SDNE1/DCMI_D8/EVENTOUT_T11") (pintype "bidirectional"))
    )
    (net (code "225") (name "unconnected-(U1D-PH7{slash}I2C3_SCL{slash}SPI5_MISO{slash}ETH_MII_RXD3{slash}FMC_SDCKE1{slash}DCMI_D9{slash}EVENTOUT-PadU13)") (class "Default")
      (node (ref "U1") (pin "U13") (pinfunction "PH7/I2C3_SCL/SPI5_MISO/ETH_MII_RXD3/FMC_SDCKE1/DCMI_D9/EVENTOUT_U13") (pintype "bidirectional"))
    )
    (net (code "226") (name "unconnected-(U1D-PH8{slash}TIM5_ETR{slash}I2C3_SDA{slash}FMC_D16{slash}DCMI_HSYNC{slash}LCD_R2{slash}EVENTOUT-PadT13)") (class "Default")
      (node (ref "U1") (pin "T13") (pinfunction "PH8/TIM5_ETR/I2C3_SDA/FMC_D16/DCMI_HSYNC/LCD_R2/EVENTOUT_T13") (pintype "bidirectional"))
    )
    (net (code "227") (name "unconnected-(U1D-PH9{slash}TIM12_CH2{slash}I2C3_SMBA{slash}FMC_D17{slash}DCMI_D0{slash}LCD_R3{slash}EVENTOUT-PadR13)") (class "Default")
      (node (ref "U1") (pin "R13") (pinfunction "PH9/TIM12_CH2/I2C3_SMBA/FMC_D17/DCMI_D0/LCD_R3/EVENTOUT_R13") (pintype "bidirectional"))
    )
    (net (code "228") (name "unconnected-(U1D-PH10{slash}TIM5_CH1{slash}I2C4_SMBA{slash}FMC_D18{slash}DCMI_D1{slash}LCD_R4{slash}EVENTOUT-PadP13)") (class "Default")
      (node (ref "U1") (pin "P13") (pinfunction "PH10/TIM5_CH1/I2C4_SMBA/FMC_D18/DCMI_D1/LCD_R4/EVENTOUT_P13") (pintype "bidirectional"))
    )
    (net (code "229") (name "unconnected-(U1D-PH11{slash}TIM5_CH2{slash}I2C4_SCL{slash}FMC_D19{slash}DCMI_D2{slash}LCD_R5{slash}EVENTOUT-PadP14)") (class "Default")
      (node (ref "U1") (pin "P14") (pinfunction "PH11/TIM5_CH2/I2C4_SCL/FMC_D19/DCMI_D2/LCD_R5/EVENTOUT_P14") (pintype "bidirectional"))
    )
    (net (code "230") (name "unconnected-(U1D-PH12{slash}TIM5_CH3{slash}I2C4_SDA{slash}FMC_D20{slash}DCMI_D3{slash}LCD_R6{slash}EVENTOUT-PadR14)") (class "Default")
      (node (ref "U1") (pin "R14") (pinfunction "PH12/TIM5_CH3/I2C4_SDA/FMC_D20/DCMI_D3/LCD_R6/EVENTOUT_R14") (pintype "bidirectional"))
    )
    (net (code "231") (name "unconnected-(U1D-PH15{slash}TIM8_CH3N{slash}FDCAN1_TXFD_MODE{slash}FMC_D23{slash}DCMI_D11{slash}LCD_G4{slash}EVENTOUT-PadB16)") (class "Default")
      (node (ref "U1") (pin "B16") (pinfunction "PH15/TIM8_CH3N/FDCAN1_TXFD_MODE/FMC_D23/DCMI_D11/LCD_G4/EVENTOUT_B16") (pintype "bidirectional"))
    )
    (net (code "232") (name "unconnected-(U1E-PI4{slash}TIM8_BKIN{slash}SAI2_MCLK_A{slash}TIM8_BKIN_COMP12{slash}FMC_NBL2{slash}DCMI_D5{slash}LCD_B4{slash}EVENTOUT-PadA4)") (class "Default")
      (node (ref "U1") (pin "A4") (pinfunction "PI4/TIM8_BKIN/SAI2_MCLK_A/TIM8_BKIN_COMP12/FMC_NBL2/DCMI_D5/LCD_B4/EVENTOUT_A4") (pintype "bidirectional"))
    )
    (net (code "233") (name "unconnected-(U1E-PI5{slash}TIM8_CH1{slash}SAI2_SCK_A{slash}FMC_NBL3{slash}DCMI_VSYNC{slash}LCD_B5{slash}EVENTOUT-PadA3)") (class "Default")
      (node (ref "U1") (pin "A3") (pinfunction "PI5/TIM8_CH1/SAI2_SCK_A/FMC_NBL3/DCMI_VSYNC/LCD_B5/EVENTOUT_A3") (pintype "bidirectional"))
    )
    (net (code "234") (name "unconnected-(U1E-PI8{slash}EVENTOUT-PadE4)") (class "Default")
      (node (ref "U1") (pin "E4") (pinfunction "PI8/EVENTOUT_E4") (pintype "bidirectional"))
    )
    (net (code "235") (name "unconnected-(U1E-PI9{slash}UART4_RX{slash}FDCAN1_RX{slash}FMC_D30{slash}LCD_VSYNC{slash}EVENTOUT-PadE2)") (class "Default")
      (node (ref "U1") (pin "E2") (pinfunction "PI9/UART4_RX/FDCAN1_RX/FMC_D30/LCD_VSYNC/EVENTOUT_E2") (pintype "bidirectional"))
    )
    (net (code "236") (name "unconnected-(U1E-PI10{slash}FDCAN1_RXFD_MODE{slash}ETH_MII_RX_ER{slash}FMC_D31{slash}LCD_HSYNC{slash}EVENTOUT-PadF3)") (class "Default")
      (node (ref "U1") (pin "F3") (pinfunction "PI10/FDCAN1_RXFD_MODE/ETH_MII_RX_ER/FMC_D31/LCD_HSYNC/EVENTOUT_F3") (pintype "bidirectional"))
    )
    (net (code "237") (name "unconnected-(U1E-PI11{slash}LCD_G6{slash}OTG_HS_ULPI_DIR{slash}EVENTOUT-PadF4)") (class "Default")
      (node (ref "U1") (pin "F4") (pinfunction "PI11/LCD_G6/OTG_HS_ULPI_DIR/EVENTOUT_F4") (pintype "bidirectional"))
    )
    (net (code "238") (name "unconnected-(U1E-PI12{slash}LCD_HSYNC{slash}EVENTOUT-PadH1)") (class "Default")
      (node (ref "U1") (pin "H1") (pinfunction "PI12/LCD_HSYNC/EVENTOUT_H1") (pintype "bidirectional"))
    )
    (net (code "239") (name "unconnected-(U1E-PI13{slash}LCD_VSYNC{slash}EVENTOUT-PadH2)") (class "Default")
      (node (ref "U1") (pin "H2") (pinfunction "PI13/LCD_VSYNC/EVENTOUT_H2") (pintype "bidirectional"))
    )
    (net (code "240") (name "unconnected-(U1E-PI14{slash}LCD_CLK{slash}EVENTOUT-PadH3)") (class "Default")
      (node (ref "U1") (pin "H3") (pinfunction "PI14/LCD_CLK/EVENTOUT_H3") (pintype "bidirectional"))
    )
    (net (code "241") (name "unconnected-(U1E-PI15{slash}LCD_G2{slash}LCD_R0{slash}EVENTOUT-PadP5)") (class "Default")
      (node (ref "U1") (pin "P5") (pinfunction "PI15/LCD_G2/LCD_R0/EVENTOUT_P5") (pintype "bidirectional"))
    )
    (net (code "242") (name "unconnected-(U1E-PJ0{slash}LCD_R7{slash}LCD_R1{slash}EVENTOUT-PadN6)") (class "Default")
      (node (ref "U1") (pin "N6") (pinfunction "PJ0/LCD_R7/LCD_R1/EVENTOUT_N6") (pintype "bidirectional"))
    )
    (net (code "243") (name "unconnected-(U1E-PJ1{slash}LCD_R2{slash}EVENTOUT-PadP6)") (class "Default")
      (node (ref "U1") (pin "P6") (pinfunction "PJ1/LCD_R2/EVENTOUT_P6") (pintype "bidirectional"))
    )
    (net (code "244") (name "unconnected-(U1E-PJ2{slash}LCD_R3{slash}EVENTOUT-PadT6)") (class "Default")
      (node (ref "U1") (pin "T6") (pinfunction "PJ2/LCD_R3/EVENTOUT_T6") (pintype "bidirectional"))
    )
    (net (code "245") (name "unconnected-(U1E-PJ3{slash}LCD_R4{slash}EVENTOUT-PadU6)") (class "Default")
      (node (ref "U1") (pin "U6") (pinfunction "PJ3/LCD_R4/EVENTOUT_U6") (pintype "bidirectional"))
    )
    (net (code "246") (name "unconnected-(U1E-PJ4{slash}LCD_R5{slash}EVENTOUT-PadU7)") (class "Default")
      (node (ref "U1") (pin "U7") (pinfunction "PJ4/LCD_R5/EVENTOUT_U7") (pintype "bidirectional"))
    )
    (net (code "247") (name "unconnected-(U1E-PJ5{slash}LCD_R6{slash}EVENTOUT-PadR12)") (class "Default")
      (node (ref "U1") (pin "R12") (pinfunction "PJ5/LCD_R6/EVENTOUT_R12") (pintype "bidirectional"))
    )
    (net (code "248") (name "unconnected-(U1E-PJ6{slash}TIM8_CH2{slash}LCD_R7{slash}EVENTOUT-PadN15)") (class "Default")
      (node (ref "U1") (pin "N15") (pinfunction "PJ6/TIM8_CH2/LCD_R7/EVENTOUT_N15") (pintype "bidirectional"))
    )
    (net (code "249") (name "unconnected-(U1E-PJ7{slash}TRGIN{slash}TIM8_CH2N{slash}LCD_G0{slash}EVENTOUT-PadN14)") (class "Default")
      (node (ref "U1") (pin "N14") (pinfunction "PJ7/TRGIN/TIM8_CH2N/LCD_G0/EVENTOUT_N14") (pintype "bidirectional"))
    )
    (net (code "250") (name "unconnected-(U1E-PJ9{slash}TIM1_CH3{slash}TIM8_CH1N{slash}UART8_RX{slash}LCD_G2{slash}EVENTOUT-PadM14)") (class "Default")
      (node (ref "U1") (pin "M14") (pinfunction "PJ9/TIM1_CH3/TIM8_CH1N/UART8_RX/LCD_G2/EVENTOUT_M14") (pintype "bidirectional"))
    )
    (net (code "251") (name "unconnected-(U1E-PJ10{slash}TIM1_CH2N{slash}TIM8_CH2{slash}SPI5_MOSI{slash}LCD_G3{slash}EVENTOUT-PadL14)") (class "Default")
      (node (ref "U1") (pin "L14") (pinfunction "PJ10/TIM1_CH2N/TIM8_CH2/SPI5_MOSI/LCD_G3/EVENTOUT_L14") (pintype "bidirectional"))
    )
    (net (code "252") (name "unconnected-(U1E-PJ11{slash}TIM1_CH2{slash}TIM8_CH2N{slash}SPI5_MISO{slash}LCD_G4{slash}EVENTOUT-PadK14)") (class "Default")
      (node (ref "U1") (pin "K14") (pinfunction "PJ11/TIM1_CH2/TIM8_CH2N/SPI5_MISO/LCD_G4/EVENTOUT_K14") (pintype "bidirectional"))
    )
    (net (code "253") (name "unconnected-(U1E-PJ12{slash}TRGOUT{slash}LCD_G3{slash}LCD_B0{slash}EVENTOUT-PadD11)") (class "Default")
      (node (ref "U1") (pin "D11") (pinfunction "PJ12/TRGOUT/LCD_G3/LCD_B0/EVENTOUT_D11") (pintype "bidirectional"))
    )
    (net (code "254") (name "unconnected-(U1E-PJ13{slash}LCD_B4{slash}LCD_B1{slash}EVENTOUT-PadE10)") (class "Default")
      (node (ref "U1") (pin "E10") (pinfunction "PJ13/LCD_B4/LCD_B1/EVENTOUT_E10") (pintype "bidirectional"))
    )
    (net (code "255") (name "unconnected-(U1E-PJ14{slash}LCD_B2{slash}EVENTOUT-PadD10)") (class "Default")
      (node (ref "U1") (pin "D10") (pinfunction "PJ14/LCD_B2/EVENTOUT_D10") (pintype "bidirectional"))
    )
    (net (code "256") (name "unconnected-(U1E-PJ15{slash}LCD_B3{slash}EVENTOUT-PadB10)") (class "Default")
      (node (ref "U1") (pin "B10") (pinfunction "PJ15/LCD_B3/EVENTOUT_B10") (pintype "bidirectional"))
    )
    (net (code "257") (name "unconnected-(U1E-PK0{slash}TIM1_CH1N{slash}TIM8_CH3{slash}SPI5_SCK{slash}LCD_G5{slash}EVENTOUT-PadJ14)") (class "Default")
      (node (ref "U1") (pin "J14") (pinfunction "PK0/TIM1_CH1N/TIM8_CH3/SPI5_SCK/LCD_G5/EVENTOUT_J14") (pintype "bidirectional"))
    )
    (net (code "258") (name "unconnected-(U1E-PK2{slash}TIM1_BKIN{slash}TIM8_BKIN{slash}TIM8_BKIN_COMP12{slash}TIM1_BKIN_COMP12{slash}LCD_G7{slash}EVENTOUT-PadH17)") (class "Default")
      (node (ref "U1") (pin "H17") (pinfunction "PK2/TIM1_BKIN/TIM8_BKIN/TIM8_BKIN_COMP12/TIM1_BKIN_COMP12/LCD_G7/EVENTOUT_H17") (pintype "bidirectional"))
    )
    (net (code "259") (name "unconnected-(U1E-PK3{slash}LCD_B4{slash}EVENTOUT-PadC8)") (class "Default")
      (node (ref "U1") (pin "C8") (pinfunction "PK3/LCD_B4/EVENTOUT_C8") (pintype "bidirectional"))
    )
    (net (code "260") (name "unconnected-(U1E-PK4{slash}LCD_B5{slash}EVENTOUT-PadB8)") (class "Default")
      (node (ref "U1") (pin "B8") (pinfunction "PK4/LCD_B5/EVENTOUT_B8") (pintype "bidirectional"))
    )
    (net (code "261") (name "unconnected-(U1E-PK5{slash}LCD_B6{slash}EVENTOUT-PadA8)") (class "Default")
      (node (ref "U1") (pin "A8") (pinfunction "PK5/LCD_B6/EVENTOUT_A8") (pintype "bidirectional"))
    )
    (net (code "262") (name "unconnected-(U1E-PK6{slash}LCD_B7{slash}EVENTOUT-PadC7)") (class "Default")
      (node (ref "U1") (pin "C7") (pinfunction "PK6/LCD_B7/EVENTOUT_C7") (pintype "bidirectional"))
    )
    (net (code "263") (name "unconnected-(U1E-PK7{slash}LCD_DE{slash}EVENTOUT-PadD7)") (class "Default")
      (node (ref "U1") (pin "D7") (pinfunction "PK7/LCD_DE/EVENTOUT_D7") (pintype "bidirectional"))
    )
    (net (code "264") (name "unconnected-(U1F-NC-PadE1)") (class "Default")
      (node (ref "U1") (pin "E1") (pinfunction "NC_E1") (pintype "no_connect"))
    )
    (net (code "265") (name "unconnected-(U1F-NC-PadK16)") (class "Default")
      (node (ref "U1") (pin "K16") (pinfunction "NC_K16") (pintype "no_connect"))
    )
    (net (code "266") (name "unconnected-(U1F-NC-PadK17)") (class "Default")
      (node (ref "U1") (pin "K17") (pinfunction "NC_K17") (pintype "no_connect"))
    )
    (net (code "267") (name "unconnected-(U1F-NC-PadL16)") (class "Default")
      (node (ref "U1") (pin "L16") (pinfunction "NC_L16") (pintype "no_connect"))
    )
    (net (code "268") (name "unconnected-(U1F-NC-PadL17)") (class "Default")
      (node (ref "U1") (pin "L17") (pinfunction "NC_L17") (pintype "no_connect"))
    )
    (net (code "269") (name "unconnected-(U1F-NC-PadM16)") (class "Default")
      (node (ref "U1") (pin "M16") (pinfunction "NC_M16") (pintype "no_connect"))
    )
    (net (code "270") (name "unconnected-(U1F-NC-PadM17)") (class "Default")
      (node (ref "U1") (pin "M17") (pinfunction "NC_M17") (pintype "no_connect"))
    )
    (net (code "271") (name "unconnected-(U1F-NC-PadN17)") (class "Default")
      (node (ref "U1") (pin "N17") (pinfunction "NC_N17") (pintype "no_connect"))
    )
    (net (code "272") (name "unconnected-(U1F-NC1-PadF1)") (class "Default")
      (node (ref "U1") (pin "F1") (pinfunction "NC1_F1") (pintype "passive"))
    )
    (net (code "273") (name "unconnected-(U1F-NC2-PadG2)") (class "Default")
      (node (ref "U1") (pin "G2") (pinfunction "NC2_G2") (pintype "passive"))
    )
    (net (code "274") (name "unconnected-(U2-AUX_CL-Pad7)") (class "Default")
      (node (ref "U2") (pin "7") (pinfunction "AUX_CL_7") (pintype "bidirectional"))
    )
    (net (code "275") (name "unconnected-(U2-AUX_DA-Pad6)") (class "Default")
      (node (ref "U2") (pin "6") (pinfunction "AUX_DA_6") (pintype "bidirectional"))
    )
    (net (code "276") (name "unconnected-(U2-NC_2-Pad2)") (class "Default")
      (node (ref "U2") (pin "2") (pinfunction "NC_2_2") (pintype "passive"))
    )
    (net (code "277") (name "unconnected-(U2-NC_3-Pad3)") (class "Default")
      (node (ref "U2") (pin "3") (pinfunction "NC_3_3") (pintype "passive"))
    )
    (net (code "278") (name "unconnected-(U2-NC_4-Pad4)") (class "Default")
      (node (ref "U2") (pin "4") (pinfunction "NC_4_4") (pintype "passive"))
    )
    (net (code "279") (name "unconnected-(U2-NC_5-Pad5)") (class "Default")
      (node (ref "U2") (pin "5") (pinfunction "NC_5_5") (pintype "passive"))
    )
    (net (code "280") (name "unconnected-(U2-NC_14-Pad14)") (class "Default")
      (node (ref "U2") (pin "14") (pinfunction "NC_14_14") (pintype "passive"))
    )
    (net (code "281") (name "unconnected-(U2-NC_15-Pad15)") (class "Default")
      (node (ref "U2") (pin "15") (pinfunction "NC_15_15") (pintype "passive"))
    )
    (net (code "282") (name "unconnected-(U2-NC_16-Pad16)") (class "Default")
      (node (ref "U2") (pin "16") (pinfunction "NC_16_16") (pintype "passive"))
    )
    (net (code "283") (name "unconnected-(U2-NC_17-Pad17)") (class "Default")
      (node (ref "U2") (pin "17") (pinfunction "NC_17_17") (pintype "passive"))
    )
    (net (code "284") (name "unconnected-(U2-RESV_19-Pad19)") (class "Default")
      (node (ref "U2") (pin "19") (pinfunction "RESV_19_19") (pintype "passive"))
    )
    (net (code "285") (name "unconnected-(U2-RESV_21-Pad21)") (class "Default")
      (node (ref "U2") (pin "21") (pinfunction "RESV_21_21") (pintype "passive"))
    )
    (net (code "286") (name "unconnected-(U2-RESV_22-Pad22)") (class "Default")
      (node (ref "U2") (pin "22") (pinfunction "RESV_22_22") (pintype "passive"))
    )
    (net (code "287") (name "unconnected-(U3-(ADC2:0{slash}TOUCH0{slash}RTC10{slash}SPIHD)GPIO4-Pad24)") (class "Default")
      (node (ref "U3") (pin "24") (pinfunction "(ADC2:0/TOUCH0/RTC10/SPIHD)GPIO4_24") (pintype "bidirectional"))
    )
    (net (code "288") (name "unconnected-(U3-(ADC2:7{slash}TOUCH7{slash}RTC17)GPIO27-Pad16)") (class "Default")
      (node (ref "U3") (pin "16") (pinfunction "(ADC2:7/TOUCH7/RTC17)GPIO27_16") (pintype "bidirectional"))
    )
    (net (code "289") (name "unconnected-(U3-(DAC1{slash}ADC2:8{slash}RTC6)GPIO25-Pad14)") (class "Default")
      (node (ref "U3") (pin "14") (pinfunction "(DAC1/ADC2:8/RTC6)GPIO25_14") (pintype "bidirectional"))
    )
    (net (code "290") (name "unconnected-(U3-(DAC2{slash}ADC2:9{slash}RTC7)GPIO26-Pad15)") (class "Default")
      (node (ref "U3") (pin "15") (pinfunction "(DAC2/ADC2:9/RTC7)GPIO26_15") (pintype "bidirectional"))
    )
    (net (code "291") (name "unconnected-(U3-(GPIO12{slash}ADC2:5{slash}TOUCH5{slash}RTC15{slash}SPIQ)MTDI-Pad18)") (class "Default")
      (node (ref "U3") (pin "18") (pinfunction "(GPIO12/ADC2:5/TOUCH5/RTC15/SPIQ)MTDI_18") (pintype "bidirectional"))
    )
    (net (code "292") (name "unconnected-(U3-(GPIO13{slash}ADC2:4{slash}TOUCH4{slash}RTC14{slash}SPID{slash}U0CTS)MTCK-Pad20)") (class "Default")
      (node (ref "U3") (pin "20") (pinfunction "(GPIO13/ADC2:4/TOUCH4/RTC14/SPID/U0CTS)MTCK_20") (pintype "bidirectional"))
    )
    (net (code "293") (name "unconnected-(U3-(GPIO14{slash}ADC2:6{slash}TOUCH6{slash}RTC16{slash}SPICLK)MTMS-Pad17)") (class "Default")
      (node (ref "U3") (pin "17") (pinfunction "(GPIO14/ADC2:6/TOUCH6/RTC16/SPICLK)MTMS_17") (pintype "bidirectional"))
    )
    (net (code "294") (name "unconnected-(U3-(GPIO15{slash}ADC2:3{slash}TOUCH3{slash}RTC13{slash}SPICSO{slash}U0RTS)MTDO-Pad21)") (class "Default")
      (node (ref "U3") (pin "21") (pinfunction "(GPIO15/ADC2:3/TOUCH3/RTC13/SPICSO/U0RTS)MTDO_21") (pintype "bidirectional"))
    )
    (net (code "295") (name "unconnected-(U3-(VSPIHD{slash}HS2_CMD)GPIO21-Pad42)") (class "Default")
      (node (ref "U3") (pin "42") (pinfunction "(VSPIHD/HS2_CMD)GPIO21_42") (pintype "bidirectional"))
    )
    (net (code "296") (name "unconnected-(U3-(VSPIQ{slash}HS2_DATA2)GPIO19-Pad38)") (class "Default")
      (node (ref "U3") (pin "38") (pinfunction "(VSPIQ/HS2_DATA2)GPIO19_38") (pintype "bidirectional"))
    )
    (net (code "297") (name "unconnected-(U3-(VSPIWP{slash}HS2_CLK)GPIO22-Pad39)") (class "Default")
      (node (ref "U3") (pin "39") (pinfunction "(VSPIWP/HS2_CLK)GPIO22_39") (pintype "bidirectional"))
    )
    (net (code "298") (name "unconnected-(U3-GPIO23-Pad36)") (class "Default")
      (node (ref "U3") (pin "36") (pinfunction "GPIO23_36") (pintype "bidirectional"))
    )
    (net (code "299") (name "unconnected-(U3-VDET_1(GPI34{slash}ADC1:6)-Pad10)") (class "Default")
      (node (ref "U3") (pin "10") (pinfunction "VDET_1(GPI34/ADC1:6)_10") (pintype "bidirectional"))
    )
    (net (code "300") (name "unconnected-(U3-VDET_2(GPI35{slash}ADC1:7)-Pad11)") (class "Default")
      (node (ref "U3") (pin "11") (pinfunction "VDET_2(GPI35/ADC1:7)_11") (pintype "bidirectional"))
    )
    (net (code "301") (name "unconnected-(U7-NC-Pad4)") (class "Default")
      (node (ref "U7") (pin "4") (pinfunction "NC_4") (pintype "no_connect"))
    )
    (net (code "302") (name "~{CARD_DTC}") (class "Default")
      (node (ref "SD1") (pin "9") (pinfunction "~{CARD}_9") (pintype "passive"))
      (node (ref "U1") (pin "T1") (pinfunction "PA0_C/TIM2_CH1/TIM2_ETR/TIM5_CH1/TIM8_ETR/TIM15_BKIN/USART2_CTS/USART2_NSS/UART4_TX/SDMMC2_CMD/SAI2_SD_B/ETH_MII_CRS/EVENTOUT_T1") (pintype "bidirectional"))
    )
    (net (code "303") (name "~{MHSYNC}") (class "Default")
      (node (ref "IC1") (pin "18") (pinfunction "~{HSYNC}_18") (pintype "bidirectional"))
      (node (ref "R33") (pin "1") (pinfunction "1_1") (pintype "passive"))
    )
    (net (code "304") (name "~{MVSYNC}") (class "Default")
      (node (ref "IC1") (pin "17") (pinfunction "~{VSYNC}_17") (pintype "bidirectional"))
      (node (ref "R34") (pin "1") (pinfunction "1_1") (pintype "passive"))
    )
    (net (code "305") (name "~{RESET}") (class "Default")
      (node (ref "Q2") (pin "3") (pinfunction "C_3") (pintype "passive"))
      (node (ref "R1") (pin "1") (pinfunction "1_1") (pintype "passive"))
      (node (ref "RST") (pin "TP") (pinfunction "TP_TP") (pintype "input"))
      (node (ref "U3") (pin "9") (pinfunction "CHIP_PU_9") (pintype "bidirectional"))
    )
  )
)
